# TestBoardExport.net
KiCad netlist of a schematic drawn in EAGLE
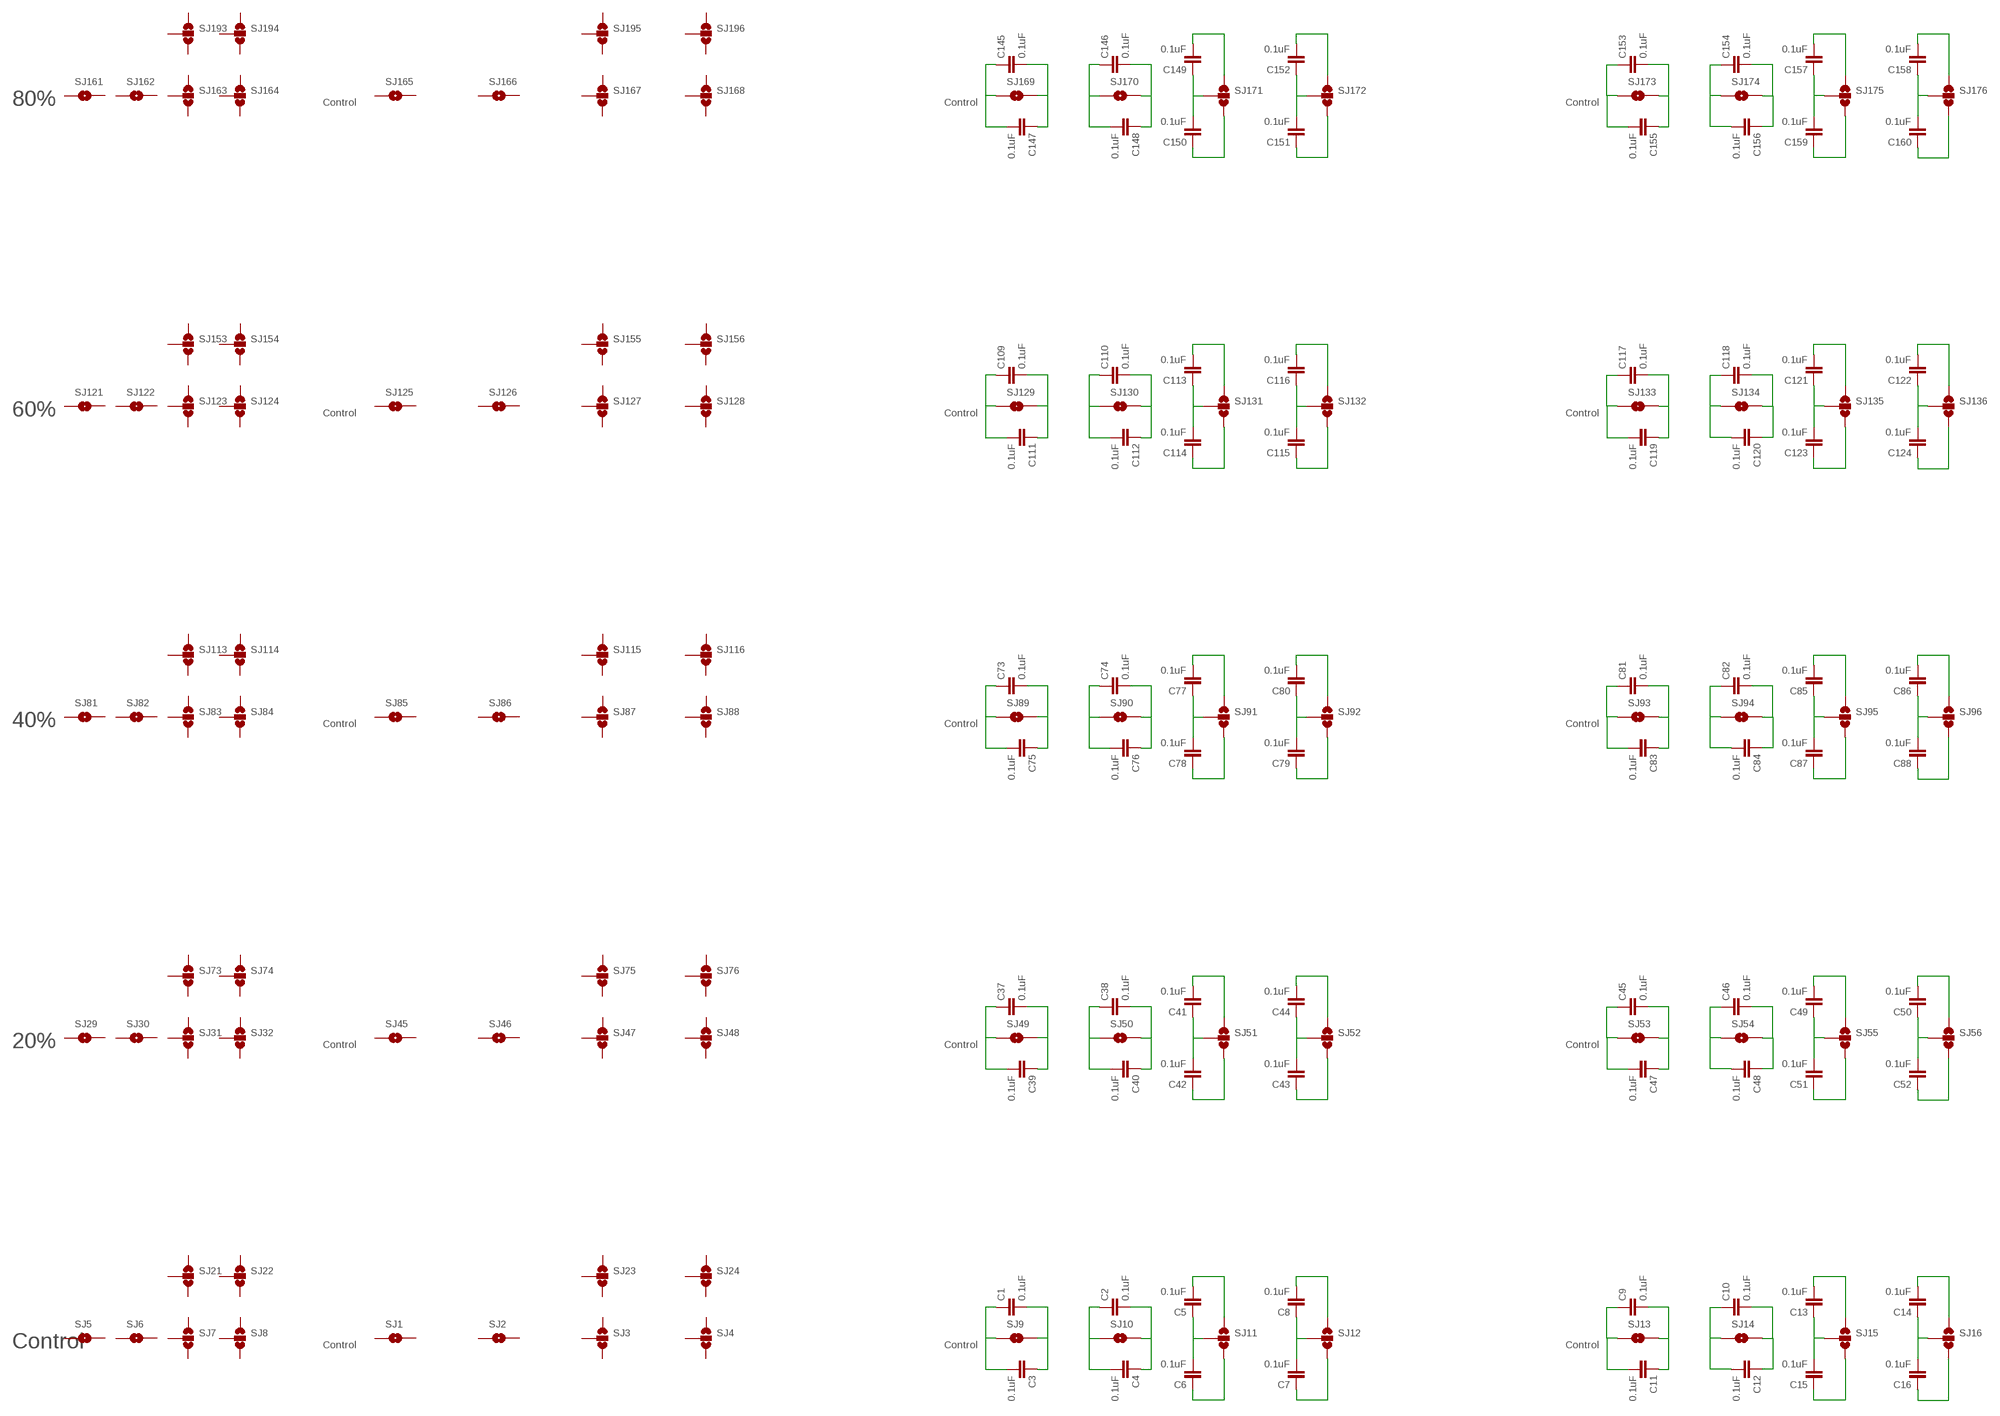
[diagram p0: schematic, sheet 1, part 1 of 3]
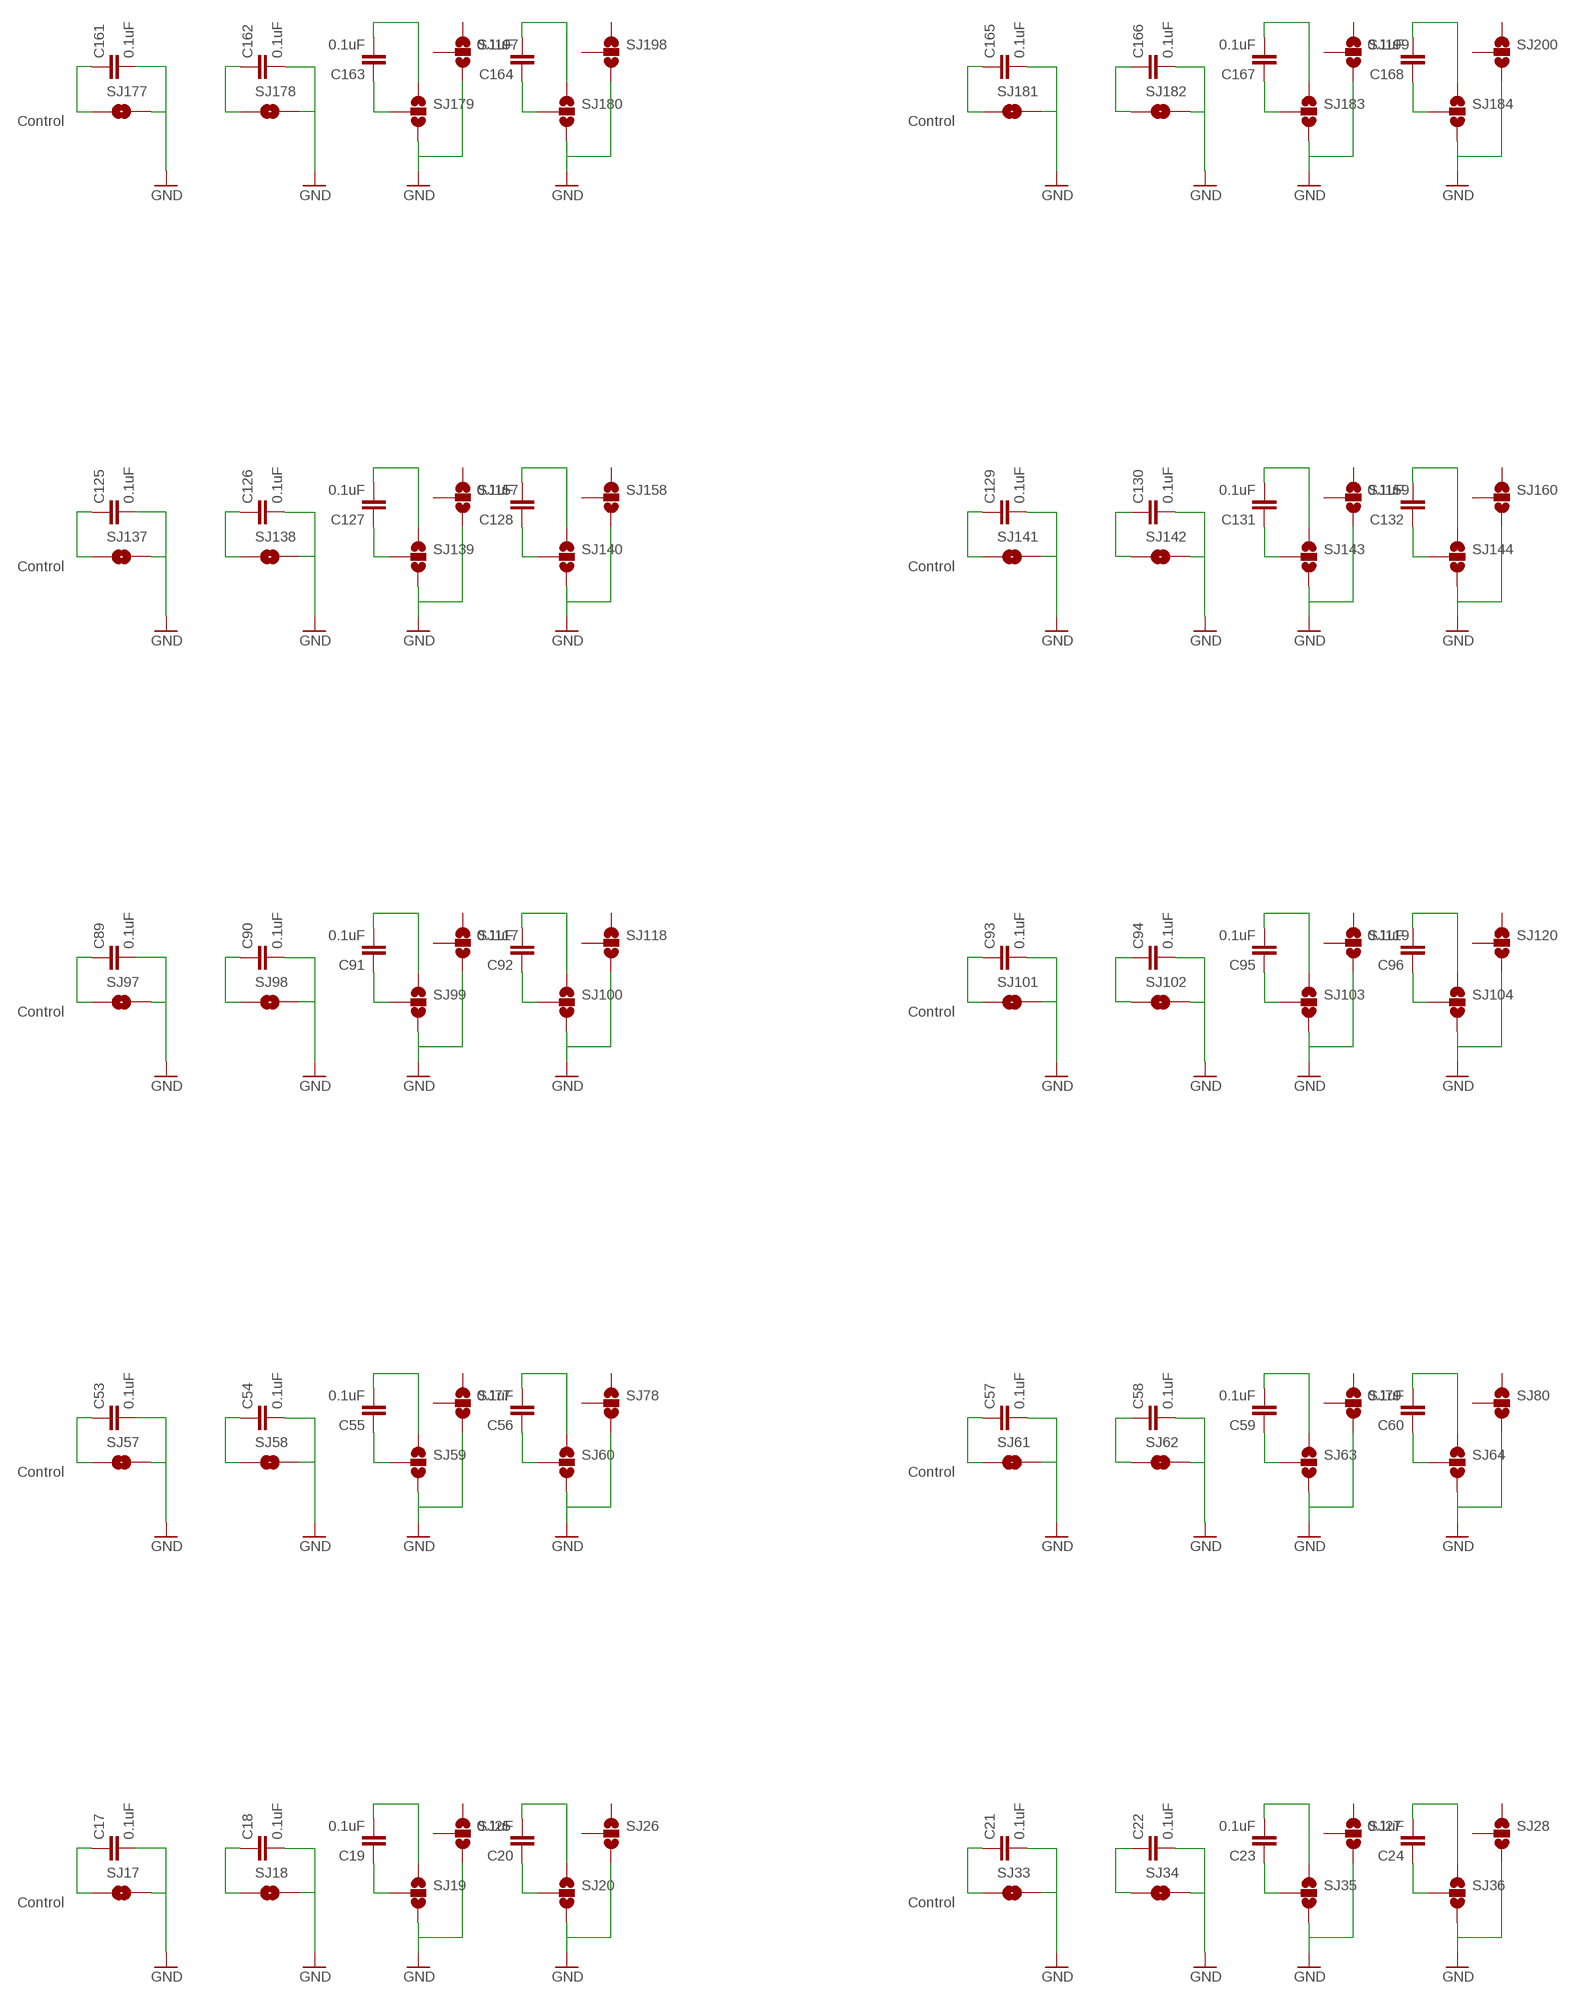
[diagram p1: schematic, sheet 1, part 2 of 3]
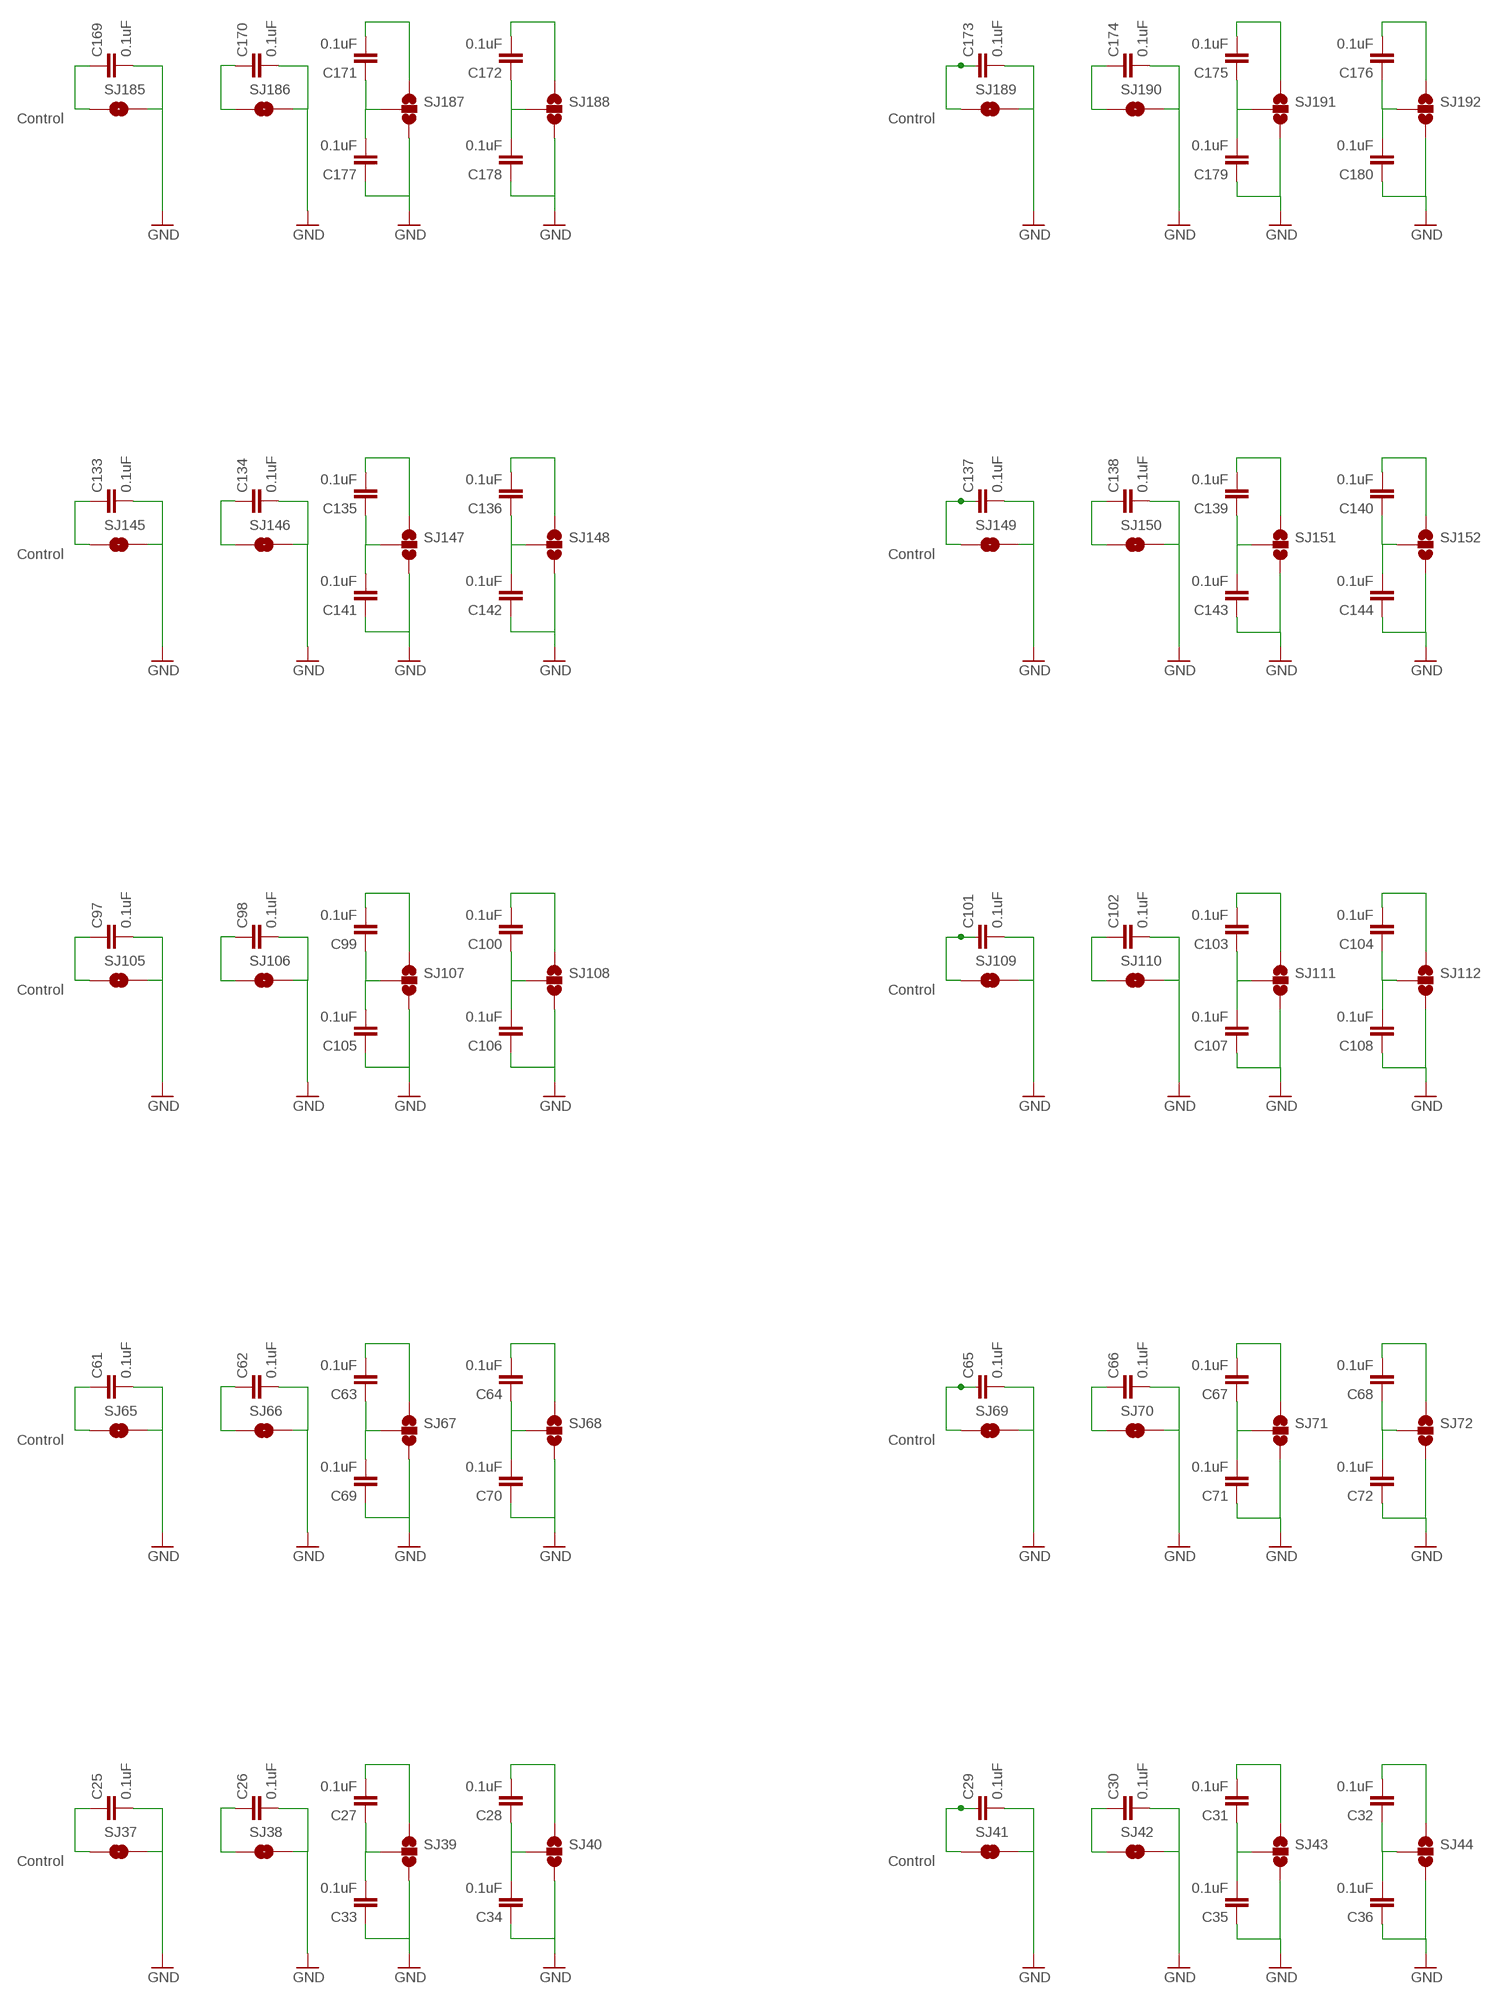
[diagram p2: schematic, sheet 1, part 3 of 3]

(export (version "E")
  (design (tool "Eeschema 10.0.6"))
  (components
    (comp (ref "C1")
      (value "0.1uF")
      (footprint "eagle-import:0603-CAP")
      (libsource (lib "eagle-import") (part "0.1UF-25V-5%(0603)"))
    )
    (comp (ref "C2")
      (value "0.1uF")
      (footprint "eagle-import:0603-CAP")
      (libsource (lib "eagle-import") (part "0.1UF-25V-5%(0603)"))
    )
    (comp (ref "C3")
      (value "0.1uF")
      (footprint "eagle-import:0603-CAP")
      (libsource (lib "eagle-import") (part "0.1UF-25V-5%(0603)"))
    )
    (comp (ref "C4")
      (value "0.1uF")
      (footprint "eagle-import:0603-CAP")
      (libsource (lib "eagle-import") (part "0.1UF-25V-5%(0603)"))
    )
    (comp (ref "C5")
      (value "0.1uF")
      (footprint "eagle-import:0603-CAP")
      (libsource (lib "eagle-import") (part "0.1UF-25V-5%(0603)"))
    )
    (comp (ref "C6")
      (value "0.1uF")
      (footprint "eagle-import:0603-CAP")
      (libsource (lib "eagle-import") (part "0.1UF-25V-5%(0603)"))
    )
    (comp (ref "C7")
      (value "0.1uF")
      (footprint "eagle-import:0603-CAP")
      (libsource (lib "eagle-import") (part "0.1UF-25V-5%(0603)"))
    )
    (comp (ref "C8")
      (value "0.1uF")
      (footprint "eagle-import:0603-CAP")
      (libsource (lib "eagle-import") (part "0.1UF-25V-5%(0603)"))
    )
    (comp (ref "C9")
      (value "0.1uF")
      (footprint "eagle-import:0603-CAP")
      (libsource (lib "eagle-import") (part "0.1UF-25V-5%(0603)"))
    )
    (comp (ref "C10")
      (value "0.1uF")
      (footprint "eagle-import:0603-CAP")
      (libsource (lib "eagle-import") (part "0.1UF-25V-5%(0603)"))
    )
    (comp (ref "C11")
      (value "0.1uF")
      (footprint "eagle-import:0603-CAP")
      (libsource (lib "eagle-import") (part "0.1UF-25V-5%(0603)"))
    )
    (comp (ref "C12")
      (value "0.1uF")
      (footprint "eagle-import:0603-CAP")
      (libsource (lib "eagle-import") (part "0.1UF-25V-5%(0603)"))
    )
    (comp (ref "C13")
      (value "0.1uF")
      (footprint "eagle-import:0603-CAP")
      (libsource (lib "eagle-import") (part "0.1UF-25V-5%(0603)"))
    )
    (comp (ref "C14")
      (value "0.1uF")
      (footprint "eagle-import:0603-CAP")
      (libsource (lib "eagle-import") (part "0.1UF-25V-5%(0603)"))
    )
    (comp (ref "C15")
      (value "0.1uF")
      (footprint "eagle-import:0603-CAP")
      (libsource (lib "eagle-import") (part "0.1UF-25V-5%(0603)"))
    )
    (comp (ref "C16")
      (value "0.1uF")
      (footprint "eagle-import:0603-CAP")
      (libsource (lib "eagle-import") (part "0.1UF-25V-5%(0603)"))
    )
    (comp (ref "C17")
      (value "0.1uF")
      (footprint "eagle-import:0603-CAP")
      (libsource (lib "eagle-import") (part "0.1UF-25V-5%(0603)"))
    )
    (comp (ref "C18")
      (value "0.1uF")
      (footprint "eagle-import:0603-CAP")
      (libsource (lib "eagle-import") (part "0.1UF-25V-5%(0603)"))
    )
    (comp (ref "C19")
      (value "0.1uF")
      (footprint "eagle-import:0603-CAP")
      (libsource (lib "eagle-import") (part "0.1UF-25V-5%(0603)"))
    )
    (comp (ref "C20")
      (value "0.1uF")
      (footprint "eagle-import:0603-CAP")
      (libsource (lib "eagle-import") (part "0.1UF-25V-5%(0603)"))
    )
    (comp (ref "C21")
      (value "0.1uF")
      (footprint "eagle-import:0603-CAP")
      (libsource (lib "eagle-import") (part "0.1UF-25V-5%(0603)"))
    )
    (comp (ref "C22")
      (value "0.1uF")
      (footprint "eagle-import:0603-CAP")
      (libsource (lib "eagle-import") (part "0.1UF-25V-5%(0603)"))
    )
    (comp (ref "C23")
      (value "0.1uF")
      (footprint "eagle-import:0603-CAP")
      (libsource (lib "eagle-import") (part "0.1UF-25V-5%(0603)"))
    )
    (comp (ref "C24")
      (value "0.1uF")
      (footprint "eagle-import:0603-CAP")
      (libsource (lib "eagle-import") (part "0.1UF-25V-5%(0603)"))
    )
    (comp (ref "C25")
      (value "0.1uF")
      (footprint "eagle-import:0603-CAP")
      (libsource (lib "eagle-import") (part "0.1UF-25V-5%(0603)"))
    )
    (comp (ref "C26")
      (value "0.1uF")
      (footprint "eagle-import:0603-CAP")
      (libsource (lib "eagle-import") (part "0.1UF-25V-5%(0603)"))
    )
    (comp (ref "C27")
      (value "0.1uF")
      (footprint "eagle-import:0603-CAP")
      (libsource (lib "eagle-import") (part "0.1UF-25V-5%(0603)"))
    )
    (comp (ref "C28")
      (value "0.1uF")
      (footprint "eagle-import:0603-CAP")
      (libsource (lib "eagle-import") (part "0.1UF-25V-5%(0603)"))
    )
    (comp (ref "C29")
      (value "0.1uF")
      (footprint "eagle-import:0603-CAP")
      (libsource (lib "eagle-import") (part "0.1UF-25V-5%(0603)"))
    )
    (comp (ref "C30")
      (value "0.1uF")
      (footprint "eagle-import:0603-CAP")
      (libsource (lib "eagle-import") (part "0.1UF-25V-5%(0603)"))
    )
    (comp (ref "C31")
      (value "0.1uF")
      (footprint "eagle-import:0603-CAP")
      (libsource (lib "eagle-import") (part "0.1UF-25V-5%(0603)"))
    )
    (comp (ref "C32")
      (value "0.1uF")
      (footprint "eagle-import:0603-CAP")
      (libsource (lib "eagle-import") (part "0.1UF-25V-5%(0603)"))
    )
    (comp (ref "C33")
      (value "0.1uF")
      (footprint "eagle-import:0603-CAP")
      (libsource (lib "eagle-import") (part "0.1UF-25V-5%(0603)"))
    )
    (comp (ref "C34")
      (value "0.1uF")
      (footprint "eagle-import:0603-CAP")
      (libsource (lib "eagle-import") (part "0.1UF-25V-5%(0603)"))
    )
    (comp (ref "C35")
      (value "0.1uF")
      (footprint "eagle-import:0603-CAP")
      (libsource (lib "eagle-import") (part "0.1UF-25V-5%(0603)"))
    )
    (comp (ref "C36")
      (value "0.1uF")
      (footprint "eagle-import:0603-CAP")
      (libsource (lib "eagle-import") (part "0.1UF-25V-5%(0603)"))
    )
    (comp (ref "C37")
      (value "0.1uF")
      (footprint "eagle-import:0603-CAP")
      (libsource (lib "eagle-import") (part "0.1UF-25V-5%(0603)"))
    )
    (comp (ref "C38")
      (value "0.1uF")
      (footprint "eagle-import:0603-CAP")
      (libsource (lib "eagle-import") (part "0.1UF-25V-5%(0603)"))
    )
    (comp (ref "C39")
      (value "0.1uF")
      (footprint "eagle-import:0603-CAP")
      (libsource (lib "eagle-import") (part "0.1UF-25V-5%(0603)"))
    )
    (comp (ref "C40")
      (value "0.1uF")
      (footprint "eagle-import:0603-CAP")
      (libsource (lib "eagle-import") (part "0.1UF-25V-5%(0603)"))
    )
    (comp (ref "C41")
      (value "0.1uF")
      (footprint "eagle-import:0603-CAP")
      (libsource (lib "eagle-import") (part "0.1UF-25V-5%(0603)"))
    )
    (comp (ref "C42")
      (value "0.1uF")
      (footprint "eagle-import:0603-CAP")
      (libsource (lib "eagle-import") (part "0.1UF-25V-5%(0603)"))
    )
    (comp (ref "C43")
      (value "0.1uF")
      (footprint "eagle-import:0603-CAP")
      (libsource (lib "eagle-import") (part "0.1UF-25V-5%(0603)"))
    )
    (comp (ref "C44")
      (value "0.1uF")
      (footprint "eagle-import:0603-CAP")
      (libsource (lib "eagle-import") (part "0.1UF-25V-5%(0603)"))
    )
    (comp (ref "C45")
      (value "0.1uF")
      (footprint "eagle-import:0603-CAP")
      (libsource (lib "eagle-import") (part "0.1UF-25V-5%(0603)"))
    )
    (comp (ref "C46")
      (value "0.1uF")
      (footprint "eagle-import:0603-CAP")
      (libsource (lib "eagle-import") (part "0.1UF-25V-5%(0603)"))
    )
    (comp (ref "C47")
      (value "0.1uF")
      (footprint "eagle-import:0603-CAP")
      (libsource (lib "eagle-import") (part "0.1UF-25V-5%(0603)"))
    )
    (comp (ref "C48")
      (value "0.1uF")
      (footprint "eagle-import:0603-CAP")
      (libsource (lib "eagle-import") (part "0.1UF-25V-5%(0603)"))
    )
    (comp (ref "C49")
      (value "0.1uF")
      (footprint "eagle-import:0603-CAP")
      (libsource (lib "eagle-import") (part "0.1UF-25V-5%(0603)"))
    )
    (comp (ref "C50")
      (value "0.1uF")
      (footprint "eagle-import:0603-CAP")
      (libsource (lib "eagle-import") (part "0.1UF-25V-5%(0603)"))
    )
    (comp (ref "C51")
      (value "0.1uF")
      (footprint "eagle-import:0603-CAP")
      (libsource (lib "eagle-import") (part "0.1UF-25V-5%(0603)"))
    )
    (comp (ref "C52")
      (value "0.1uF")
      (footprint "eagle-import:0603-CAP")
      (libsource (lib "eagle-import") (part "0.1UF-25V-5%(0603)"))
    )
    (comp (ref "C53")
      (value "0.1uF")
      (footprint "eagle-import:0603-CAP")
      (libsource (lib "eagle-import") (part "0.1UF-25V-5%(0603)"))
    )
    (comp (ref "C54")
      (value "0.1uF")
      (footprint "eagle-import:0603-CAP")
      (libsource (lib "eagle-import") (part "0.1UF-25V-5%(0603)"))
    )
    (comp (ref "C55")
      (value "0.1uF")
      (footprint "eagle-import:0603-CAP")
      (libsource (lib "eagle-import") (part "0.1UF-25V-5%(0603)"))
    )
    (comp (ref "C56")
      (value "0.1uF")
      (footprint "eagle-import:0603-CAP")
      (libsource (lib "eagle-import") (part "0.1UF-25V-5%(0603)"))
    )
    (comp (ref "C57")
      (value "0.1uF")
      (footprint "eagle-import:0603-CAP")
      (libsource (lib "eagle-import") (part "0.1UF-25V-5%(0603)"))
    )
    (comp (ref "C58")
      (value "0.1uF")
      (footprint "eagle-import:0603-CAP")
      (libsource (lib "eagle-import") (part "0.1UF-25V-5%(0603)"))
    )
    (comp (ref "C59")
      (value "0.1uF")
      (footprint "eagle-import:0603-CAP")
      (libsource (lib "eagle-import") (part "0.1UF-25V-5%(0603)"))
    )
    (comp (ref "C60")
      (value "0.1uF")
      (footprint "eagle-import:0603-CAP")
      (libsource (lib "eagle-import") (part "0.1UF-25V-5%(0603)"))
    )
    (comp (ref "C61")
      (value "0.1uF")
      (footprint "eagle-import:0603-CAP")
      (libsource (lib "eagle-import") (part "0.1UF-25V-5%(0603)"))
    )
    (comp (ref "C62")
      (value "0.1uF")
      (footprint "eagle-import:0603-CAP")
      (libsource (lib "eagle-import") (part "0.1UF-25V-5%(0603)"))
    )
    (comp (ref "C63")
      (value "0.1uF")
      (footprint "eagle-import:0603-CAP")
      (libsource (lib "eagle-import") (part "0.1UF-25V-5%(0603)"))
    )
    (comp (ref "C64")
      (value "0.1uF")
      (footprint "eagle-import:0603-CAP")
      (libsource (lib "eagle-import") (part "0.1UF-25V-5%(0603)"))
    )
    (comp (ref "C65")
      (value "0.1uF")
      (footprint "eagle-import:0603-CAP")
      (libsource (lib "eagle-import") (part "0.1UF-25V-5%(0603)"))
    )
    (comp (ref "C66")
      (value "0.1uF")
      (footprint "eagle-import:0603-CAP")
      (libsource (lib "eagle-import") (part "0.1UF-25V-5%(0603)"))
    )
    (comp (ref "C67")
      (value "0.1uF")
      (footprint "eagle-import:0603-CAP")
      (libsource (lib "eagle-import") (part "0.1UF-25V-5%(0603)"))
    )
    (comp (ref "C68")
      (value "0.1uF")
      (footprint "eagle-import:0603-CAP")
      (libsource (lib "eagle-import") (part "0.1UF-25V-5%(0603)"))
    )
    (comp (ref "C69")
      (value "0.1uF")
      (footprint "eagle-import:0603-CAP")
      (libsource (lib "eagle-import") (part "0.1UF-25V-5%(0603)"))
    )
    (comp (ref "C70")
      (value "0.1uF")
      (footprint "eagle-import:0603-CAP")
      (libsource (lib "eagle-import") (part "0.1UF-25V-5%(0603)"))
    )
    (comp (ref "C71")
      (value "0.1uF")
      (footprint "eagle-import:0603-CAP")
      (libsource (lib "eagle-import") (part "0.1UF-25V-5%(0603)"))
    )
    (comp (ref "C72")
      (value "0.1uF")
      (footprint "eagle-import:0603-CAP")
      (libsource (lib "eagle-import") (part "0.1UF-25V-5%(0603)"))
    )
    (comp (ref "C73")
      (value "0.1uF")
      (footprint "eagle-import:0603-CAP")
      (libsource (lib "eagle-import") (part "0.1UF-25V-5%(0603)"))
    )
    (comp (ref "C74")
      (value "0.1uF")
      (footprint "eagle-import:0603-CAP")
      (libsource (lib "eagle-import") (part "0.1UF-25V-5%(0603)"))
    )
    (comp (ref "C75")
      (value "0.1uF")
      (footprint "eagle-import:0603-CAP")
      (libsource (lib "eagle-import") (part "0.1UF-25V-5%(0603)"))
    )
    (comp (ref "C76")
      (value "0.1uF")
      (footprint "eagle-import:0603-CAP")
      (libsource (lib "eagle-import") (part "0.1UF-25V-5%(0603)"))
    )
    (comp (ref "C77")
      (value "0.1uF")
      (footprint "eagle-import:0603-CAP")
      (libsource (lib "eagle-import") (part "0.1UF-25V-5%(0603)"))
    )
    (comp (ref "C78")
      (value "0.1uF")
      (footprint "eagle-import:0603-CAP")
      (libsource (lib "eagle-import") (part "0.1UF-25V-5%(0603)"))
    )
    (comp (ref "C79")
      (value "0.1uF")
      (footprint "eagle-import:0603-CAP")
      (libsource (lib "eagle-import") (part "0.1UF-25V-5%(0603)"))
    )
    (comp (ref "C80")
      (value "0.1uF")
      (footprint "eagle-import:0603-CAP")
      (libsource (lib "eagle-import") (part "0.1UF-25V-5%(0603)"))
    )
    (comp (ref "C81")
      (value "0.1uF")
      (footprint "eagle-import:0603-CAP")
      (libsource (lib "eagle-import") (part "0.1UF-25V-5%(0603)"))
    )
    (comp (ref "C82")
      (value "0.1uF")
      (footprint "eagle-import:0603-CAP")
      (libsource (lib "eagle-import") (part "0.1UF-25V-5%(0603)"))
    )
    (comp (ref "C83")
      (value "0.1uF")
      (footprint "eagle-import:0603-CAP")
      (libsource (lib "eagle-import") (part "0.1UF-25V-5%(0603)"))
    )
    (comp (ref "C84")
      (value "0.1uF")
      (footprint "eagle-import:0603-CAP")
      (libsource (lib "eagle-import") (part "0.1UF-25V-5%(0603)"))
    )
    (comp (ref "C85")
      (value "0.1uF")
      (footprint "eagle-import:0603-CAP")
      (libsource (lib "eagle-import") (part "0.1UF-25V-5%(0603)"))
    )
    (comp (ref "C86")
      (value "0.1uF")
      (footprint "eagle-import:0603-CAP")
      (libsource (lib "eagle-import") (part "0.1UF-25V-5%(0603)"))
    )
    (comp (ref "C87")
      (value "0.1uF")
      (footprint "eagle-import:0603-CAP")
      (libsource (lib "eagle-import") (part "0.1UF-25V-5%(0603)"))
    )
    (comp (ref "C88")
      (value "0.1uF")
      (footprint "eagle-import:0603-CAP")
      (libsource (lib "eagle-import") (part "0.1UF-25V-5%(0603)"))
    )
    (comp (ref "C89")
      (value "0.1uF")
      (footprint "eagle-import:0603-CAP")
      (libsource (lib "eagle-import") (part "0.1UF-25V-5%(0603)"))
    )
    (comp (ref "C90")
      (value "0.1uF")
      (footprint "eagle-import:0603-CAP")
      (libsource (lib "eagle-import") (part "0.1UF-25V-5%(0603)"))
    )
    (comp (ref "C91")
      (value "0.1uF")
      (footprint "eagle-import:0603-CAP")
      (libsource (lib "eagle-import") (part "0.1UF-25V-5%(0603)"))
    )
    (comp (ref "C92")
      (value "0.1uF")
      (footprint "eagle-import:0603-CAP")
      (libsource (lib "eagle-import") (part "0.1UF-25V-5%(0603)"))
    )
    (comp (ref "C93")
      (value "0.1uF")
      (footprint "eagle-import:0603-CAP")
      (libsource (lib "eagle-import") (part "0.1UF-25V-5%(0603)"))
    )
    (comp (ref "C94")
      (value "0.1uF")
      (footprint "eagle-import:0603-CAP")
      (libsource (lib "eagle-import") (part "0.1UF-25V-5%(0603)"))
    )
    (comp (ref "C95")
      (value "0.1uF")
      (footprint "eagle-import:0603-CAP")
      (libsource (lib "eagle-import") (part "0.1UF-25V-5%(0603)"))
    )
    (comp (ref "C96")
      (value "0.1uF")
      (footprint "eagle-import:0603-CAP")
      (libsource (lib "eagle-import") (part "0.1UF-25V-5%(0603)"))
    )
    (comp (ref "C97")
      (value "0.1uF")
      (footprint "eagle-import:0603-CAP")
      (libsource (lib "eagle-import") (part "0.1UF-25V-5%(0603)"))
    )
    (comp (ref "C98")
      (value "0.1uF")
      (footprint "eagle-import:0603-CAP")
      (libsource (lib "eagle-import") (part "0.1UF-25V-5%(0603)"))
    )
    (comp (ref "C99")
      (value "0.1uF")
      (footprint "eagle-import:0603-CAP")
      (libsource (lib "eagle-import") (part "0.1UF-25V-5%(0603)"))
    )
    (comp (ref "C100")
      (value "0.1uF")
      (footprint "eagle-import:0603-CAP")
      (libsource (lib "eagle-import") (part "0.1UF-25V-5%(0603)"))
    )
    (comp (ref "C101")
      (value "0.1uF")
      (footprint "eagle-import:0603-CAP")
      (libsource (lib "eagle-import") (part "0.1UF-25V-5%(0603)"))
    )
    (comp (ref "C102")
      (value "0.1uF")
      (footprint "eagle-import:0603-CAP")
      (libsource (lib "eagle-import") (part "0.1UF-25V-5%(0603)"))
    )
    (comp (ref "C103")
      (value "0.1uF")
      (footprint "eagle-import:0603-CAP")
      (libsource (lib "eagle-import") (part "0.1UF-25V-5%(0603)"))
    )
    (comp (ref "C104")
      (value "0.1uF")
      (footprint "eagle-import:0603-CAP")
      (libsource (lib "eagle-import") (part "0.1UF-25V-5%(0603)"))
    )
    (comp (ref "C105")
      (value "0.1uF")
      (footprint "eagle-import:0603-CAP")
      (libsource (lib "eagle-import") (part "0.1UF-25V-5%(0603)"))
    )
    (comp (ref "C106")
      (value "0.1uF")
      (footprint "eagle-import:0603-CAP")
      (libsource (lib "eagle-import") (part "0.1UF-25V-5%(0603)"))
    )
    (comp (ref "C107")
      (value "0.1uF")
      (footprint "eagle-import:0603-CAP")
      (libsource (lib "eagle-import") (part "0.1UF-25V-5%(0603)"))
    )
    (comp (ref "C108")
      (value "0.1uF")
      (footprint "eagle-import:0603-CAP")
      (libsource (lib "eagle-import") (part "0.1UF-25V-5%(0603)"))
    )
    (comp (ref "C109")
      (value "0.1uF")
      (footprint "eagle-import:0603-CAP")
      (libsource (lib "eagle-import") (part "0.1UF-25V-5%(0603)"))
    )
    (comp (ref "C110")
      (value "0.1uF")
      (footprint "eagle-import:0603-CAP")
      (libsource (lib "eagle-import") (part "0.1UF-25V-5%(0603)"))
    )
    (comp (ref "C111")
      (value "0.1uF")
      (footprint "eagle-import:0603-CAP")
      (libsource (lib "eagle-import") (part "0.1UF-25V-5%(0603)"))
    )
    (comp (ref "C112")
      (value "0.1uF")
      (footprint "eagle-import:0603-CAP")
      (libsource (lib "eagle-import") (part "0.1UF-25V-5%(0603)"))
    )
    (comp (ref "C113")
      (value "0.1uF")
      (footprint "eagle-import:0603-CAP")
      (libsource (lib "eagle-import") (part "0.1UF-25V-5%(0603)"))
    )
    (comp (ref "C114")
      (value "0.1uF")
      (footprint "eagle-import:0603-CAP")
      (libsource (lib "eagle-import") (part "0.1UF-25V-5%(0603)"))
    )
    (comp (ref "C115")
      (value "0.1uF")
      (footprint "eagle-import:0603-CAP")
      (libsource (lib "eagle-import") (part "0.1UF-25V-5%(0603)"))
    )
    (comp (ref "C116")
      (value "0.1uF")
      (footprint "eagle-import:0603-CAP")
      (libsource (lib "eagle-import") (part "0.1UF-25V-5%(0603)"))
    )
    (comp (ref "C117")
      (value "0.1uF")
      (footprint "eagle-import:0603-CAP")
      (libsource (lib "eagle-import") (part "0.1UF-25V-5%(0603)"))
    )
    (comp (ref "C118")
      (value "0.1uF")
      (footprint "eagle-import:0603-CAP")
      (libsource (lib "eagle-import") (part "0.1UF-25V-5%(0603)"))
    )
    (comp (ref "C119")
      (value "0.1uF")
      (footprint "eagle-import:0603-CAP")
      (libsource (lib "eagle-import") (part "0.1UF-25V-5%(0603)"))
    )
    (comp (ref "C120")
      (value "0.1uF")
      (footprint "eagle-import:0603-CAP")
      (libsource (lib "eagle-import") (part "0.1UF-25V-5%(0603)"))
    )
    (comp (ref "C121")
      (value "0.1uF")
      (footprint "eagle-import:0603-CAP")
      (libsource (lib "eagle-import") (part "0.1UF-25V-5%(0603)"))
    )
    (comp (ref "C122")
      (value "0.1uF")
      (footprint "eagle-import:0603-CAP")
      (libsource (lib "eagle-import") (part "0.1UF-25V-5%(0603)"))
    )
    (comp (ref "C123")
      (value "0.1uF")
      (footprint "eagle-import:0603-CAP")
      (libsource (lib "eagle-import") (part "0.1UF-25V-5%(0603)"))
    )
    (comp (ref "C124")
      (value "0.1uF")
      (footprint "eagle-import:0603-CAP")
      (libsource (lib "eagle-import") (part "0.1UF-25V-5%(0603)"))
    )
    (comp (ref "C125")
      (value "0.1uF")
      (footprint "eagle-import:0603-CAP")
      (libsource (lib "eagle-import") (part "0.1UF-25V-5%(0603)"))
    )
    (comp (ref "C126")
      (value "0.1uF")
      (footprint "eagle-import:0603-CAP")
      (libsource (lib "eagle-import") (part "0.1UF-25V-5%(0603)"))
    )
    (comp (ref "C127")
      (value "0.1uF")
      (footprint "eagle-import:0603-CAP")
      (libsource (lib "eagle-import") (part "0.1UF-25V-5%(0603)"))
    )
    (comp (ref "C128")
      (value "0.1uF")
      (footprint "eagle-import:0603-CAP")
      (libsource (lib "eagle-import") (part "0.1UF-25V-5%(0603)"))
    )
    (comp (ref "C129")
      (value "0.1uF")
      (footprint "eagle-import:0603-CAP")
      (libsource (lib "eagle-import") (part "0.1UF-25V-5%(0603)"))
    )
    (comp (ref "C130")
      (value "0.1uF")
      (footprint "eagle-import:0603-CAP")
      (libsource (lib "eagle-import") (part "0.1UF-25V-5%(0603)"))
    )
    (comp (ref "C131")
      (value "0.1uF")
      (footprint "eagle-import:0603-CAP")
      (libsource (lib "eagle-import") (part "0.1UF-25V-5%(0603)"))
    )
    (comp (ref "C132")
      (value "0.1uF")
      (footprint "eagle-import:0603-CAP")
      (libsource (lib "eagle-import") (part "0.1UF-25V-5%(0603)"))
    )
    (comp (ref "C133")
      (value "0.1uF")
      (footprint "eagle-import:0603-CAP")
      (libsource (lib "eagle-import") (part "0.1UF-25V-5%(0603)"))
    )
    (comp (ref "C134")
      (value "0.1uF")
      (footprint "eagle-import:0603-CAP")
      (libsource (lib "eagle-import") (part "0.1UF-25V-5%(0603)"))
    )
    (comp (ref "C135")
      (value "0.1uF")
      (footprint "eagle-import:0603-CAP")
      (libsource (lib "eagle-import") (part "0.1UF-25V-5%(0603)"))
    )
    (comp (ref "C136")
      (value "0.1uF")
      (footprint "eagle-import:0603-CAP")
      (libsource (lib "eagle-import") (part "0.1UF-25V-5%(0603)"))
    )
    (comp (ref "C137")
      (value "0.1uF")
      (footprint "eagle-import:0603-CAP")
      (libsource (lib "eagle-import") (part "0.1UF-25V-5%(0603)"))
    )
    (comp (ref "C138")
      (value "0.1uF")
      (footprint "eagle-import:0603-CAP")
      (libsource (lib "eagle-import") (part "0.1UF-25V-5%(0603)"))
    )
    (comp (ref "C139")
      (value "0.1uF")
      (footprint "eagle-import:0603-CAP")
      (libsource (lib "eagle-import") (part "0.1UF-25V-5%(0603)"))
    )
    (comp (ref "C140")
      (value "0.1uF")
      (footprint "eagle-import:0603-CAP")
      (libsource (lib "eagle-import") (part "0.1UF-25V-5%(0603)"))
    )
    (comp (ref "C141")
      (value "0.1uF")
      (footprint "eagle-import:0603-CAP")
      (libsource (lib "eagle-import") (part "0.1UF-25V-5%(0603)"))
    )
    (comp (ref "C142")
      (value "0.1uF")
      (footprint "eagle-import:0603-CAP")
      (libsource (lib "eagle-import") (part "0.1UF-25V-5%(0603)"))
    )
    (comp (ref "C143")
      (value "0.1uF")
      (footprint "eagle-import:0603-CAP")
      (libsource (lib "eagle-import") (part "0.1UF-25V-5%(0603)"))
    )
    (comp (ref "C144")
      (value "0.1uF")
      (footprint "eagle-import:0603-CAP")
      (libsource (lib "eagle-import") (part "0.1UF-25V-5%(0603)"))
    )
    (comp (ref "C145")
      (value "0.1uF")
      (footprint "eagle-import:0603-CAP")
      (libsource (lib "eagle-import") (part "0.1UF-25V-5%(0603)"))
    )
    (comp (ref "C146")
      (value "0.1uF")
      (footprint "eagle-import:0603-CAP")
      (libsource (lib "eagle-import") (part "0.1UF-25V-5%(0603)"))
    )
    (comp (ref "C147")
      (value "0.1uF")
      (footprint "eagle-import:0603-CAP")
      (libsource (lib "eagle-import") (part "0.1UF-25V-5%(0603)"))
    )
    (comp (ref "C148")
      (value "0.1uF")
      (footprint "eagle-import:0603-CAP")
      (libsource (lib "eagle-import") (part "0.1UF-25V-5%(0603)"))
    )
    (comp (ref "C149")
      (value "0.1uF")
      (footprint "eagle-import:0603-CAP")
      (libsource (lib "eagle-import") (part "0.1UF-25V-5%(0603)"))
    )
    (comp (ref "C150")
      (value "0.1uF")
      (footprint "eagle-import:0603-CAP")
      (libsource (lib "eagle-import") (part "0.1UF-25V-5%(0603)"))
    )
    (comp (ref "C151")
      (value "0.1uF")
      (footprint "eagle-import:0603-CAP")
      (libsource (lib "eagle-import") (part "0.1UF-25V-5%(0603)"))
    )
    (comp (ref "C152")
      (value "0.1uF")
      (footprint "eagle-import:0603-CAP")
      (libsource (lib "eagle-import") (part "0.1UF-25V-5%(0603)"))
    )
    (comp (ref "C153")
      (value "0.1uF")
      (footprint "eagle-import:0603-CAP")
      (libsource (lib "eagle-import") (part "0.1UF-25V-5%(0603)"))
    )
    (comp (ref "C154")
      (value "0.1uF")
      (footprint "eagle-import:0603-CAP")
      (libsource (lib "eagle-import") (part "0.1UF-25V-5%(0603)"))
    )
    (comp (ref "C155")
      (value "0.1uF")
      (footprint "eagle-import:0603-CAP")
      (libsource (lib "eagle-import") (part "0.1UF-25V-5%(0603)"))
    )
    (comp (ref "C156")
      (value "0.1uF")
      (footprint "eagle-import:0603-CAP")
      (libsource (lib "eagle-import") (part "0.1UF-25V-5%(0603)"))
    )
    (comp (ref "C157")
      (value "0.1uF")
      (footprint "eagle-import:0603-CAP")
      (libsource (lib "eagle-import") (part "0.1UF-25V-5%(0603)"))
    )
    (comp (ref "C158")
      (value "0.1uF")
      (footprint "eagle-import:0603-CAP")
      (libsource (lib "eagle-import") (part "0.1UF-25V-5%(0603)"))
    )
    (comp (ref "C159")
      (value "0.1uF")
      (footprint "eagle-import:0603-CAP")
      (libsource (lib "eagle-import") (part "0.1UF-25V-5%(0603)"))
    )
    (comp (ref "C160")
      (value "0.1uF")
      (footprint "eagle-import:0603-CAP")
      (libsource (lib "eagle-import") (part "0.1UF-25V-5%(0603)"))
    )
    (comp (ref "C161")
      (value "0.1uF")
      (footprint "eagle-import:0603-CAP")
      (libsource (lib "eagle-import") (part "0.1UF-25V-5%(0603)"))
    )
    (comp (ref "C162")
      (value "0.1uF")
      (footprint "eagle-import:0603-CAP")
      (libsource (lib "eagle-import") (part "0.1UF-25V-5%(0603)"))
    )
    (comp (ref "C163")
      (value "0.1uF")
      (footprint "eagle-import:0603-CAP")
      (libsource (lib "eagle-import") (part "0.1UF-25V-5%(0603)"))
    )
    (comp (ref "C164")
      (value "0.1uF")
      (footprint "eagle-import:0603-CAP")
      (libsource (lib "eagle-import") (part "0.1UF-25V-5%(0603)"))
    )
    (comp (ref "C165")
      (value "0.1uF")
      (footprint "eagle-import:0603-CAP")
      (libsource (lib "eagle-import") (part "0.1UF-25V-5%(0603)"))
    )
    (comp (ref "C166")
      (value "0.1uF")
      (footprint "eagle-import:0603-CAP")
      (libsource (lib "eagle-import") (part "0.1UF-25V-5%(0603)"))
    )
    (comp (ref "C167")
      (value "0.1uF")
      (footprint "eagle-import:0603-CAP")
      (libsource (lib "eagle-import") (part "0.1UF-25V-5%(0603)"))
    )
    (comp (ref "C168")
      (value "0.1uF")
      (footprint "eagle-import:0603-CAP")
      (libsource (lib "eagle-import") (part "0.1UF-25V-5%(0603)"))
    )
    (comp (ref "C169")
      (value "0.1uF")
      (footprint "eagle-import:0603-CAP")
      (libsource (lib "eagle-import") (part "0.1UF-25V-5%(0603)"))
    )
    (comp (ref "C170")
      (value "0.1uF")
      (footprint "eagle-import:0603-CAP")
      (libsource (lib "eagle-import") (part "0.1UF-25V-5%(0603)"))
    )
    (comp (ref "C171")
      (value "0.1uF")
      (footprint "eagle-import:0603-CAP")
      (libsource (lib "eagle-import") (part "0.1UF-25V-5%(0603)"))
    )
    (comp (ref "C172")
      (value "0.1uF")
      (footprint "eagle-import:0603-CAP")
      (libsource (lib "eagle-import") (part "0.1UF-25V-5%(0603)"))
    )
    (comp (ref "C173")
      (value "0.1uF")
      (footprint "eagle-import:0603-CAP")
      (libsource (lib "eagle-import") (part "0.1UF-25V-5%(0603)"))
    )
    (comp (ref "C174")
      (value "0.1uF")
      (footprint "eagle-import:0603-CAP")
      (libsource (lib "eagle-import") (part "0.1UF-25V-5%(0603)"))
    )
    (comp (ref "C175")
      (value "0.1uF")
      (footprint "eagle-import:0603-CAP")
      (libsource (lib "eagle-import") (part "0.1UF-25V-5%(0603)"))
    )
    (comp (ref "C176")
      (value "0.1uF")
      (footprint "eagle-import:0603-CAP")
      (libsource (lib "eagle-import") (part "0.1UF-25V-5%(0603)"))
    )
    (comp (ref "C177")
      (value "0.1uF")
      (footprint "eagle-import:0603-CAP")
      (libsource (lib "eagle-import") (part "0.1UF-25V-5%(0603)"))
    )
    (comp (ref "C178")
      (value "0.1uF")
      (footprint "eagle-import:0603-CAP")
      (libsource (lib "eagle-import") (part "0.1UF-25V-5%(0603)"))
    )
    (comp (ref "C179")
      (value "0.1uF")
      (footprint "eagle-import:0603-CAP")
      (libsource (lib "eagle-import") (part "0.1UF-25V-5%(0603)"))
    )
    (comp (ref "C180")
      (value "0.1uF")
      (footprint "eagle-import:0603-CAP")
      (libsource (lib "eagle-import") (part "0.1UF-25V-5%(0603)"))
    )
    (comp (ref "SJ1")
      (value "JUMPER-PAD-2-NO")
      (footprint "eagle-import:PAD-JUMPER-2-NO_NO_SILK")
      (libsource (lib "eagle-import") (part "JUMPER-PAD-2-NO"))
    )
    (comp (ref "SJ2")
      (value "JUMPER-PAD-2-NO")
      (footprint "eagle-import:PAD-JUMPER-2-NO_NO_SILK")
      (libsource (lib "eagle-import") (part "JUMPER-PAD-2-NO"))
    )
    (comp (ref "SJ3")
      (value "JUMPER-PAD-3-NOYES_SILK")
      (footprint "eagle-import:PAD-JUMPER-3-NO_YES_SILK")
      (libsource (lib "eagle-import") (part "JUMPER-PAD-3-NOYES_SILK"))
    )
    (comp (ref "SJ4")
      (value "JUMPER-PAD-3-NOYES_SILK")
      (footprint "eagle-import:PAD-JUMPER-3-NO_YES_SILK")
      (libsource (lib "eagle-import") (part "JUMPER-PAD-3-NOYES_SILK"))
    )
    (comp (ref "SJ5")
      (value "JUMPER-PAD-2-NO")
      (footprint "eagle-import:PAD-JUMPER-2-NO_NO_SILK")
      (libsource (lib "eagle-import") (part "JUMPER-PAD-2-NO"))
    )
    (comp (ref "SJ6")
      (value "JUMPER-PAD-2-NO")
      (footprint "eagle-import:PAD-JUMPER-2-NO_NO_SILK")
      (libsource (lib "eagle-import") (part "JUMPER-PAD-2-NO"))
    )
    (comp (ref "SJ7")
      (value "JUMPER-PAD-3-NOYES_SILK")
      (footprint "eagle-import:PAD-JUMPER-3-NO_YES_SILK")
      (libsource (lib "eagle-import") (part "JUMPER-PAD-3-NOYES_SILK"))
    )
    (comp (ref "SJ8")
      (value "JUMPER-PAD-3-NOYES_SILK")
      (footprint "eagle-import:PAD-JUMPER-3-NO_YES_SILK")
      (libsource (lib "eagle-import") (part "JUMPER-PAD-3-NOYES_SILK"))
    )
    (comp (ref "SJ9")
      (value "JUMPER-PAD-2-NO")
      (footprint "eagle-import:PAD-JUMPER-2-NO_NO_SILK")
      (libsource (lib "eagle-import") (part "JUMPER-PAD-2-NO"))
    )
    (comp (ref "SJ10")
      (value "JUMPER-PAD-2-NO")
      (footprint "eagle-import:PAD-JUMPER-2-NO_NO_SILK")
      (libsource (lib "eagle-import") (part "JUMPER-PAD-2-NO"))
    )
    (comp (ref "SJ11")
      (value "JUMPER-PAD-3-NOYES_SILK")
      (footprint "eagle-import:PAD-JUMPER-3-NO_YES_SILK")
      (libsource (lib "eagle-import") (part "JUMPER-PAD-3-NOYES_SILK"))
    )
    (comp (ref "SJ12")
      (value "JUMPER-PAD-3-NOYES_SILK")
      (footprint "eagle-import:PAD-JUMPER-3-NO_YES_SILK")
      (libsource (lib "eagle-import") (part "JUMPER-PAD-3-NOYES_SILK"))
    )
    (comp (ref "SJ13")
      (value "JUMPER-PAD-2-NO")
      (footprint "eagle-import:PAD-JUMPER-2-NO_NO_SILK")
      (libsource (lib "eagle-import") (part "JUMPER-PAD-2-NO"))
    )
    (comp (ref "SJ14")
      (value "JUMPER-PAD-2-NO")
      (footprint "eagle-import:PAD-JUMPER-2-NO_NO_SILK")
      (libsource (lib "eagle-import") (part "JUMPER-PAD-2-NO"))
    )
    (comp (ref "SJ15")
      (value "JUMPER-PAD-3-NOYES_SILK")
      (footprint "eagle-import:PAD-JUMPER-3-NO_YES_SILK")
      (libsource (lib "eagle-import") (part "JUMPER-PAD-3-NOYES_SILK"))
    )
    (comp (ref "SJ16")
      (value "JUMPER-PAD-3-NOYES_SILK")
      (footprint "eagle-import:PAD-JUMPER-3-NO_YES_SILK")
      (libsource (lib "eagle-import") (part "JUMPER-PAD-3-NOYES_SILK"))
    )
    (comp (ref "SJ17")
      (value "JUMPER-PAD-2-NO")
      (footprint "eagle-import:PAD-JUMPER-2-NO_NO_SILK")
      (libsource (lib "eagle-import") (part "JUMPER-PAD-2-NO"))
    )
    (comp (ref "SJ18")
      (value "JUMPER-PAD-2-NO")
      (footprint "eagle-import:PAD-JUMPER-2-NO_NO_SILK")
      (libsource (lib "eagle-import") (part "JUMPER-PAD-2-NO"))
    )
    (comp (ref "SJ19")
      (value "JUMPER-PAD-3-NOYES_SILK")
      (footprint "eagle-import:PAD-JUMPER-3-NO_YES_SILK")
      (libsource (lib "eagle-import") (part "JUMPER-PAD-3-NOYES_SILK"))
    )
    (comp (ref "SJ20")
      (value "JUMPER-PAD-3-NOYES_SILK")
      (footprint "eagle-import:PAD-JUMPER-3-NO_YES_SILK")
      (libsource (lib "eagle-import") (part "JUMPER-PAD-3-NOYES_SILK"))
    )
    (comp (ref "SJ21")
      (value "JUMPER-PAD-3-NO3_0")
      (footprint "eagle-import:PAD-JUMPER-3-NO_YES_SILK_ALL")
      (libsource (lib "eagle-import") (part "JUMPER-PAD-3-NO3_0"))
    )
    (comp (ref "SJ22")
      (value "JUMPER-PAD-3-NO3_0")
      (footprint "eagle-import:PAD-JUMPER-3-NO_YES_SILK_ALL")
      (libsource (lib "eagle-import") (part "JUMPER-PAD-3-NO3_0"))
    )
    (comp (ref "SJ23")
      (value "JUMPER-PAD-3-NO3_0")
      (footprint "eagle-import:PAD-JUMPER-3-NO_YES_SILK_ALL")
      (libsource (lib "eagle-import") (part "JUMPER-PAD-3-NO3_0"))
    )
    (comp (ref "SJ24")
      (value "JUMPER-PAD-3-NO3_0")
      (footprint "eagle-import:PAD-JUMPER-3-NO_YES_SILK_ALL")
      (libsource (lib "eagle-import") (part "JUMPER-PAD-3-NO3_0"))
    )
    (comp (ref "SJ25")
      (value "JUMPER-PAD-3-NO3_0")
      (footprint "eagle-import:PAD-JUMPER-3-NO_YES_SILK_ALL")
      (libsource (lib "eagle-import") (part "JUMPER-PAD-3-NO3_0"))
    )
    (comp (ref "SJ26")
      (value "JUMPER-PAD-3-NO3_0")
      (footprint "eagle-import:PAD-JUMPER-3-NO_YES_SILK_ALL")
      (libsource (lib "eagle-import") (part "JUMPER-PAD-3-NO3_0"))
    )
    (comp (ref "SJ27")
      (value "JUMPER-PAD-3-NO3_0")
      (footprint "eagle-import:PAD-JUMPER-3-NO_YES_SILK_ALL")
      (libsource (lib "eagle-import") (part "JUMPER-PAD-3-NO3_0"))
    )
    (comp (ref "SJ28")
      (value "JUMPER-PAD-3-NO3_0")
      (footprint "eagle-import:PAD-JUMPER-3-NO_YES_SILK_ALL")
      (libsource (lib "eagle-import") (part "JUMPER-PAD-3-NO3_0"))
    )
    (comp (ref "SJ29")
      (value "JUMPER-PAD-2-NO20")
      (footprint "eagle-import:PAD-JUMPER-2-NO_NO_SILK_20")
      (libsource (lib "eagle-import") (part "JUMPER-PAD-2-NO20"))
    )
    (comp (ref "SJ30")
      (value "JUMPER-PAD-2-NO20")
      (footprint "eagle-import:PAD-JUMPER-2-NO_NO_SILK_20")
      (libsource (lib "eagle-import") (part "JUMPER-PAD-2-NO20"))
    )
    (comp (ref "SJ31")
      (value "JUMPER-PAD-3-NO2_20")
      (footprint "eagle-import:PAD-JUMPER-3-NO_YES_SILK_20")
      (libsource (lib "eagle-import") (part "JUMPER-PAD-3-NO2_20"))
    )
    (comp (ref "SJ32")
      (value "JUMPER-PAD-3-NO2_20")
      (footprint "eagle-import:PAD-JUMPER-3-NO_YES_SILK_20")
      (libsource (lib "eagle-import") (part "JUMPER-PAD-3-NO2_20"))
    )
    (comp (ref "SJ33")
      (value "JUMPER-PAD-2-NO")
      (footprint "eagle-import:PAD-JUMPER-2-NO_NO_SILK")
      (libsource (lib "eagle-import") (part "JUMPER-PAD-2-NO"))
    )
    (comp (ref "SJ34")
      (value "JUMPER-PAD-2-NO")
      (footprint "eagle-import:PAD-JUMPER-2-NO_NO_SILK")
      (libsource (lib "eagle-import") (part "JUMPER-PAD-2-NO"))
    )
    (comp (ref "SJ35")
      (value "JUMPER-PAD-3-NOYES_SILK")
      (footprint "eagle-import:PAD-JUMPER-3-NO_YES_SILK")
      (libsource (lib "eagle-import") (part "JUMPER-PAD-3-NOYES_SILK"))
    )
    (comp (ref "SJ36")
      (value "JUMPER-PAD-3-NOYES_SILK")
      (footprint "eagle-import:PAD-JUMPER-3-NO_YES_SILK")
      (libsource (lib "eagle-import") (part "JUMPER-PAD-3-NOYES_SILK"))
    )
    (comp (ref "SJ37")
      (value "JUMPER-PAD-2-NO")
      (footprint "eagle-import:PAD-JUMPER-2-NO_NO_SILK")
      (libsource (lib "eagle-import") (part "JUMPER-PAD-2-NO"))
    )
    (comp (ref "SJ38")
      (value "JUMPER-PAD-2-NO")
      (footprint "eagle-import:PAD-JUMPER-2-NO_NO_SILK")
      (libsource (lib "eagle-import") (part "JUMPER-PAD-2-NO"))
    )
    (comp (ref "SJ39")
      (value "JUMPER-PAD-3-NOYES_SILK")
      (footprint "eagle-import:PAD-JUMPER-3-NO_YES_SILK")
      (libsource (lib "eagle-import") (part "JUMPER-PAD-3-NOYES_SILK"))
    )
    (comp (ref "SJ40")
      (value "JUMPER-PAD-3-NOYES_SILK")
      (footprint "eagle-import:PAD-JUMPER-3-NO_YES_SILK")
      (libsource (lib "eagle-import") (part "JUMPER-PAD-3-NOYES_SILK"))
    )
    (comp (ref "SJ41")
      (value "JUMPER-PAD-2-NO")
      (footprint "eagle-import:PAD-JUMPER-2-NO_NO_SILK")
      (libsource (lib "eagle-import") (part "JUMPER-PAD-2-NO"))
    )
    (comp (ref "SJ42")
      (value "JUMPER-PAD-2-NO")
      (footprint "eagle-import:PAD-JUMPER-2-NO_NO_SILK")
      (libsource (lib "eagle-import") (part "JUMPER-PAD-2-NO"))
    )
    (comp (ref "SJ43")
      (value "JUMPER-PAD-3-NOYES_SILK")
      (footprint "eagle-import:PAD-JUMPER-3-NO_YES_SILK")
      (libsource (lib "eagle-import") (part "JUMPER-PAD-3-NOYES_SILK"))
    )
    (comp (ref "SJ44")
      (value "JUMPER-PAD-3-NOYES_SILK")
      (footprint "eagle-import:PAD-JUMPER-3-NO_YES_SILK")
      (libsource (lib "eagle-import") (part "JUMPER-PAD-3-NOYES_SILK"))
    )
    (comp (ref "SJ45")
      (value "JUMPER-PAD-2-NO20")
      (footprint "eagle-import:PAD-JUMPER-2-NO_NO_SILK_20")
      (libsource (lib "eagle-import") (part "JUMPER-PAD-2-NO20"))
    )
    (comp (ref "SJ46")
      (value "JUMPER-PAD-2-NO20")
      (footprint "eagle-import:PAD-JUMPER-2-NO_NO_SILK_20")
      (libsource (lib "eagle-import") (part "JUMPER-PAD-2-NO20"))
    )
    (comp (ref "SJ47")
      (value "JUMPER-PAD-3-NO2_20")
      (footprint "eagle-import:PAD-JUMPER-3-NO_YES_SILK_20")
      (libsource (lib "eagle-import") (part "JUMPER-PAD-3-NO2_20"))
    )
    (comp (ref "SJ48")
      (value "JUMPER-PAD-3-NO2_20")
      (footprint "eagle-import:PAD-JUMPER-3-NO_YES_SILK_20")
      (libsource (lib "eagle-import") (part "JUMPER-PAD-3-NO2_20"))
    )
    (comp (ref "SJ49")
      (value "JUMPER-PAD-2-NO20")
      (footprint "eagle-import:PAD-JUMPER-2-NO_NO_SILK_20")
      (libsource (lib "eagle-import") (part "JUMPER-PAD-2-NO20"))
    )
    (comp (ref "SJ50")
      (value "JUMPER-PAD-2-NO20")
      (footprint "eagle-import:PAD-JUMPER-2-NO_NO_SILK_20")
      (libsource (lib "eagle-import") (part "JUMPER-PAD-2-NO20"))
    )
    (comp (ref "SJ51")
      (value "JUMPER-PAD-3-NO2_20")
      (footprint "eagle-import:PAD-JUMPER-3-NO_YES_SILK_20")
      (libsource (lib "eagle-import") (part "JUMPER-PAD-3-NO2_20"))
    )
    (comp (ref "SJ52")
      (value "JUMPER-PAD-3-NO2_20")
      (footprint "eagle-import:PAD-JUMPER-3-NO_YES_SILK_20")
      (libsource (lib "eagle-import") (part "JUMPER-PAD-3-NO2_20"))
    )
    (comp (ref "SJ53")
      (value "JUMPER-PAD-2-NO20")
      (footprint "eagle-import:PAD-JUMPER-2-NO_NO_SILK_20")
      (libsource (lib "eagle-import") (part "JUMPER-PAD-2-NO20"))
    )
    (comp (ref "SJ54")
      (value "JUMPER-PAD-2-NO20")
      (footprint "eagle-import:PAD-JUMPER-2-NO_NO_SILK_20")
      (libsource (lib "eagle-import") (part "JUMPER-PAD-2-NO20"))
    )
    (comp (ref "SJ55")
      (value "JUMPER-PAD-3-NO2_20")
      (footprint "eagle-import:PAD-JUMPER-3-NO_YES_SILK_20")
      (libsource (lib "eagle-import") (part "JUMPER-PAD-3-NO2_20"))
    )
    (comp (ref "SJ56")
      (value "JUMPER-PAD-3-NO2_20")
      (footprint "eagle-import:PAD-JUMPER-3-NO_YES_SILK_20")
      (libsource (lib "eagle-import") (part "JUMPER-PAD-3-NO2_20"))
    )
    (comp (ref "SJ57")
      (value "JUMPER-PAD-2-NO20")
      (footprint "eagle-import:PAD-JUMPER-2-NO_NO_SILK_20")
      (libsource (lib "eagle-import") (part "JUMPER-PAD-2-NO20"))
    )
    (comp (ref "SJ58")
      (value "JUMPER-PAD-2-NO20")
      (footprint "eagle-import:PAD-JUMPER-2-NO_NO_SILK_20")
      (libsource (lib "eagle-import") (part "JUMPER-PAD-2-NO20"))
    )
    (comp (ref "SJ59")
      (value "JUMPER-PAD-3-NO2_20")
      (footprint "eagle-import:PAD-JUMPER-3-NO_YES_SILK_20")
      (libsource (lib "eagle-import") (part "JUMPER-PAD-3-NO2_20"))
    )
    (comp (ref "SJ60")
      (value "JUMPER-PAD-3-NO2_20")
      (footprint "eagle-import:PAD-JUMPER-3-NO_YES_SILK_20")
      (libsource (lib "eagle-import") (part "JUMPER-PAD-3-NO2_20"))
    )
    (comp (ref "SJ61")
      (value "JUMPER-PAD-2-NO20")
      (footprint "eagle-import:PAD-JUMPER-2-NO_NO_SILK_20")
      (libsource (lib "eagle-import") (part "JUMPER-PAD-2-NO20"))
    )
    (comp (ref "SJ62")
      (value "JUMPER-PAD-2-NO20")
      (footprint "eagle-import:PAD-JUMPER-2-NO_NO_SILK_20")
      (libsource (lib "eagle-import") (part "JUMPER-PAD-2-NO20"))
    )
    (comp (ref "SJ63")
      (value "JUMPER-PAD-3-NO2_20")
      (footprint "eagle-import:PAD-JUMPER-3-NO_YES_SILK_20")
      (libsource (lib "eagle-import") (part "JUMPER-PAD-3-NO2_20"))
    )
    (comp (ref "SJ64")
      (value "JUMPER-PAD-3-NO2_20")
      (footprint "eagle-import:PAD-JUMPER-3-NO_YES_SILK_20")
      (libsource (lib "eagle-import") (part "JUMPER-PAD-3-NO2_20"))
    )
    (comp (ref "SJ65")
      (value "JUMPER-PAD-2-NO20")
      (footprint "eagle-import:PAD-JUMPER-2-NO_NO_SILK_20")
      (libsource (lib "eagle-import") (part "JUMPER-PAD-2-NO20"))
    )
    (comp (ref "SJ66")
      (value "JUMPER-PAD-2-NO20")
      (footprint "eagle-import:PAD-JUMPER-2-NO_NO_SILK_20")
      (libsource (lib "eagle-import") (part "JUMPER-PAD-2-NO20"))
    )
    (comp (ref "SJ67")
      (value "JUMPER-PAD-3-NO2_20")
      (footprint "eagle-import:PAD-JUMPER-3-NO_YES_SILK_20")
      (libsource (lib "eagle-import") (part "JUMPER-PAD-3-NO2_20"))
    )
    (comp (ref "SJ68")
      (value "JUMPER-PAD-3-NO2_20")
      (footprint "eagle-import:PAD-JUMPER-3-NO_YES_SILK_20")
      (libsource (lib "eagle-import") (part "JUMPER-PAD-3-NO2_20"))
    )
    (comp (ref "SJ69")
      (value "JUMPER-PAD-2-NO")
      (footprint "eagle-import:PAD-JUMPER-2-NO_NO_SILK")
      (libsource (lib "eagle-import") (part "JUMPER-PAD-2-NO"))
    )
    (comp (ref "SJ70")
      (value "JUMPER-PAD-2-NO")
      (footprint "eagle-import:PAD-JUMPER-2-NO_NO_SILK")
      (libsource (lib "eagle-import") (part "JUMPER-PAD-2-NO"))
    )
    (comp (ref "SJ71")
      (value "JUMPER-PAD-3-NO2_20")
      (footprint "eagle-import:PAD-JUMPER-3-NO_YES_SILK_20")
      (libsource (lib "eagle-import") (part "JUMPER-PAD-3-NO2_20"))
    )
    (comp (ref "SJ72")
      (value "JUMPER-PAD-3-NO2_20")
      (footprint "eagle-import:PAD-JUMPER-3-NO_YES_SILK_20")
      (libsource (lib "eagle-import") (part "JUMPER-PAD-3-NO2_20"))
    )
    (comp (ref "SJ73")
      (value "JUMPER-PAD-3-NO3_20")
      (footprint "eagle-import:PAD-JUMPER-3-NO_YES_SILK_ALL_20")
      (libsource (lib "eagle-import") (part "JUMPER-PAD-3-NO3_20"))
    )
    (comp (ref "SJ74")
      (value "JUMPER-PAD-3-NO3_20")
      (footprint "eagle-import:PAD-JUMPER-3-NO_YES_SILK_ALL_20")
      (libsource (lib "eagle-import") (part "JUMPER-PAD-3-NO3_20"))
    )
    (comp (ref "SJ75")
      (value "JUMPER-PAD-3-NO3_20")
      (footprint "eagle-import:PAD-JUMPER-3-NO_YES_SILK_ALL_20")
      (libsource (lib "eagle-import") (part "JUMPER-PAD-3-NO3_20"))
    )
    (comp (ref "SJ76")
      (value "JUMPER-PAD-3-NO3_20")
      (footprint "eagle-import:PAD-JUMPER-3-NO_YES_SILK_ALL_20")
      (libsource (lib "eagle-import") (part "JUMPER-PAD-3-NO3_20"))
    )
    (comp (ref "SJ77")
      (value "JUMPER-PAD-3-NO3_20")
      (footprint "eagle-import:PAD-JUMPER-3-NO_YES_SILK_ALL_20")
      (libsource (lib "eagle-import") (part "JUMPER-PAD-3-NO3_20"))
    )
    (comp (ref "SJ78")
      (value "JUMPER-PAD-3-NO3_20")
      (footprint "eagle-import:PAD-JUMPER-3-NO_YES_SILK_ALL_20")
      (libsource (lib "eagle-import") (part "JUMPER-PAD-3-NO3_20"))
    )
    (comp (ref "SJ79")
      (value "JUMPER-PAD-3-NO3_20")
      (footprint "eagle-import:PAD-JUMPER-3-NO_YES_SILK_ALL_20")
      (libsource (lib "eagle-import") (part "JUMPER-PAD-3-NO3_20"))
    )
    (comp (ref "SJ80")
      (value "JUMPER-PAD-3-NO3_20")
      (footprint "eagle-import:PAD-JUMPER-3-NO_YES_SILK_ALL_20")
      (libsource (lib "eagle-import") (part "JUMPER-PAD-3-NO3_20"))
    )
    (comp (ref "SJ81")
      (value "JUMPER-PAD-2-NO40")
      (footprint "eagle-import:PAD-JUMPER-2-NO_NO_SILK_40")
      (libsource (lib "eagle-import") (part "JUMPER-PAD-2-NO40"))
    )
    (comp (ref "SJ82")
      (value "JUMPER-PAD-2-NO40")
      (footprint "eagle-import:PAD-JUMPER-2-NO_NO_SILK_40")
      (libsource (lib "eagle-import") (part "JUMPER-PAD-2-NO40"))
    )
    (comp (ref "SJ83")
      (value "JUMPER-PAD-3-NO2_40")
      (footprint "eagle-import:PAD-JUMPER-3-NO_YES_SILK_40")
      (libsource (lib "eagle-import") (part "JUMPER-PAD-3-NO2_40"))
    )
    (comp (ref "SJ84")
      (value "JUMPER-PAD-3-NO2_40")
      (footprint "eagle-import:PAD-JUMPER-3-NO_YES_SILK_40")
      (libsource (lib "eagle-import") (part "JUMPER-PAD-3-NO2_40"))
    )
    (comp (ref "SJ85")
      (value "JUMPER-PAD-2-NO40")
      (footprint "eagle-import:PAD-JUMPER-2-NO_NO_SILK_40")
      (libsource (lib "eagle-import") (part "JUMPER-PAD-2-NO40"))
    )
    (comp (ref "SJ86")
      (value "JUMPER-PAD-2-NO40")
      (footprint "eagle-import:PAD-JUMPER-2-NO_NO_SILK_40")
      (libsource (lib "eagle-import") (part "JUMPER-PAD-2-NO40"))
    )
    (comp (ref "SJ87")
      (value "JUMPER-PAD-3-NO2_40")
      (footprint "eagle-import:PAD-JUMPER-3-NO_YES_SILK_40")
      (libsource (lib "eagle-import") (part "JUMPER-PAD-3-NO2_40"))
    )
    (comp (ref "SJ88")
      (value "JUMPER-PAD-3-NO2_40")
      (footprint "eagle-import:PAD-JUMPER-3-NO_YES_SILK_40")
      (libsource (lib "eagle-import") (part "JUMPER-PAD-3-NO2_40"))
    )
    (comp (ref "SJ89")
      (value "JUMPER-PAD-2-NO40")
      (footprint "eagle-import:PAD-JUMPER-2-NO_NO_SILK_40")
      (libsource (lib "eagle-import") (part "JUMPER-PAD-2-NO40"))
    )
    (comp (ref "SJ90")
      (value "JUMPER-PAD-2-NO40")
      (footprint "eagle-import:PAD-JUMPER-2-NO_NO_SILK_40")
      (libsource (lib "eagle-import") (part "JUMPER-PAD-2-NO40"))
    )
    (comp (ref "SJ91")
      (value "JUMPER-PAD-3-NO2_40")
      (footprint "eagle-import:PAD-JUMPER-3-NO_YES_SILK_40")
      (libsource (lib "eagle-import") (part "JUMPER-PAD-3-NO2_40"))
    )
    (comp (ref "SJ92")
      (value "JUMPER-PAD-3-NO2_40")
      (footprint "eagle-import:PAD-JUMPER-3-NO_YES_SILK_40")
      (libsource (lib "eagle-import") (part "JUMPER-PAD-3-NO2_40"))
    )
    (comp (ref "SJ93")
      (value "JUMPER-PAD-2-NO40")
      (footprint "eagle-import:PAD-JUMPER-2-NO_NO_SILK_40")
      (libsource (lib "eagle-import") (part "JUMPER-PAD-2-NO40"))
    )
    (comp (ref "SJ94")
      (value "JUMPER-PAD-2-NO40")
      (footprint "eagle-import:PAD-JUMPER-2-NO_NO_SILK_40")
      (libsource (lib "eagle-import") (part "JUMPER-PAD-2-NO40"))
    )
    (comp (ref "SJ95")
      (value "JUMPER-PAD-3-NO2_40")
      (footprint "eagle-import:PAD-JUMPER-3-NO_YES_SILK_40")
      (libsource (lib "eagle-import") (part "JUMPER-PAD-3-NO2_40"))
    )
    (comp (ref "SJ96")
      (value "JUMPER-PAD-3-NO2_40")
      (footprint "eagle-import:PAD-JUMPER-3-NO_YES_SILK_40")
      (libsource (lib "eagle-import") (part "JUMPER-PAD-3-NO2_40"))
    )
    (comp (ref "SJ97")
      (value "JUMPER-PAD-2-NO40")
      (footprint "eagle-import:PAD-JUMPER-2-NO_NO_SILK_40")
      (libsource (lib "eagle-import") (part "JUMPER-PAD-2-NO40"))
    )
    (comp (ref "SJ98")
      (value "JUMPER-PAD-2-NO40")
      (footprint "eagle-import:PAD-JUMPER-2-NO_NO_SILK_40")
      (libsource (lib "eagle-import") (part "JUMPER-PAD-2-NO40"))
    )
    (comp (ref "SJ99")
      (value "JUMPER-PAD-3-NO2_40")
      (footprint "eagle-import:PAD-JUMPER-3-NO_YES_SILK_40")
      (libsource (lib "eagle-import") (part "JUMPER-PAD-3-NO2_40"))
    )
    (comp (ref "SJ100")
      (value "JUMPER-PAD-3-NO2_40")
      (footprint "eagle-import:PAD-JUMPER-3-NO_YES_SILK_40")
      (libsource (lib "eagle-import") (part "JUMPER-PAD-3-NO2_40"))
    )
    (comp (ref "SJ101")
      (value "JUMPER-PAD-2-NO40")
      (footprint "eagle-import:PAD-JUMPER-2-NO_NO_SILK_40")
      (libsource (lib "eagle-import") (part "JUMPER-PAD-2-NO40"))
    )
    (comp (ref "SJ102")
      (value "JUMPER-PAD-2-NO40")
      (footprint "eagle-import:PAD-JUMPER-2-NO_NO_SILK_40")
      (libsource (lib "eagle-import") (part "JUMPER-PAD-2-NO40"))
    )
    (comp (ref "SJ103")
      (value "JUMPER-PAD-3-NO2_40")
      (footprint "eagle-import:PAD-JUMPER-3-NO_YES_SILK_40")
      (libsource (lib "eagle-import") (part "JUMPER-PAD-3-NO2_40"))
    )
    (comp (ref "SJ104")
      (value "JUMPER-PAD-3-NO2_40")
      (footprint "eagle-import:PAD-JUMPER-3-NO_YES_SILK_40")
      (libsource (lib "eagle-import") (part "JUMPER-PAD-3-NO2_40"))
    )
    (comp (ref "SJ105")
      (value "JUMPER-PAD-2-NO40")
      (footprint "eagle-import:PAD-JUMPER-2-NO_NO_SILK_40")
      (libsource (lib "eagle-import") (part "JUMPER-PAD-2-NO40"))
    )
    (comp (ref "SJ106")
      (value "JUMPER-PAD-2-NO40")
      (footprint "eagle-import:PAD-JUMPER-2-NO_NO_SILK_40")
      (libsource (lib "eagle-import") (part "JUMPER-PAD-2-NO40"))
    )
    (comp (ref "SJ107")
      (value "JUMPER-PAD-3-NO2_40")
      (footprint "eagle-import:PAD-JUMPER-3-NO_YES_SILK_40")
      (libsource (lib "eagle-import") (part "JUMPER-PAD-3-NO2_40"))
    )
    (comp (ref "SJ108")
      (value "JUMPER-PAD-3-NO2_40")
      (footprint "eagle-import:PAD-JUMPER-3-NO_YES_SILK_40")
      (libsource (lib "eagle-import") (part "JUMPER-PAD-3-NO2_40"))
    )
    (comp (ref "SJ109")
      (value "JUMPER-PAD-2-NO40")
      (footprint "eagle-import:PAD-JUMPER-2-NO_NO_SILK_40")
      (libsource (lib "eagle-import") (part "JUMPER-PAD-2-NO40"))
    )
    (comp (ref "SJ110")
      (value "JUMPER-PAD-2-NO40")
      (footprint "eagle-import:PAD-JUMPER-2-NO_NO_SILK_40")
      (libsource (lib "eagle-import") (part "JUMPER-PAD-2-NO40"))
    )
    (comp (ref "SJ111")
      (value "JUMPER-PAD-3-NO2_40")
      (footprint "eagle-import:PAD-JUMPER-3-NO_YES_SILK_40")
      (libsource (lib "eagle-import") (part "JUMPER-PAD-3-NO2_40"))
    )
    (comp (ref "SJ112")
      (value "JUMPER-PAD-3-NO2_40")
      (footprint "eagle-import:PAD-JUMPER-3-NO_YES_SILK_40")
      (libsource (lib "eagle-import") (part "JUMPER-PAD-3-NO2_40"))
    )
    (comp (ref "SJ113")
      (value "JUMPER-PAD-3-NO3_40")
      (footprint "eagle-import:PAD-JUMPER-3-NO_YES_SILK_ALL_40")
      (libsource (lib "eagle-import") (part "JUMPER-PAD-3-NO3_40"))
    )
    (comp (ref "SJ114")
      (value "JUMPER-PAD-3-NO3_40")
      (footprint "eagle-import:PAD-JUMPER-3-NO_YES_SILK_ALL_40")
      (libsource (lib "eagle-import") (part "JUMPER-PAD-3-NO3_40"))
    )
    (comp (ref "SJ115")
      (value "JUMPER-PAD-3-NO3_40")
      (footprint "eagle-import:PAD-JUMPER-3-NO_YES_SILK_ALL_40")
      (libsource (lib "eagle-import") (part "JUMPER-PAD-3-NO3_40"))
    )
    (comp (ref "SJ116")
      (value "JUMPER-PAD-3-NO3_40")
      (footprint "eagle-import:PAD-JUMPER-3-NO_YES_SILK_ALL_40")
      (libsource (lib "eagle-import") (part "JUMPER-PAD-3-NO3_40"))
    )
    (comp (ref "SJ117")
      (value "JUMPER-PAD-3-NO3_40")
      (footprint "eagle-import:PAD-JUMPER-3-NO_YES_SILK_ALL_40")
      (libsource (lib "eagle-import") (part "JUMPER-PAD-3-NO3_40"))
    )
    (comp (ref "SJ118")
      (value "JUMPER-PAD-3-NO3_40")
      (footprint "eagle-import:PAD-JUMPER-3-NO_YES_SILK_ALL_40")
      (libsource (lib "eagle-import") (part "JUMPER-PAD-3-NO3_40"))
    )
    (comp (ref "SJ119")
      (value "JUMPER-PAD-3-NO3_40")
      (footprint "eagle-import:PAD-JUMPER-3-NO_YES_SILK_ALL_40")
      (libsource (lib "eagle-import") (part "JUMPER-PAD-3-NO3_40"))
    )
    (comp (ref "SJ120")
      (value "JUMPER-PAD-3-NO3_40")
      (footprint "eagle-import:PAD-JUMPER-3-NO_YES_SILK_ALL_40")
      (libsource (lib "eagle-import") (part "JUMPER-PAD-3-NO3_40"))
    )
    (comp (ref "SJ121")
      (value "JUMPER-PAD-2-NO60")
      (footprint "eagle-import:PAD-JUMPER-2-NO_NO_SILK_60")
      (libsource (lib "eagle-import") (part "JUMPER-PAD-2-NO60"))
    )
    (comp (ref "SJ122")
      (value "JUMPER-PAD-2-NO60")
      (footprint "eagle-import:PAD-JUMPER-2-NO_NO_SILK_60")
      (libsource (lib "eagle-import") (part "JUMPER-PAD-2-NO60"))
    )
    (comp (ref "SJ123")
      (value "JUMPER-PAD-3-NO2_60")
      (footprint "eagle-import:PAD-JUMPER-3-NO_YES_SILK_60")
      (libsource (lib "eagle-import") (part "JUMPER-PAD-3-NO2_60"))
    )
    (comp (ref "SJ124")
      (value "JUMPER-PAD-3-NO2_60")
      (footprint "eagle-import:PAD-JUMPER-3-NO_YES_SILK_60")
      (libsource (lib "eagle-import") (part "JUMPER-PAD-3-NO2_60"))
    )
    (comp (ref "SJ125")
      (value "JUMPER-PAD-2-NO60")
      (footprint "eagle-import:PAD-JUMPER-2-NO_NO_SILK_60")
      (libsource (lib "eagle-import") (part "JUMPER-PAD-2-NO60"))
    )
    (comp (ref "SJ126")
      (value "JUMPER-PAD-2-NO60")
      (footprint "eagle-import:PAD-JUMPER-2-NO_NO_SILK_60")
      (libsource (lib "eagle-import") (part "JUMPER-PAD-2-NO60"))
    )
    (comp (ref "SJ127")
      (value "JUMPER-PAD-3-NO2_60")
      (footprint "eagle-import:PAD-JUMPER-3-NO_YES_SILK_60")
      (libsource (lib "eagle-import") (part "JUMPER-PAD-3-NO2_60"))
    )
    (comp (ref "SJ128")
      (value "JUMPER-PAD-3-NO2_60")
      (footprint "eagle-import:PAD-JUMPER-3-NO_YES_SILK_60")
      (libsource (lib "eagle-import") (part "JUMPER-PAD-3-NO2_60"))
    )
    (comp (ref "SJ129")
      (value "JUMPER-PAD-2-NO60")
      (footprint "eagle-import:PAD-JUMPER-2-NO_NO_SILK_60")
      (libsource (lib "eagle-import") (part "JUMPER-PAD-2-NO60"))
    )
    (comp (ref "SJ130")
      (value "JUMPER-PAD-2-NO60")
      (footprint "eagle-import:PAD-JUMPER-2-NO_NO_SILK_60")
      (libsource (lib "eagle-import") (part "JUMPER-PAD-2-NO60"))
    )
    (comp (ref "SJ131")
      (value "JUMPER-PAD-3-NO2_60")
      (footprint "eagle-import:PAD-JUMPER-3-NO_YES_SILK_60")
      (libsource (lib "eagle-import") (part "JUMPER-PAD-3-NO2_60"))
    )
    (comp (ref "SJ132")
      (value "JUMPER-PAD-3-NO2_60")
      (footprint "eagle-import:PAD-JUMPER-3-NO_YES_SILK_60")
      (libsource (lib "eagle-import") (part "JUMPER-PAD-3-NO2_60"))
    )
    (comp (ref "SJ133")
      (value "JUMPER-PAD-2-NO60")
      (footprint "eagle-import:PAD-JUMPER-2-NO_NO_SILK_60")
      (libsource (lib "eagle-import") (part "JUMPER-PAD-2-NO60"))
    )
    (comp (ref "SJ134")
      (value "JUMPER-PAD-2-NO60")
      (footprint "eagle-import:PAD-JUMPER-2-NO_NO_SILK_60")
      (libsource (lib "eagle-import") (part "JUMPER-PAD-2-NO60"))
    )
    (comp (ref "SJ135")
      (value "JUMPER-PAD-3-NO2_60")
      (footprint "eagle-import:PAD-JUMPER-3-NO_YES_SILK_60")
      (libsource (lib "eagle-import") (part "JUMPER-PAD-3-NO2_60"))
    )
    (comp (ref "SJ136")
      (value "JUMPER-PAD-3-NO2_60")
      (footprint "eagle-import:PAD-JUMPER-3-NO_YES_SILK_60")
      (libsource (lib "eagle-import") (part "JUMPER-PAD-3-NO2_60"))
    )
    (comp (ref "SJ137")
      (value "JUMPER-PAD-2-NO60")
      (footprint "eagle-import:PAD-JUMPER-2-NO_NO_SILK_60")
      (libsource (lib "eagle-import") (part "JUMPER-PAD-2-NO60"))
    )
    (comp (ref "SJ138")
      (value "JUMPER-PAD-2-NO60")
      (footprint "eagle-import:PAD-JUMPER-2-NO_NO_SILK_60")
      (libsource (lib "eagle-import") (part "JUMPER-PAD-2-NO60"))
    )
    (comp (ref "SJ139")
      (value "JUMPER-PAD-3-NO2_60")
      (footprint "eagle-import:PAD-JUMPER-3-NO_YES_SILK_60")
      (libsource (lib "eagle-import") (part "JUMPER-PAD-3-NO2_60"))
    )
    (comp (ref "SJ140")
      (value "JUMPER-PAD-3-NO2_60")
      (footprint "eagle-import:PAD-JUMPER-3-NO_YES_SILK_60")
      (libsource (lib "eagle-import") (part "JUMPER-PAD-3-NO2_60"))
    )
    (comp (ref "SJ141")
      (value "JUMPER-PAD-2-NO60")
      (footprint "eagle-import:PAD-JUMPER-2-NO_NO_SILK_60")
      (libsource (lib "eagle-import") (part "JUMPER-PAD-2-NO60"))
    )
    (comp (ref "SJ142")
      (value "JUMPER-PAD-2-NO60")
      (footprint "eagle-import:PAD-JUMPER-2-NO_NO_SILK_60")
      (libsource (lib "eagle-import") (part "JUMPER-PAD-2-NO60"))
    )
    (comp (ref "SJ143")
      (value "JUMPER-PAD-3-NO2_60")
      (footprint "eagle-import:PAD-JUMPER-3-NO_YES_SILK_60")
      (libsource (lib "eagle-import") (part "JUMPER-PAD-3-NO2_60"))
    )
    (comp (ref "SJ144")
      (value "JUMPER-PAD-3-NO2_60")
      (footprint "eagle-import:PAD-JUMPER-3-NO_YES_SILK_60")
      (libsource (lib "eagle-import") (part "JUMPER-PAD-3-NO2_60"))
    )
    (comp (ref "SJ145")
      (value "JUMPER-PAD-2-NO60")
      (footprint "eagle-import:PAD-JUMPER-2-NO_NO_SILK_60")
      (libsource (lib "eagle-import") (part "JUMPER-PAD-2-NO60"))
    )
    (comp (ref "SJ146")
      (value "JUMPER-PAD-2-NO60")
      (footprint "eagle-import:PAD-JUMPER-2-NO_NO_SILK_60")
      (libsource (lib "eagle-import") (part "JUMPER-PAD-2-NO60"))
    )
    (comp (ref "SJ147")
      (value "JUMPER-PAD-3-NO2_60")
      (footprint "eagle-import:PAD-JUMPER-3-NO_YES_SILK_60")
      (libsource (lib "eagle-import") (part "JUMPER-PAD-3-NO2_60"))
    )
    (comp (ref "SJ148")
      (value "JUMPER-PAD-3-NO2_60")
      (footprint "eagle-import:PAD-JUMPER-3-NO_YES_SILK_60")
      (libsource (lib "eagle-import") (part "JUMPER-PAD-3-NO2_60"))
    )
    (comp (ref "SJ149")
      (value "JUMPER-PAD-2-NO60")
      (footprint "eagle-import:PAD-JUMPER-2-NO_NO_SILK_60")
      (libsource (lib "eagle-import") (part "JUMPER-PAD-2-NO60"))
    )
    (comp (ref "SJ150")
      (value "JUMPER-PAD-2-NO60")
      (footprint "eagle-import:PAD-JUMPER-2-NO_NO_SILK_60")
      (libsource (lib "eagle-import") (part "JUMPER-PAD-2-NO60"))
    )
    (comp (ref "SJ151")
      (value "JUMPER-PAD-3-NO2_60")
      (footprint "eagle-import:PAD-JUMPER-3-NO_YES_SILK_60")
      (libsource (lib "eagle-import") (part "JUMPER-PAD-3-NO2_60"))
    )
    (comp (ref "SJ152")
      (value "JUMPER-PAD-3-NO2_60")
      (footprint "eagle-import:PAD-JUMPER-3-NO_YES_SILK_60")
      (libsource (lib "eagle-import") (part "JUMPER-PAD-3-NO2_60"))
    )
    (comp (ref "SJ153")
      (value "JUMPER-PAD-3-NO3_60")
      (footprint "eagle-import:PAD-JUMPER-3-NO_YES_SILK_ALL_60")
      (libsource (lib "eagle-import") (part "JUMPER-PAD-3-NO3_60"))
    )
    (comp (ref "SJ154")
      (value "JUMPER-PAD-3-NO3_60")
      (footprint "eagle-import:PAD-JUMPER-3-NO_YES_SILK_ALL_60")
      (libsource (lib "eagle-import") (part "JUMPER-PAD-3-NO3_60"))
    )
    (comp (ref "SJ155")
      (value "JUMPER-PAD-3-NO3_60")
      (footprint "eagle-import:PAD-JUMPER-3-NO_YES_SILK_ALL_60")
      (libsource (lib "eagle-import") (part "JUMPER-PAD-3-NO3_60"))
    )
    (comp (ref "SJ156")
      (value "JUMPER-PAD-3-NO3_60")
      (footprint "eagle-import:PAD-JUMPER-3-NO_YES_SILK_ALL_60")
      (libsource (lib "eagle-import") (part "JUMPER-PAD-3-NO3_60"))
    )
    (comp (ref "SJ157")
      (value "JUMPER-PAD-3-NO3_60")
      (footprint "eagle-import:PAD-JUMPER-3-NO_YES_SILK_ALL_60")
      (libsource (lib "eagle-import") (part "JUMPER-PAD-3-NO3_60"))
    )
    (comp (ref "SJ158")
      (value "JUMPER-PAD-3-NO3_60")
      (footprint "eagle-import:PAD-JUMPER-3-NO_YES_SILK_ALL_60")
      (libsource (lib "eagle-import") (part "JUMPER-PAD-3-NO3_60"))
    )
    (comp (ref "SJ159")
      (value "JUMPER-PAD-3-NO3_60")
      (footprint "eagle-import:PAD-JUMPER-3-NO_YES_SILK_ALL_60")
      (libsource (lib "eagle-import") (part "JUMPER-PAD-3-NO3_60"))
    )
    (comp (ref "SJ160")
      (value "JUMPER-PAD-3-NO3_60")
      (footprint "eagle-import:PAD-JUMPER-3-NO_YES_SILK_ALL_60")
      (libsource (lib "eagle-import") (part "JUMPER-PAD-3-NO3_60"))
    )
    (comp (ref "SJ161")
      (value "JUMPER-PAD-2-NO80")
      (footprint "eagle-import:PAD-JUMPER-2-NO_NO_SILK_80")
      (libsource (lib "eagle-import") (part "JUMPER-PAD-2-NO80"))
    )
    (comp (ref "SJ162")
      (value "JUMPER-PAD-2-NO80")
      (footprint "eagle-import:PAD-JUMPER-2-NO_NO_SILK_80")
      (libsource (lib "eagle-import") (part "JUMPER-PAD-2-NO80"))
    )
    (comp (ref "SJ163")
      (value "JUMPER-PAD-3-NO2_80")
      (footprint "eagle-import:PAD-JUMPER-3-NO_YES_SILK_80")
      (libsource (lib "eagle-import") (part "JUMPER-PAD-3-NO2_80"))
    )
    (comp (ref "SJ164")
      (value "JUMPER-PAD-3-NO2_80")
      (footprint "eagle-import:PAD-JUMPER-3-NO_YES_SILK_80")
      (libsource (lib "eagle-import") (part "JUMPER-PAD-3-NO2_80"))
    )
    (comp (ref "SJ165")
      (value "JUMPER-PAD-2-NO80")
      (footprint "eagle-import:PAD-JUMPER-2-NO_NO_SILK_80")
      (libsource (lib "eagle-import") (part "JUMPER-PAD-2-NO80"))
    )
    (comp (ref "SJ166")
      (value "JUMPER-PAD-2-NO80")
      (footprint "eagle-import:PAD-JUMPER-2-NO_NO_SILK_80")
      (libsource (lib "eagle-import") (part "JUMPER-PAD-2-NO80"))
    )
    (comp (ref "SJ167")
      (value "JUMPER-PAD-3-NO2_80")
      (footprint "eagle-import:PAD-JUMPER-3-NO_YES_SILK_80")
      (libsource (lib "eagle-import") (part "JUMPER-PAD-3-NO2_80"))
    )
    (comp (ref "SJ168")
      (value "JUMPER-PAD-3-NO2_80")
      (footprint "eagle-import:PAD-JUMPER-3-NO_YES_SILK_80")
      (libsource (lib "eagle-import") (part "JUMPER-PAD-3-NO2_80"))
    )
    (comp (ref "SJ169")
      (value "JUMPER-PAD-2-NO80")
      (footprint "eagle-import:PAD-JUMPER-2-NO_NO_SILK_80")
      (libsource (lib "eagle-import") (part "JUMPER-PAD-2-NO80"))
    )
    (comp (ref "SJ170")
      (value "JUMPER-PAD-2-NO80")
      (footprint "eagle-import:PAD-JUMPER-2-NO_NO_SILK_80")
      (libsource (lib "eagle-import") (part "JUMPER-PAD-2-NO80"))
    )
    (comp (ref "SJ171")
      (value "JUMPER-PAD-3-NO2_80")
      (footprint "eagle-import:PAD-JUMPER-3-NO_YES_SILK_80")
      (libsource (lib "eagle-import") (part "JUMPER-PAD-3-NO2_80"))
    )
    (comp (ref "SJ172")
      (value "JUMPER-PAD-3-NO2_80")
      (footprint "eagle-import:PAD-JUMPER-3-NO_YES_SILK_80")
      (libsource (lib "eagle-import") (part "JUMPER-PAD-3-NO2_80"))
    )
    (comp (ref "SJ173")
      (value "JUMPER-PAD-2-NO80")
      (footprint "eagle-import:PAD-JUMPER-2-NO_NO_SILK_80")
      (libsource (lib "eagle-import") (part "JUMPER-PAD-2-NO80"))
    )
    (comp (ref "SJ174")
      (value "JUMPER-PAD-2-NO80")
      (footprint "eagle-import:PAD-JUMPER-2-NO_NO_SILK_80")
      (libsource (lib "eagle-import") (part "JUMPER-PAD-2-NO80"))
    )
    (comp (ref "SJ175")
      (value "JUMPER-PAD-3-NO2_80")
      (footprint "eagle-import:PAD-JUMPER-3-NO_YES_SILK_80")
      (libsource (lib "eagle-import") (part "JUMPER-PAD-3-NO2_80"))
    )
    (comp (ref "SJ176")
      (value "JUMPER-PAD-3-NO2_80")
      (footprint "eagle-import:PAD-JUMPER-3-NO_YES_SILK_80")
      (libsource (lib "eagle-import") (part "JUMPER-PAD-3-NO2_80"))
    )
    (comp (ref "SJ177")
      (value "JUMPER-PAD-2-NO80")
      (footprint "eagle-import:PAD-JUMPER-2-NO_NO_SILK_80")
      (libsource (lib "eagle-import") (part "JUMPER-PAD-2-NO80"))
    )
    (comp (ref "SJ178")
      (value "JUMPER-PAD-2-NO80")
      (footprint "eagle-import:PAD-JUMPER-2-NO_NO_SILK_80")
      (libsource (lib "eagle-import") (part "JUMPER-PAD-2-NO80"))
    )
    (comp (ref "SJ179")
      (value "JUMPER-PAD-3-NO2_80")
      (footprint "eagle-import:PAD-JUMPER-3-NO_YES_SILK_80")
      (libsource (lib "eagle-import") (part "JUMPER-PAD-3-NO2_80"))
    )
    (comp (ref "SJ180")
      (value "JUMPER-PAD-3-NO2_80")
      (footprint "eagle-import:PAD-JUMPER-3-NO_YES_SILK_80")
      (libsource (lib "eagle-import") (part "JUMPER-PAD-3-NO2_80"))
    )
    (comp (ref "SJ181")
      (value "JUMPER-PAD-2-NO80")
      (footprint "eagle-import:PAD-JUMPER-2-NO_NO_SILK_80")
      (libsource (lib "eagle-import") (part "JUMPER-PAD-2-NO80"))
    )
    (comp (ref "SJ182")
      (value "JUMPER-PAD-2-NO80")
      (footprint "eagle-import:PAD-JUMPER-2-NO_NO_SILK_80")
      (libsource (lib "eagle-import") (part "JUMPER-PAD-2-NO80"))
    )
    (comp (ref "SJ183")
      (value "JUMPER-PAD-3-NO2_80")
      (footprint "eagle-import:PAD-JUMPER-3-NO_YES_SILK_80")
      (libsource (lib "eagle-import") (part "JUMPER-PAD-3-NO2_80"))
    )
    (comp (ref "SJ184")
      (value "JUMPER-PAD-3-NO2_80")
      (footprint "eagle-import:PAD-JUMPER-3-NO_YES_SILK_80")
      (libsource (lib "eagle-import") (part "JUMPER-PAD-3-NO2_80"))
    )
    (comp (ref "SJ185")
      (value "JUMPER-PAD-2-NO80")
      (footprint "eagle-import:PAD-JUMPER-2-NO_NO_SILK_80")
      (libsource (lib "eagle-import") (part "JUMPER-PAD-2-NO80"))
    )
    (comp (ref "SJ186")
      (value "JUMPER-PAD-2-NO80")
      (footprint "eagle-import:PAD-JUMPER-2-NO_NO_SILK_80")
      (libsource (lib "eagle-import") (part "JUMPER-PAD-2-NO80"))
    )
    (comp (ref "SJ187")
      (value "JUMPER-PAD-3-NO2_80")
      (footprint "eagle-import:PAD-JUMPER-3-NO_YES_SILK_80")
      (libsource (lib "eagle-import") (part "JUMPER-PAD-3-NO2_80"))
    )
    (comp (ref "SJ188")
      (value "JUMPER-PAD-3-NO2_80")
      (footprint "eagle-import:PAD-JUMPER-3-NO_YES_SILK_80")
      (libsource (lib "eagle-import") (part "JUMPER-PAD-3-NO2_80"))
    )
    (comp (ref "SJ189")
      (value "JUMPER-PAD-2-NO80")
      (footprint "eagle-import:PAD-JUMPER-2-NO_NO_SILK_80")
      (libsource (lib "eagle-import") (part "JUMPER-PAD-2-NO80"))
    )
    (comp (ref "SJ190")
      (value "JUMPER-PAD-2-NO80")
      (footprint "eagle-import:PAD-JUMPER-2-NO_NO_SILK_80")
      (libsource (lib "eagle-import") (part "JUMPER-PAD-2-NO80"))
    )
    (comp (ref "SJ191")
      (value "JUMPER-PAD-3-NO2_80")
      (footprint "eagle-import:PAD-JUMPER-3-NO_YES_SILK_80")
      (libsource (lib "eagle-import") (part "JUMPER-PAD-3-NO2_80"))
    )
    (comp (ref "SJ192")
      (value "JUMPER-PAD-3-NO2_80")
      (footprint "eagle-import:PAD-JUMPER-3-NO_YES_SILK_80")
      (libsource (lib "eagle-import") (part "JUMPER-PAD-3-NO2_80"))
    )
    (comp (ref "SJ193")
      (value "JUMPER-PAD-3-NO3_80")
      (footprint "eagle-import:PAD-JUMPER-3-NO_YES_SILK_ALL_80")
      (libsource (lib "eagle-import") (part "JUMPER-PAD-3-NO3_80"))
    )
    (comp (ref "SJ194")
      (value "JUMPER-PAD-3-NO3_80")
      (footprint "eagle-import:PAD-JUMPER-3-NO_YES_SILK_ALL_80")
      (libsource (lib "eagle-import") (part "JUMPER-PAD-3-NO3_80"))
    )
    (comp (ref "SJ195")
      (value "JUMPER-PAD-3-NO3_80")
      (footprint "eagle-import:PAD-JUMPER-3-NO_YES_SILK_ALL_80")
      (libsource (lib "eagle-import") (part "JUMPER-PAD-3-NO3_80"))
    )
    (comp (ref "SJ196")
      (value "JUMPER-PAD-3-NO3_80")
      (footprint "eagle-import:PAD-JUMPER-3-NO_YES_SILK_ALL_80")
      (libsource (lib "eagle-import") (part "JUMPER-PAD-3-NO3_80"))
    )
    (comp (ref "SJ197")
      (value "JUMPER-PAD-3-NO3_80")
      (footprint "eagle-import:PAD-JUMPER-3-NO_YES_SILK_ALL_80")
      (libsource (lib "eagle-import") (part "JUMPER-PAD-3-NO3_80"))
    )
    (comp (ref "SJ198")
      (value "JUMPER-PAD-3-NO3_80")
      (footprint "eagle-import:PAD-JUMPER-3-NO_YES_SILK_ALL_80")
      (libsource (lib "eagle-import") (part "JUMPER-PAD-3-NO3_80"))
    )
    (comp (ref "SJ199")
      (value "JUMPER-PAD-3-NO3_80")
      (footprint "eagle-import:PAD-JUMPER-3-NO_YES_SILK_ALL_80")
      (libsource (lib "eagle-import") (part "JUMPER-PAD-3-NO3_80"))
    )
    (comp (ref "SJ200")
      (value "JUMPER-PAD-3-NO3_80")
      (footprint "eagle-import:PAD-JUMPER-3-NO_YES_SILK_ALL_80")
      (libsource (lib "eagle-import") (part "JUMPER-PAD-3-NO3_80"))
    )
  )
  (nets
    (net (code "1") (name "GND") (class "Default")
      (node (ref "C101") (pin "2") (pinfunction "2_2") (pintype "passive"))
      (node (ref "C102") (pin "2") (pinfunction "2_2") (pintype "passive"))
      (node (ref "C105") (pin "1") (pinfunction "1_1") (pintype "passive"))
      (node (ref "C106") (pin "1") (pinfunction "1_1") (pintype "passive"))
      (node (ref "C107") (pin "1") (pinfunction "1_1") (pintype "passive"))
      (node (ref "C108") (pin "1") (pinfunction "1_1") (pintype "passive"))
      (node (ref "C125") (pin "2") (pinfunction "2_2") (pintype "passive"))
      (node (ref "C126") (pin "2") (pinfunction "2_2") (pintype "passive"))
      (node (ref "C129") (pin "2") (pinfunction "2_2") (pintype "passive"))
      (node (ref "C130") (pin "2") (pinfunction "2_2") (pintype "passive"))
      (node (ref "C133") (pin "2") (pinfunction "2_2") (pintype "passive"))
      (node (ref "C134") (pin "2") (pinfunction "2_2") (pintype "passive"))
      (node (ref "C137") (pin "2") (pinfunction "2_2") (pintype "passive"))
      (node (ref "C138") (pin "2") (pinfunction "2_2") (pintype "passive"))
      (node (ref "C141") (pin "1") (pinfunction "1_1") (pintype "passive"))
      (node (ref "C142") (pin "1") (pinfunction "1_1") (pintype "passive"))
      (node (ref "C143") (pin "1") (pinfunction "1_1") (pintype "passive"))
      (node (ref "C144") (pin "1") (pinfunction "1_1") (pintype "passive"))
      (node (ref "C161") (pin "2") (pinfunction "2_2") (pintype "passive"))
      (node (ref "C162") (pin "2") (pinfunction "2_2") (pintype "passive"))
      (node (ref "C165") (pin "2") (pinfunction "2_2") (pintype "passive"))
      (node (ref "C166") (pin "2") (pinfunction "2_2") (pintype "passive"))
      (node (ref "C169") (pin "2") (pinfunction "2_2") (pintype "passive"))
      (node (ref "C17") (pin "2") (pinfunction "2_2") (pintype "passive"))
      (node (ref "C170") (pin "2") (pinfunction "2_2") (pintype "passive"))
      (node (ref "C173") (pin "2") (pinfunction "2_2") (pintype "passive"))
      (node (ref "C174") (pin "2") (pinfunction "2_2") (pintype "passive"))
      (node (ref "C177") (pin "1") (pinfunction "1_1") (pintype "passive"))
      (node (ref "C178") (pin "1") (pinfunction "1_1") (pintype "passive"))
      (node (ref "C179") (pin "1") (pinfunction "1_1") (pintype "passive"))
      (node (ref "C18") (pin "2") (pinfunction "2_2") (pintype "passive"))
      (node (ref "C180") (pin "1") (pinfunction "1_1") (pintype "passive"))
      (node (ref "C21") (pin "2") (pinfunction "2_2") (pintype "passive"))
      (node (ref "C22") (pin "2") (pinfunction "2_2") (pintype "passive"))
      (node (ref "C25") (pin "2") (pinfunction "2_2") (pintype "passive"))
      (node (ref "C26") (pin "2") (pinfunction "2_2") (pintype "passive"))
      (node (ref "C29") (pin "2") (pinfunction "2_2") (pintype "passive"))
      (node (ref "C30") (pin "2") (pinfunction "2_2") (pintype "passive"))
      (node (ref "C33") (pin "1") (pinfunction "1_1") (pintype "passive"))
      (node (ref "C34") (pin "1") (pinfunction "1_1") (pintype "passive"))
      (node (ref "C35") (pin "1") (pinfunction "1_1") (pintype "passive"))
      (node (ref "C36") (pin "1") (pinfunction "1_1") (pintype "passive"))
      (node (ref "C53") (pin "2") (pinfunction "2_2") (pintype "passive"))
      (node (ref "C54") (pin "2") (pinfunction "2_2") (pintype "passive"))
      (node (ref "C57") (pin "2") (pinfunction "2_2") (pintype "passive"))
      (node (ref "C58") (pin "2") (pinfunction "2_2") (pintype "passive"))
      (node (ref "C61") (pin "2") (pinfunction "2_2") (pintype "passive"))
      (node (ref "C62") (pin "2") (pinfunction "2_2") (pintype "passive"))
      (node (ref "C65") (pin "2") (pinfunction "2_2") (pintype "passive"))
      (node (ref "C66") (pin "2") (pinfunction "2_2") (pintype "passive"))
      (node (ref "C69") (pin "1") (pinfunction "1_1") (pintype "passive"))
      (node (ref "C70") (pin "1") (pinfunction "1_1") (pintype "passive"))
      (node (ref "C71") (pin "1") (pinfunction "1_1") (pintype "passive"))
      (node (ref "C72") (pin "1") (pinfunction "1_1") (pintype "passive"))
      (node (ref "C89") (pin "2") (pinfunction "2_2") (pintype "passive"))
      (node (ref "C90") (pin "2") (pinfunction "2_2") (pintype "passive"))
      (node (ref "C93") (pin "2") (pinfunction "2_2") (pintype "passive"))
      (node (ref "C94") (pin "2") (pinfunction "2_2") (pintype "passive"))
      (node (ref "C97") (pin "2") (pinfunction "2_2") (pintype "passive"))
      (node (ref "C98") (pin "2") (pinfunction "2_2") (pintype "passive"))
      (node (ref "SJ100") (pin "3") (pinfunction "3_3") (pintype "passive"))
      (node (ref "SJ101") (pin "2") (pinfunction "2_2") (pintype "passive"))
      (node (ref "SJ102") (pin "2") (pinfunction "2_2") (pintype "passive"))
      (node (ref "SJ103") (pin "3") (pinfunction "3_3") (pintype "passive"))
      (node (ref "SJ104") (pin "3") (pinfunction "3_3") (pintype "passive"))
      (node (ref "SJ105") (pin "2") (pinfunction "2_2") (pintype "passive"))
      (node (ref "SJ106") (pin "2") (pinfunction "2_2") (pintype "passive"))
      (node (ref "SJ107") (pin "3") (pinfunction "3_3") (pintype "passive"))
      (node (ref "SJ108") (pin "3") (pinfunction "3_3") (pintype "passive"))
      (node (ref "SJ109") (pin "2") (pinfunction "2_2") (pintype "passive"))
      (node (ref "SJ110") (pin "2") (pinfunction "2_2") (pintype "passive"))
      (node (ref "SJ111") (pin "3") (pinfunction "3_3") (pintype "passive"))
      (node (ref "SJ112") (pin "3") (pinfunction "3_3") (pintype "passive"))
      (node (ref "SJ117") (pin "3") (pinfunction "3_3") (pintype "passive"))
      (node (ref "SJ118") (pin "3") (pinfunction "3_3") (pintype "passive"))
      (node (ref "SJ119") (pin "3") (pinfunction "3_3") (pintype "passive"))
      (node (ref "SJ120") (pin "3") (pinfunction "3_3") (pintype "passive"))
      (node (ref "SJ137") (pin "2") (pinfunction "2_2") (pintype "passive"))
      (node (ref "SJ138") (pin "2") (pinfunction "2_2") (pintype "passive"))
      (node (ref "SJ139") (pin "3") (pinfunction "3_3") (pintype "passive"))
      (node (ref "SJ140") (pin "3") (pinfunction "3_3") (pintype "passive"))
      (node (ref "SJ141") (pin "2") (pinfunction "2_2") (pintype "passive"))
      (node (ref "SJ142") (pin "2") (pinfunction "2_2") (pintype "passive"))
      (node (ref "SJ143") (pin "3") (pinfunction "3_3") (pintype "passive"))
      (node (ref "SJ144") (pin "3") (pinfunction "3_3") (pintype "passive"))
      (node (ref "SJ145") (pin "2") (pinfunction "2_2") (pintype "passive"))
      (node (ref "SJ146") (pin "2") (pinfunction "2_2") (pintype "passive"))
      (node (ref "SJ147") (pin "3") (pinfunction "3_3") (pintype "passive"))
      (node (ref "SJ148") (pin "3") (pinfunction "3_3") (pintype "passive"))
      (node (ref "SJ149") (pin "2") (pinfunction "2_2") (pintype "passive"))
      (node (ref "SJ150") (pin "2") (pinfunction "2_2") (pintype "passive"))
      (node (ref "SJ151") (pin "3") (pinfunction "3_3") (pintype "passive"))
      (node (ref "SJ152") (pin "3") (pinfunction "3_3") (pintype "passive"))
      (node (ref "SJ157") (pin "3") (pinfunction "3_3") (pintype "passive"))
      (node (ref "SJ158") (pin "3") (pinfunction "3_3") (pintype "passive"))
      (node (ref "SJ159") (pin "3") (pinfunction "3_3") (pintype "passive"))
      (node (ref "SJ160") (pin "3") (pinfunction "3_3") (pintype "passive"))
      (node (ref "SJ17") (pin "2") (pinfunction "2_2") (pintype "passive"))
      (node (ref "SJ177") (pin "2") (pinfunction "2_2") (pintype "passive"))
      (node (ref "SJ178") (pin "2") (pinfunction "2_2") (pintype "passive"))
      (node (ref "SJ179") (pin "3") (pinfunction "3_3") (pintype "passive"))
      (node (ref "SJ18") (pin "2") (pinfunction "2_2") (pintype "passive"))
      (node (ref "SJ180") (pin "3") (pinfunction "3_3") (pintype "passive"))
      (node (ref "SJ181") (pin "2") (pinfunction "2_2") (pintype "passive"))
      (node (ref "SJ182") (pin "2") (pinfunction "2_2") (pintype "passive"))
      (node (ref "SJ183") (pin "3") (pinfunction "3_3") (pintype "passive"))
      (node (ref "SJ184") (pin "3") (pinfunction "3_3") (pintype "passive"))
      (node (ref "SJ185") (pin "2") (pinfunction "2_2") (pintype "passive"))
      (node (ref "SJ186") (pin "2") (pinfunction "2_2") (pintype "passive"))
      (node (ref "SJ187") (pin "3") (pinfunction "3_3") (pintype "passive"))
      (node (ref "SJ188") (pin "3") (pinfunction "3_3") (pintype "passive"))
      (node (ref "SJ189") (pin "2") (pinfunction "2_2") (pintype "passive"))
      (node (ref "SJ19") (pin "3") (pinfunction "3_3") (pintype "passive"))
      (node (ref "SJ190") (pin "2") (pinfunction "2_2") (pintype "passive"))
      (node (ref "SJ191") (pin "3") (pinfunction "3_3") (pintype "passive"))
      (node (ref "SJ192") (pin "3") (pinfunction "3_3") (pintype "passive"))
      (node (ref "SJ197") (pin "3") (pinfunction "3_3") (pintype "passive"))
      (node (ref "SJ198") (pin "3") (pinfunction "3_3") (pintype "passive"))
      (node (ref "SJ199") (pin "3") (pinfunction "3_3") (pintype "passive"))
      (node (ref "SJ20") (pin "3") (pinfunction "3_3") (pintype "passive"))
      (node (ref "SJ200") (pin "3") (pinfunction "3_3") (pintype "passive"))
      (node (ref "SJ25") (pin "3") (pinfunction "3_3") (pintype "passive"))
      (node (ref "SJ26") (pin "3") (pinfunction "3_3") (pintype "passive"))
      (node (ref "SJ27") (pin "3") (pinfunction "3_3") (pintype "passive"))
      (node (ref "SJ28") (pin "3") (pinfunction "3_3") (pintype "passive"))
      (node (ref "SJ33") (pin "2") (pinfunction "2_2") (pintype "passive"))
      (node (ref "SJ34") (pin "2") (pinfunction "2_2") (pintype "passive"))
      (node (ref "SJ35") (pin "3") (pinfunction "3_3") (pintype "passive"))
      (node (ref "SJ36") (pin "3") (pinfunction "3_3") (pintype "passive"))
      (node (ref "SJ37") (pin "2") (pinfunction "2_2") (pintype "passive"))
      (node (ref "SJ38") (pin "2") (pinfunction "2_2") (pintype "passive"))
      (node (ref "SJ39") (pin "3") (pinfunction "3_3") (pintype "passive"))
      (node (ref "SJ40") (pin "3") (pinfunction "3_3") (pintype "passive"))
      (node (ref "SJ41") (pin "2") (pinfunction "2_2") (pintype "passive"))
      (node (ref "SJ42") (pin "2") (pinfunction "2_2") (pintype "passive"))
      (node (ref "SJ43") (pin "3") (pinfunction "3_3") (pintype "passive"))
      (node (ref "SJ44") (pin "3") (pinfunction "3_3") (pintype "passive"))
      (node (ref "SJ57") (pin "2") (pinfunction "2_2") (pintype "passive"))
      (node (ref "SJ58") (pin "2") (pinfunction "2_2") (pintype "passive"))
      (node (ref "SJ59") (pin "3") (pinfunction "3_3") (pintype "passive"))
      (node (ref "SJ60") (pin "3") (pinfunction "3_3") (pintype "passive"))
      (node (ref "SJ61") (pin "2") (pinfunction "2_2") (pintype "passive"))
      (node (ref "SJ62") (pin "2") (pinfunction "2_2") (pintype "passive"))
      (node (ref "SJ63") (pin "3") (pinfunction "3_3") (pintype "passive"))
      (node (ref "SJ64") (pin "3") (pinfunction "3_3") (pintype "passive"))
      (node (ref "SJ65") (pin "2") (pinfunction "2_2") (pintype "passive"))
      (node (ref "SJ66") (pin "2") (pinfunction "2_2") (pintype "passive"))
      (node (ref "SJ67") (pin "3") (pinfunction "3_3") (pintype "passive"))
      (node (ref "SJ68") (pin "3") (pinfunction "3_3") (pintype "passive"))
      (node (ref "SJ69") (pin "2") (pinfunction "2_2") (pintype "passive"))
      (node (ref "SJ70") (pin "2") (pinfunction "2_2") (pintype "passive"))
      (node (ref "SJ71") (pin "3") (pinfunction "3_3") (pintype "passive"))
      (node (ref "SJ72") (pin "3") (pinfunction "3_3") (pintype "passive"))
      (node (ref "SJ77") (pin "3") (pinfunction "3_3") (pintype "passive"))
      (node (ref "SJ78") (pin "3") (pinfunction "3_3") (pintype "passive"))
      (node (ref "SJ79") (pin "3") (pinfunction "3_3") (pintype "passive"))
      (node (ref "SJ80") (pin "3") (pinfunction "3_3") (pintype "passive"))
      (node (ref "SJ97") (pin "2") (pinfunction "2_2") (pintype "passive"))
      (node (ref "SJ98") (pin "2") (pinfunction "2_2") (pintype "passive"))
      (node (ref "SJ99") (pin "3") (pinfunction "3_3") (pintype "passive"))
    )
    (net (code "2") (name "Net-(C1-Pad1)") (class "Default")
      (node (ref "C1") (pin "1") (pinfunction "1_1") (pintype "passive"))
      (node (ref "C3") (pin "2") (pinfunction "2_2") (pintype "passive"))
      (node (ref "SJ9") (pin "1") (pinfunction "1_1") (pintype "passive"))
    )
    (net (code "3") (name "Net-(C1-Pad2)") (class "Default")
      (node (ref "C1") (pin "2") (pinfunction "2_2") (pintype "passive"))
      (node (ref "C3") (pin "1") (pinfunction "1_1") (pintype "passive"))
      (node (ref "SJ9") (pin "2") (pinfunction "2_2") (pintype "passive"))
    )
    (net (code "4") (name "Net-(C2-Pad1)") (class "Default")
      (node (ref "C2") (pin "1") (pinfunction "1_1") (pintype "passive"))
      (node (ref "C4") (pin "2") (pinfunction "2_2") (pintype "passive"))
      (node (ref "SJ10") (pin "1") (pinfunction "1_1") (pintype "passive"))
    )
    (net (code "5") (name "Net-(C2-Pad2)") (class "Default")
      (node (ref "C2") (pin "2") (pinfunction "2_2") (pintype "passive"))
      (node (ref "C4") (pin "1") (pinfunction "1_1") (pintype "passive"))
      (node (ref "SJ10") (pin "2") (pinfunction "2_2") (pintype "passive"))
    )
    (net (code "6") (name "Net-(C5-Pad1)") (class "Default")
      (node (ref "C5") (pin "1") (pinfunction "1_1") (pintype "passive"))
      (node (ref "C6") (pin "2") (pinfunction "2_2") (pintype "passive"))
      (node (ref "SJ11") (pin "2") (pinfunction "2_2") (pintype "passive"))
    )
    (net (code "7") (name "Net-(C5-Pad2)") (class "Default")
      (node (ref "C5") (pin "2") (pinfunction "2_2") (pintype "passive"))
      (node (ref "SJ11") (pin "1") (pinfunction "1_1") (pintype "passive"))
    )
    (net (code "8") (name "Net-(C6-Pad1)") (class "Default")
      (node (ref "C6") (pin "1") (pinfunction "1_1") (pintype "passive"))
      (node (ref "SJ11") (pin "3") (pinfunction "3_3") (pintype "passive"))
    )
    (net (code "9") (name "Net-(C7-Pad1)") (class "Default")
      (node (ref "C7") (pin "1") (pinfunction "1_1") (pintype "passive"))
      (node (ref "SJ12") (pin "3") (pinfunction "3_3") (pintype "passive"))
    )
    (net (code "10") (name "Net-(C7-Pad2)") (class "Default")
      (node (ref "C7") (pin "2") (pinfunction "2_2") (pintype "passive"))
      (node (ref "C8") (pin "1") (pinfunction "1_1") (pintype "passive"))
      (node (ref "SJ12") (pin "2") (pinfunction "2_2") (pintype "passive"))
    )
    (net (code "11") (name "Net-(C8-Pad2)") (class "Default")
      (node (ref "C8") (pin "2") (pinfunction "2_2") (pintype "passive"))
      (node (ref "SJ12") (pin "1") (pinfunction "1_1") (pintype "passive"))
    )
    (net (code "12") (name "Net-(C10-Pad1)") (class "Default")
      (node (ref "C10") (pin "1") (pinfunction "1_1") (pintype "passive"))
      (node (ref "C12") (pin "2") (pinfunction "2_2") (pintype "passive"))
      (node (ref "SJ14") (pin "1") (pinfunction "1_1") (pintype "passive"))
    )
    (net (code "13") (name "Net-(C10-Pad2)") (class "Default")
      (node (ref "C10") (pin "2") (pinfunction "2_2") (pintype "passive"))
      (node (ref "C12") (pin "1") (pinfunction "1_1") (pintype "passive"))
      (node (ref "SJ14") (pin "2") (pinfunction "2_2") (pintype "passive"))
    )
    (net (code "14") (name "Net-(C11-Pad1)") (class "Default")
      (node (ref "C11") (pin "1") (pinfunction "1_1") (pintype "passive"))
      (node (ref "C9") (pin "2") (pinfunction "2_2") (pintype "passive"))
      (node (ref "SJ13") (pin "2") (pinfunction "2_2") (pintype "passive"))
    )
    (net (code "15") (name "Net-(C11-Pad2)") (class "Default")
      (node (ref "C11") (pin "2") (pinfunction "2_2") (pintype "passive"))
      (node (ref "C9") (pin "1") (pinfunction "1_1") (pintype "passive"))
      (node (ref "SJ13") (pin "1") (pinfunction "1_1") (pintype "passive"))
    )
    (net (code "16") (name "Net-(C13-Pad1)") (class "Default")
      (node (ref "C13") (pin "1") (pinfunction "1_1") (pintype "passive"))
      (node (ref "C15") (pin "2") (pinfunction "2_2") (pintype "passive"))
      (node (ref "SJ15") (pin "2") (pinfunction "2_2") (pintype "passive"))
    )
    (net (code "17") (name "Net-(C13-Pad2)") (class "Default")
      (node (ref "C13") (pin "2") (pinfunction "2_2") (pintype "passive"))
      (node (ref "SJ15") (pin "1") (pinfunction "1_1") (pintype "passive"))
    )
    (net (code "18") (name "Net-(C14-Pad1)") (class "Default")
      (node (ref "C14") (pin "1") (pinfunction "1_1") (pintype "passive"))
      (node (ref "C16") (pin "2") (pinfunction "2_2") (pintype "passive"))
      (node (ref "SJ16") (pin "2") (pinfunction "2_2") (pintype "passive"))
    )
    (net (code "19") (name "Net-(C14-Pad2)") (class "Default")
      (node (ref "C14") (pin "2") (pinfunction "2_2") (pintype "passive"))
      (node (ref "SJ16") (pin "1") (pinfunction "1_1") (pintype "passive"))
    )
    (net (code "20") (name "Net-(C15-Pad1)") (class "Default")
      (node (ref "C15") (pin "1") (pinfunction "1_1") (pintype "passive"))
      (node (ref "SJ15") (pin "3") (pinfunction "3_3") (pintype "passive"))
    )
    (net (code "21") (name "Net-(C16-Pad1)") (class "Default")
      (node (ref "C16") (pin "1") (pinfunction "1_1") (pintype "passive"))
      (node (ref "SJ16") (pin "3") (pinfunction "3_3") (pintype "passive"))
    )
    (net (code "22") (name "Net-(C17-Pad1)") (class "Default")
      (node (ref "C17") (pin "1") (pinfunction "1_1") (pintype "passive"))
      (node (ref "SJ17") (pin "1") (pinfunction "1_1") (pintype "passive"))
    )
    (net (code "23") (name "Net-(C18-Pad1)") (class "Default")
      (node (ref "C18") (pin "1") (pinfunction "1_1") (pintype "passive"))
      (node (ref "SJ18") (pin "1") (pinfunction "1_1") (pintype "passive"))
    )
    (net (code "24") (name "Net-(C19-Pad1)") (class "Default")
      (node (ref "C19") (pin "1") (pinfunction "1_1") (pintype "passive"))
      (node (ref "SJ19") (pin "2") (pinfunction "2_2") (pintype "passive"))
    )
    (net (code "25") (name "Net-(C19-Pad2)") (class "Default")
      (node (ref "C19") (pin "2") (pinfunction "2_2") (pintype "passive"))
      (node (ref "SJ19") (pin "1") (pinfunction "1_1") (pintype "passive"))
    )
    (net (code "26") (name "Net-(C20-Pad1)") (class "Default")
      (node (ref "C20") (pin "1") (pinfunction "1_1") (pintype "passive"))
      (node (ref "SJ20") (pin "2") (pinfunction "2_2") (pintype "passive"))
    )
    (net (code "27") (name "Net-(C20-Pad2)") (class "Default")
      (node (ref "C20") (pin "2") (pinfunction "2_2") (pintype "passive"))
      (node (ref "SJ20") (pin "1") (pinfunction "1_1") (pintype "passive"))
    )
    (net (code "28") (name "Net-(C21-Pad1)") (class "Default")
      (node (ref "C21") (pin "1") (pinfunction "1_1") (pintype "passive"))
      (node (ref "SJ33") (pin "1") (pinfunction "1_1") (pintype "passive"))
    )
    (net (code "29") (name "Net-(C22-Pad1)") (class "Default")
      (node (ref "C22") (pin "1") (pinfunction "1_1") (pintype "passive"))
      (node (ref "SJ34") (pin "1") (pinfunction "1_1") (pintype "passive"))
    )
    (net (code "30") (name "Net-(C23-Pad1)") (class "Default")
      (node (ref "C23") (pin "1") (pinfunction "1_1") (pintype "passive"))
      (node (ref "SJ35") (pin "2") (pinfunction "2_2") (pintype "passive"))
    )
    (net (code "31") (name "Net-(C23-Pad2)") (class "Default")
      (node (ref "C23") (pin "2") (pinfunction "2_2") (pintype "passive"))
      (node (ref "SJ35") (pin "1") (pinfunction "1_1") (pintype "passive"))
    )
    (net (code "32") (name "Net-(C24-Pad1)") (class "Default")
      (node (ref "C24") (pin "1") (pinfunction "1_1") (pintype "passive"))
      (node (ref "SJ36") (pin "2") (pinfunction "2_2") (pintype "passive"))
    )
    (net (code "33") (name "Net-(C24-Pad2)") (class "Default")
      (node (ref "C24") (pin "2") (pinfunction "2_2") (pintype "passive"))
      (node (ref "SJ36") (pin "1") (pinfunction "1_1") (pintype "passive"))
    )
    (net (code "34") (name "Net-(C25-Pad1)") (class "Default")
      (node (ref "C25") (pin "1") (pinfunction "1_1") (pintype "passive"))
      (node (ref "SJ37") (pin "1") (pinfunction "1_1") (pintype "passive"))
    )
    (net (code "35") (name "Net-(C26-Pad1)") (class "Default")
      (node (ref "C26") (pin "1") (pinfunction "1_1") (pintype "passive"))
      (node (ref "SJ38") (pin "1") (pinfunction "1_1") (pintype "passive"))
    )
    (net (code "36") (name "Net-(C27-Pad1)") (class "Default")
      (node (ref "C27") (pin "1") (pinfunction "1_1") (pintype "passive"))
      (node (ref "C33") (pin "2") (pinfunction "2_2") (pintype "passive"))
      (node (ref "SJ39") (pin "2") (pinfunction "2_2") (pintype "passive"))
    )
    (net (code "37") (name "Net-(C27-Pad2)") (class "Default")
      (node (ref "C27") (pin "2") (pinfunction "2_2") (pintype "passive"))
      (node (ref "SJ39") (pin "1") (pinfunction "1_1") (pintype "passive"))
    )
    (net (code "38") (name "Net-(C28-Pad1)") (class "Default")
      (node (ref "C28") (pin "1") (pinfunction "1_1") (pintype "passive"))
      (node (ref "C34") (pin "2") (pinfunction "2_2") (pintype "passive"))
      (node (ref "SJ40") (pin "2") (pinfunction "2_2") (pintype "passive"))
    )
    (net (code "39") (name "Net-(C28-Pad2)") (class "Default")
      (node (ref "C28") (pin "2") (pinfunction "2_2") (pintype "passive"))
      (node (ref "SJ40") (pin "1") (pinfunction "1_1") (pintype "passive"))
    )
    (net (code "40") (name "Net-(C29-Pad1)") (class "Default")
      (node (ref "C29") (pin "1") (pinfunction "1_1") (pintype "passive"))
      (node (ref "SJ41") (pin "1") (pinfunction "1_1") (pintype "passive"))
    )
    (net (code "41") (name "Net-(C30-Pad1)") (class "Default")
      (node (ref "C30") (pin "1") (pinfunction "1_1") (pintype "passive"))
      (node (ref "SJ42") (pin "1") (pinfunction "1_1") (pintype "passive"))
    )
    (net (code "42") (name "Net-(C31-Pad1)") (class "Default")
      (node (ref "C31") (pin "1") (pinfunction "1_1") (pintype "passive"))
      (node (ref "C35") (pin "2") (pinfunction "2_2") (pintype "passive"))
      (node (ref "SJ43") (pin "2") (pinfunction "2_2") (pintype "passive"))
    )
    (net (code "43") (name "Net-(C31-Pad2)") (class "Default")
      (node (ref "C31") (pin "2") (pinfunction "2_2") (pintype "passive"))
      (node (ref "SJ43") (pin "1") (pinfunction "1_1") (pintype "passive"))
    )
    (net (code "44") (name "Net-(C32-Pad1)") (class "Default")
      (node (ref "C32") (pin "1") (pinfunction "1_1") (pintype "passive"))
      (node (ref "C36") (pin "2") (pinfunction "2_2") (pintype "passive"))
      (node (ref "SJ44") (pin "2") (pinfunction "2_2") (pintype "passive"))
    )
    (net (code "45") (name "Net-(C32-Pad2)") (class "Default")
      (node (ref "C32") (pin "2") (pinfunction "2_2") (pintype "passive"))
      (node (ref "SJ44") (pin "1") (pinfunction "1_1") (pintype "passive"))
    )
    (net (code "46") (name "Net-(C37-Pad1)") (class "Default")
      (node (ref "C37") (pin "1") (pinfunction "1_1") (pintype "passive"))
      (node (ref "C39") (pin "2") (pinfunction "2_2") (pintype "passive"))
      (node (ref "SJ49") (pin "1") (pinfunction "1_1") (pintype "passive"))
    )
    (net (code "47") (name "Net-(C37-Pad2)") (class "Default")
      (node (ref "C37") (pin "2") (pinfunction "2_2") (pintype "passive"))
      (node (ref "C39") (pin "1") (pinfunction "1_1") (pintype "passive"))
      (node (ref "SJ49") (pin "2") (pinfunction "2_2") (pintype "passive"))
    )
    (net (code "48") (name "Net-(C38-Pad1)") (class "Default")
      (node (ref "C38") (pin "1") (pinfunction "1_1") (pintype "passive"))
      (node (ref "C40") (pin "2") (pinfunction "2_2") (pintype "passive"))
      (node (ref "SJ50") (pin "1") (pinfunction "1_1") (pintype "passive"))
    )
    (net (code "49") (name "Net-(C38-Pad2)") (class "Default")
      (node (ref "C38") (pin "2") (pinfunction "2_2") (pintype "passive"))
      (node (ref "C40") (pin "1") (pinfunction "1_1") (pintype "passive"))
      (node (ref "SJ50") (pin "2") (pinfunction "2_2") (pintype "passive"))
    )
    (net (code "50") (name "Net-(C41-Pad1)") (class "Default")
      (node (ref "C41") (pin "1") (pinfunction "1_1") (pintype "passive"))
      (node (ref "C42") (pin "2") (pinfunction "2_2") (pintype "passive"))
      (node (ref "SJ51") (pin "2") (pinfunction "2_2") (pintype "passive"))
    )
    (net (code "51") (name "Net-(C41-Pad2)") (class "Default")
      (node (ref "C41") (pin "2") (pinfunction "2_2") (pintype "passive"))
      (node (ref "SJ51") (pin "1") (pinfunction "1_1") (pintype "passive"))
    )
    (net (code "52") (name "Net-(C42-Pad1)") (class "Default")
      (node (ref "C42") (pin "1") (pinfunction "1_1") (pintype "passive"))
      (node (ref "SJ51") (pin "3") (pinfunction "3_3") (pintype "passive"))
    )
    (net (code "53") (name "Net-(C43-Pad1)") (class "Default")
      (node (ref "C43") (pin "1") (pinfunction "1_1") (pintype "passive"))
      (node (ref "SJ52") (pin "3") (pinfunction "3_3") (pintype "passive"))
    )
    (net (code "54") (name "Net-(C43-Pad2)") (class "Default")
      (node (ref "C43") (pin "2") (pinfunction "2_2") (pintype "passive"))
      (node (ref "C44") (pin "1") (pinfunction "1_1") (pintype "passive"))
      (node (ref "SJ52") (pin "2") (pinfunction "2_2") (pintype "passive"))
    )
    (net (code "55") (name "Net-(C44-Pad2)") (class "Default")
      (node (ref "C44") (pin "2") (pinfunction "2_2") (pintype "passive"))
      (node (ref "SJ52") (pin "1") (pinfunction "1_1") (pintype "passive"))
    )
    (net (code "56") (name "Net-(C45-Pad1)") (class "Default")
      (node (ref "C45") (pin "1") (pinfunction "1_1") (pintype "passive"))
      (node (ref "C47") (pin "2") (pinfunction "2_2") (pintype "passive"))
      (node (ref "SJ53") (pin "1") (pinfunction "1_1") (pintype "passive"))
    )
    (net (code "57") (name "Net-(C45-Pad2)") (class "Default")
      (node (ref "C45") (pin "2") (pinfunction "2_2") (pintype "passive"))
      (node (ref "C47") (pin "1") (pinfunction "1_1") (pintype "passive"))
      (node (ref "SJ53") (pin "2") (pinfunction "2_2") (pintype "passive"))
    )
    (net (code "58") (name "Net-(C46-Pad1)") (class "Default")
      (node (ref "C46") (pin "1") (pinfunction "1_1") (pintype "passive"))
      (node (ref "C48") (pin "2") (pinfunction "2_2") (pintype "passive"))
      (node (ref "SJ54") (pin "1") (pinfunction "1_1") (pintype "passive"))
    )
    (net (code "59") (name "Net-(C46-Pad2)") (class "Default")
      (node (ref "C46") (pin "2") (pinfunction "2_2") (pintype "passive"))
      (node (ref "C48") (pin "1") (pinfunction "1_1") (pintype "passive"))
      (node (ref "SJ54") (pin "2") (pinfunction "2_2") (pintype "passive"))
    )
    (net (code "60") (name "Net-(C49-Pad1)") (class "Default")
      (node (ref "C49") (pin "1") (pinfunction "1_1") (pintype "passive"))
      (node (ref "C51") (pin "2") (pinfunction "2_2") (pintype "passive"))
      (node (ref "SJ55") (pin "2") (pinfunction "2_2") (pintype "passive"))
    )
    (net (code "61") (name "Net-(C49-Pad2)") (class "Default")
      (node (ref "C49") (pin "2") (pinfunction "2_2") (pintype "passive"))
      (node (ref "SJ55") (pin "1") (pinfunction "1_1") (pintype "passive"))
    )
    (net (code "62") (name "Net-(C50-Pad1)") (class "Default")
      (node (ref "C50") (pin "1") (pinfunction "1_1") (pintype "passive"))
      (node (ref "C52") (pin "2") (pinfunction "2_2") (pintype "passive"))
      (node (ref "SJ56") (pin "2") (pinfunction "2_2") (pintype "passive"))
    )
    (net (code "63") (name "Net-(C50-Pad2)") (class "Default")
      (node (ref "C50") (pin "2") (pinfunction "2_2") (pintype "passive"))
      (node (ref "SJ56") (pin "1") (pinfunction "1_1") (pintype "passive"))
    )
    (net (code "64") (name "Net-(C51-Pad1)") (class "Default")
      (node (ref "C51") (pin "1") (pinfunction "1_1") (pintype "passive"))
      (node (ref "SJ55") (pin "3") (pinfunction "3_3") (pintype "passive"))
    )
    (net (code "65") (name "Net-(C52-Pad1)") (class "Default")
      (node (ref "C52") (pin "1") (pinfunction "1_1") (pintype "passive"))
      (node (ref "SJ56") (pin "3") (pinfunction "3_3") (pintype "passive"))
    )
    (net (code "66") (name "Net-(C53-Pad1)") (class "Default")
      (node (ref "C53") (pin "1") (pinfunction "1_1") (pintype "passive"))
      (node (ref "SJ57") (pin "1") (pinfunction "1_1") (pintype "passive"))
    )
    (net (code "67") (name "Net-(C54-Pad1)") (class "Default")
      (node (ref "C54") (pin "1") (pinfunction "1_1") (pintype "passive"))
      (node (ref "SJ58") (pin "1") (pinfunction "1_1") (pintype "passive"))
    )
    (net (code "68") (name "Net-(C55-Pad1)") (class "Default")
      (node (ref "C55") (pin "1") (pinfunction "1_1") (pintype "passive"))
      (node (ref "SJ59") (pin "2") (pinfunction "2_2") (pintype "passive"))
    )
    (net (code "69") (name "Net-(C55-Pad2)") (class "Default")
      (node (ref "C55") (pin "2") (pinfunction "2_2") (pintype "passive"))
      (node (ref "SJ59") (pin "1") (pinfunction "1_1") (pintype "passive"))
    )
    (net (code "70") (name "Net-(C56-Pad1)") (class "Default")
      (node (ref "C56") (pin "1") (pinfunction "1_1") (pintype "passive"))
      (node (ref "SJ60") (pin "2") (pinfunction "2_2") (pintype "passive"))
    )
    (net (code "71") (name "Net-(C56-Pad2)") (class "Default")
      (node (ref "C56") (pin "2") (pinfunction "2_2") (pintype "passive"))
      (node (ref "SJ60") (pin "1") (pinfunction "1_1") (pintype "passive"))
    )
    (net (code "72") (name "Net-(C57-Pad1)") (class "Default")
      (node (ref "C57") (pin "1") (pinfunction "1_1") (pintype "passive"))
      (node (ref "SJ61") (pin "1") (pinfunction "1_1") (pintype "passive"))
    )
    (net (code "73") (name "Net-(C58-Pad1)") (class "Default")
      (node (ref "C58") (pin "1") (pinfunction "1_1") (pintype "passive"))
      (node (ref "SJ62") (pin "1") (pinfunction "1_1") (pintype "passive"))
    )
    (net (code "74") (name "Net-(C59-Pad1)") (class "Default")
      (node (ref "C59") (pin "1") (pinfunction "1_1") (pintype "passive"))
      (node (ref "SJ63") (pin "2") (pinfunction "2_2") (pintype "passive"))
    )
    (net (code "75") (name "Net-(C59-Pad2)") (class "Default")
      (node (ref "C59") (pin "2") (pinfunction "2_2") (pintype "passive"))
      (node (ref "SJ63") (pin "1") (pinfunction "1_1") (pintype "passive"))
    )
    (net (code "76") (name "Net-(C60-Pad1)") (class "Default")
      (node (ref "C60") (pin "1") (pinfunction "1_1") (pintype "passive"))
      (node (ref "SJ64") (pin "2") (pinfunction "2_2") (pintype "passive"))
    )
    (net (code "77") (name "Net-(C60-Pad2)") (class "Default")
      (node (ref "C60") (pin "2") (pinfunction "2_2") (pintype "passive"))
      (node (ref "SJ64") (pin "1") (pinfunction "1_1") (pintype "passive"))
    )
    (net (code "78") (name "Net-(C61-Pad1)") (class "Default")
      (node (ref "C61") (pin "1") (pinfunction "1_1") (pintype "passive"))
      (node (ref "SJ65") (pin "1") (pinfunction "1_1") (pintype "passive"))
    )
    (net (code "79") (name "Net-(C62-Pad1)") (class "Default")
      (node (ref "C62") (pin "1") (pinfunction "1_1") (pintype "passive"))
      (node (ref "SJ66") (pin "1") (pinfunction "1_1") (pintype "passive"))
    )
    (net (code "80") (name "Net-(C63-Pad1)") (class "Default")
      (node (ref "C63") (pin "1") (pinfunction "1_1") (pintype "passive"))
      (node (ref "C69") (pin "2") (pinfunction "2_2") (pintype "passive"))
      (node (ref "SJ67") (pin "2") (pinfunction "2_2") (pintype "passive"))
    )
    (net (code "81") (name "Net-(C63-Pad2)") (class "Default")
      (node (ref "C63") (pin "2") (pinfunction "2_2") (pintype "passive"))
      (node (ref "SJ67") (pin "1") (pinfunction "1_1") (pintype "passive"))
    )
    (net (code "82") (name "Net-(C64-Pad1)") (class "Default")
      (node (ref "C64") (pin "1") (pinfunction "1_1") (pintype "passive"))
      (node (ref "C70") (pin "2") (pinfunction "2_2") (pintype "passive"))
      (node (ref "SJ68") (pin "2") (pinfunction "2_2") (pintype "passive"))
    )
    (net (code "83") (name "Net-(C64-Pad2)") (class "Default")
      (node (ref "C64") (pin "2") (pinfunction "2_2") (pintype "passive"))
      (node (ref "SJ68") (pin "1") (pinfunction "1_1") (pintype "passive"))
    )
    (net (code "84") (name "Net-(C65-Pad1)") (class "Default")
      (node (ref "C65") (pin "1") (pinfunction "1_1") (pintype "passive"))
      (node (ref "SJ69") (pin "1") (pinfunction "1_1") (pintype "passive"))
    )
    (net (code "85") (name "Net-(C66-Pad1)") (class "Default")
      (node (ref "C66") (pin "1") (pinfunction "1_1") (pintype "passive"))
      (node (ref "SJ70") (pin "1") (pinfunction "1_1") (pintype "passive"))
    )
    (net (code "86") (name "Net-(C67-Pad1)") (class "Default")
      (node (ref "C67") (pin "1") (pinfunction "1_1") (pintype "passive"))
      (node (ref "C71") (pin "2") (pinfunction "2_2") (pintype "passive"))
      (node (ref "SJ71") (pin "2") (pinfunction "2_2") (pintype "passive"))
    )
    (net (code "87") (name "Net-(C67-Pad2)") (class "Default")
      (node (ref "C67") (pin "2") (pinfunction "2_2") (pintype "passive"))
      (node (ref "SJ71") (pin "1") (pinfunction "1_1") (pintype "passive"))
    )
    (net (code "88") (name "Net-(C68-Pad1)") (class "Default")
      (node (ref "C68") (pin "1") (pinfunction "1_1") (pintype "passive"))
      (node (ref "C72") (pin "2") (pinfunction "2_2") (pintype "passive"))
      (node (ref "SJ72") (pin "2") (pinfunction "2_2") (pintype "passive"))
    )
    (net (code "89") (name "Net-(C68-Pad2)") (class "Default")
      (node (ref "C68") (pin "2") (pinfunction "2_2") (pintype "passive"))
      (node (ref "SJ72") (pin "1") (pinfunction "1_1") (pintype "passive"))
    )
    (net (code "90") (name "Net-(C73-Pad1)") (class "Default")
      (node (ref "C73") (pin "1") (pinfunction "1_1") (pintype "passive"))
      (node (ref "C75") (pin "2") (pinfunction "2_2") (pintype "passive"))
      (node (ref "SJ89") (pin "1") (pinfunction "1_1") (pintype "passive"))
    )
    (net (code "91") (name "Net-(C73-Pad2)") (class "Default")
      (node (ref "C73") (pin "2") (pinfunction "2_2") (pintype "passive"))
      (node (ref "C75") (pin "1") (pinfunction "1_1") (pintype "passive"))
      (node (ref "SJ89") (pin "2") (pinfunction "2_2") (pintype "passive"))
    )
    (net (code "92") (name "Net-(C74-Pad1)") (class "Default")
      (node (ref "C74") (pin "1") (pinfunction "1_1") (pintype "passive"))
      (node (ref "C76") (pin "2") (pinfunction "2_2") (pintype "passive"))
      (node (ref "SJ90") (pin "1") (pinfunction "1_1") (pintype "passive"))
    )
    (net (code "93") (name "Net-(C74-Pad2)") (class "Default")
      (node (ref "C74") (pin "2") (pinfunction "2_2") (pintype "passive"))
      (node (ref "C76") (pin "1") (pinfunction "1_1") (pintype "passive"))
      (node (ref "SJ90") (pin "2") (pinfunction "2_2") (pintype "passive"))
    )
    (net (code "94") (name "Net-(C77-Pad1)") (class "Default")
      (node (ref "C77") (pin "1") (pinfunction "1_1") (pintype "passive"))
      (node (ref "C78") (pin "2") (pinfunction "2_2") (pintype "passive"))
      (node (ref "SJ91") (pin "2") (pinfunction "2_2") (pintype "passive"))
    )
    (net (code "95") (name "Net-(C77-Pad2)") (class "Default")
      (node (ref "C77") (pin "2") (pinfunction "2_2") (pintype "passive"))
      (node (ref "SJ91") (pin "1") (pinfunction "1_1") (pintype "passive"))
    )
    (net (code "96") (name "Net-(C78-Pad1)") (class "Default")
      (node (ref "C78") (pin "1") (pinfunction "1_1") (pintype "passive"))
      (node (ref "SJ91") (pin "3") (pinfunction "3_3") (pintype "passive"))
    )
    (net (code "97") (name "Net-(C79-Pad1)") (class "Default")
      (node (ref "C79") (pin "1") (pinfunction "1_1") (pintype "passive"))
      (node (ref "SJ92") (pin "3") (pinfunction "3_3") (pintype "passive"))
    )
    (net (code "98") (name "Net-(C79-Pad2)") (class "Default")
      (node (ref "C79") (pin "2") (pinfunction "2_2") (pintype "passive"))
      (node (ref "C80") (pin "1") (pinfunction "1_1") (pintype "passive"))
      (node (ref "SJ92") (pin "2") (pinfunction "2_2") (pintype "passive"))
    )
    (net (code "99") (name "Net-(C80-Pad2)") (class "Default")
      (node (ref "C80") (pin "2") (pinfunction "2_2") (pintype "passive"))
      (node (ref "SJ92") (pin "1") (pinfunction "1_1") (pintype "passive"))
    )
    (net (code "100") (name "Net-(C81-Pad1)") (class "Default")
      (node (ref "C81") (pin "1") (pinfunction "1_1") (pintype "passive"))
      (node (ref "C83") (pin "2") (pinfunction "2_2") (pintype "passive"))
      (node (ref "SJ93") (pin "1") (pinfunction "1_1") (pintype "passive"))
    )
    (net (code "101") (name "Net-(C81-Pad2)") (class "Default")
      (node (ref "C81") (pin "2") (pinfunction "2_2") (pintype "passive"))
      (node (ref "C83") (pin "1") (pinfunction "1_1") (pintype "passive"))
      (node (ref "SJ93") (pin "2") (pinfunction "2_2") (pintype "passive"))
    )
    (net (code "102") (name "Net-(C82-Pad1)") (class "Default")
      (node (ref "C82") (pin "1") (pinfunction "1_1") (pintype "passive"))
      (node (ref "C84") (pin "2") (pinfunction "2_2") (pintype "passive"))
      (node (ref "SJ94") (pin "1") (pinfunction "1_1") (pintype "passive"))
    )
    (net (code "103") (name "Net-(C82-Pad2)") (class "Default")
      (node (ref "C82") (pin "2") (pinfunction "2_2") (pintype "passive"))
      (node (ref "C84") (pin "1") (pinfunction "1_1") (pintype "passive"))
      (node (ref "SJ94") (pin "2") (pinfunction "2_2") (pintype "passive"))
    )
    (net (code "104") (name "Net-(C85-Pad1)") (class "Default")
      (node (ref "C85") (pin "1") (pinfunction "1_1") (pintype "passive"))
      (node (ref "C87") (pin "2") (pinfunction "2_2") (pintype "passive"))
      (node (ref "SJ95") (pin "2") (pinfunction "2_2") (pintype "passive"))
    )
    (net (code "105") (name "Net-(C85-Pad2)") (class "Default")
      (node (ref "C85") (pin "2") (pinfunction "2_2") (pintype "passive"))
      (node (ref "SJ95") (pin "1") (pinfunction "1_1") (pintype "passive"))
    )
    (net (code "106") (name "Net-(C86-Pad1)") (class "Default")
      (node (ref "C86") (pin "1") (pinfunction "1_1") (pintype "passive"))
      (node (ref "C88") (pin "2") (pinfunction "2_2") (pintype "passive"))
      (node (ref "SJ96") (pin "2") (pinfunction "2_2") (pintype "passive"))
    )
    (net (code "107") (name "Net-(C86-Pad2)") (class "Default")
      (node (ref "C86") (pin "2") (pinfunction "2_2") (pintype "passive"))
      (node (ref "SJ96") (pin "1") (pinfunction "1_1") (pintype "passive"))
    )
    (net (code "108") (name "Net-(C87-Pad1)") (class "Default")
      (node (ref "C87") (pin "1") (pinfunction "1_1") (pintype "passive"))
      (node (ref "SJ95") (pin "3") (pinfunction "3_3") (pintype "passive"))
    )
    (net (code "109") (name "Net-(C88-Pad1)") (class "Default")
      (node (ref "C88") (pin "1") (pinfunction "1_1") (pintype "passive"))
      (node (ref "SJ96") (pin "3") (pinfunction "3_3") (pintype "passive"))
    )
    (net (code "110") (name "Net-(C89-Pad1)") (class "Default")
      (node (ref "C89") (pin "1") (pinfunction "1_1") (pintype "passive"))
      (node (ref "SJ97") (pin "1") (pinfunction "1_1") (pintype "passive"))
    )
    (net (code "111") (name "Net-(C90-Pad1)") (class "Default")
      (node (ref "C90") (pin "1") (pinfunction "1_1") (pintype "passive"))
      (node (ref "SJ98") (pin "1") (pinfunction "1_1") (pintype "passive"))
    )
    (net (code "112") (name "Net-(C91-Pad1)") (class "Default")
      (node (ref "C91") (pin "1") (pinfunction "1_1") (pintype "passive"))
      (node (ref "SJ99") (pin "2") (pinfunction "2_2") (pintype "passive"))
    )
    (net (code "113") (name "Net-(C91-Pad2)") (class "Default")
      (node (ref "C91") (pin "2") (pinfunction "2_2") (pintype "passive"))
      (node (ref "SJ99") (pin "1") (pinfunction "1_1") (pintype "passive"))
    )
    (net (code "114") (name "Net-(C92-Pad1)") (class "Default")
      (node (ref "C92") (pin "1") (pinfunction "1_1") (pintype "passive"))
      (node (ref "SJ100") (pin "2") (pinfunction "2_2") (pintype "passive"))
    )
    (net (code "115") (name "Net-(C92-Pad2)") (class "Default")
      (node (ref "C92") (pin "2") (pinfunction "2_2") (pintype "passive"))
      (node (ref "SJ100") (pin "1") (pinfunction "1_1") (pintype "passive"))
    )
    (net (code "116") (name "Net-(C93-Pad1)") (class "Default")
      (node (ref "C93") (pin "1") (pinfunction "1_1") (pintype "passive"))
      (node (ref "SJ101") (pin "1") (pinfunction "1_1") (pintype "passive"))
    )
    (net (code "117") (name "Net-(C94-Pad1)") (class "Default")
      (node (ref "C94") (pin "1") (pinfunction "1_1") (pintype "passive"))
      (node (ref "SJ102") (pin "1") (pinfunction "1_1") (pintype "passive"))
    )
    (net (code "118") (name "Net-(C95-Pad1)") (class "Default")
      (node (ref "C95") (pin "1") (pinfunction "1_1") (pintype "passive"))
      (node (ref "SJ103") (pin "2") (pinfunction "2_2") (pintype "passive"))
    )
    (net (code "119") (name "Net-(C95-Pad2)") (class "Default")
      (node (ref "C95") (pin "2") (pinfunction "2_2") (pintype "passive"))
      (node (ref "SJ103") (pin "1") (pinfunction "1_1") (pintype "passive"))
    )
    (net (code "120") (name "Net-(C96-Pad1)") (class "Default")
      (node (ref "C96") (pin "1") (pinfunction "1_1") (pintype "passive"))
      (node (ref "SJ104") (pin "2") (pinfunction "2_2") (pintype "passive"))
    )
    (net (code "121") (name "Net-(C96-Pad2)") (class "Default")
      (node (ref "C96") (pin "2") (pinfunction "2_2") (pintype "passive"))
      (node (ref "SJ104") (pin "1") (pinfunction "1_1") (pintype "passive"))
    )
    (net (code "122") (name "Net-(C97-Pad1)") (class "Default")
      (node (ref "C97") (pin "1") (pinfunction "1_1") (pintype "passive"))
      (node (ref "SJ105") (pin "1") (pinfunction "1_1") (pintype "passive"))
    )
    (net (code "123") (name "Net-(C98-Pad1)") (class "Default")
      (node (ref "C98") (pin "1") (pinfunction "1_1") (pintype "passive"))
      (node (ref "SJ106") (pin "1") (pinfunction "1_1") (pintype "passive"))
    )
    (net (code "124") (name "Net-(C99-Pad2)") (class "Default")
      (node (ref "C99") (pin "2") (pinfunction "2_2") (pintype "passive"))
      (node (ref "SJ107") (pin "1") (pinfunction "1_1") (pintype "passive"))
    )
    (net (code "125") (name "Net-(C100-Pad1)") (class "Default")
      (node (ref "C100") (pin "1") (pinfunction "1_1") (pintype "passive"))
      (node (ref "C106") (pin "2") (pinfunction "2_2") (pintype "passive"))
      (node (ref "SJ108") (pin "2") (pinfunction "2_2") (pintype "passive"))
    )
    (net (code "126") (name "Net-(C100-Pad2)") (class "Default")
      (node (ref "C100") (pin "2") (pinfunction "2_2") (pintype "passive"))
      (node (ref "SJ108") (pin "1") (pinfunction "1_1") (pintype "passive"))
    )
    (net (code "127") (name "Net-(C101-Pad1)") (class "Default")
      (node (ref "C101") (pin "1") (pinfunction "1_1") (pintype "passive"))
      (node (ref "SJ109") (pin "1") (pinfunction "1_1") (pintype "passive"))
    )
    (net (code "128") (name "Net-(C102-Pad1)") (class "Default")
      (node (ref "C102") (pin "1") (pinfunction "1_1") (pintype "passive"))
      (node (ref "SJ110") (pin "1") (pinfunction "1_1") (pintype "passive"))
    )
    (net (code "129") (name "Net-(C103-Pad1)") (class "Default")
      (node (ref "C103") (pin "1") (pinfunction "1_1") (pintype "passive"))
      (node (ref "C107") (pin "2") (pinfunction "2_2") (pintype "passive"))
      (node (ref "SJ111") (pin "2") (pinfunction "2_2") (pintype "passive"))
    )
    (net (code "130") (name "Net-(C103-Pad2)") (class "Default")
      (node (ref "C103") (pin "2") (pinfunction "2_2") (pintype "passive"))
      (node (ref "SJ111") (pin "1") (pinfunction "1_1") (pintype "passive"))
    )
    (net (code "131") (name "Net-(C104-Pad1)") (class "Default")
      (node (ref "C104") (pin "1") (pinfunction "1_1") (pintype "passive"))
      (node (ref "C108") (pin "2") (pinfunction "2_2") (pintype "passive"))
      (node (ref "SJ112") (pin "2") (pinfunction "2_2") (pintype "passive"))
    )
    (net (code "132") (name "Net-(C104-Pad2)") (class "Default")
      (node (ref "C104") (pin "2") (pinfunction "2_2") (pintype "passive"))
      (node (ref "SJ112") (pin "1") (pinfunction "1_1") (pintype "passive"))
    )
    (net (code "133") (name "Net-(C105-Pad2)") (class "Default")
      (node (ref "C105") (pin "2") (pinfunction "2_2") (pintype "passive"))
      (node (ref "C99") (pin "1") (pinfunction "1_1") (pintype "passive"))
      (node (ref "SJ107") (pin "2") (pinfunction "2_2") (pintype "passive"))
    )
    (net (code "134") (name "Net-(C109-Pad1)") (class "Default")
      (node (ref "C109") (pin "1") (pinfunction "1_1") (pintype "passive"))
      (node (ref "C111") (pin "2") (pinfunction "2_2") (pintype "passive"))
      (node (ref "SJ129") (pin "1") (pinfunction "1_1") (pintype "passive"))
    )
    (net (code "135") (name "Net-(C109-Pad2)") (class "Default")
      (node (ref "C109") (pin "2") (pinfunction "2_2") (pintype "passive"))
      (node (ref "C111") (pin "1") (pinfunction "1_1") (pintype "passive"))
      (node (ref "SJ129") (pin "2") (pinfunction "2_2") (pintype "passive"))
    )
    (net (code "136") (name "Net-(C110-Pad1)") (class "Default")
      (node (ref "C110") (pin "1") (pinfunction "1_1") (pintype "passive"))
      (node (ref "C112") (pin "2") (pinfunction "2_2") (pintype "passive"))
      (node (ref "SJ130") (pin "1") (pinfunction "1_1") (pintype "passive"))
    )
    (net (code "137") (name "Net-(C110-Pad2)") (class "Default")
      (node (ref "C110") (pin "2") (pinfunction "2_2") (pintype "passive"))
      (node (ref "C112") (pin "1") (pinfunction "1_1") (pintype "passive"))
      (node (ref "SJ130") (pin "2") (pinfunction "2_2") (pintype "passive"))
    )
    (net (code "138") (name "Net-(C113-Pad1)") (class "Default")
      (node (ref "C113") (pin "1") (pinfunction "1_1") (pintype "passive"))
      (node (ref "C114") (pin "2") (pinfunction "2_2") (pintype "passive"))
      (node (ref "SJ131") (pin "2") (pinfunction "2_2") (pintype "passive"))
    )
    (net (code "139") (name "Net-(C113-Pad2)") (class "Default")
      (node (ref "C113") (pin "2") (pinfunction "2_2") (pintype "passive"))
      (node (ref "SJ131") (pin "1") (pinfunction "1_1") (pintype "passive"))
    )
    (net (code "140") (name "Net-(C114-Pad1)") (class "Default")
      (node (ref "C114") (pin "1") (pinfunction "1_1") (pintype "passive"))
      (node (ref "SJ131") (pin "3") (pinfunction "3_3") (pintype "passive"))
    )
    (net (code "141") (name "Net-(C115-Pad1)") (class "Default")
      (node (ref "C115") (pin "1") (pinfunction "1_1") (pintype "passive"))
      (node (ref "SJ132") (pin "3") (pinfunction "3_3") (pintype "passive"))
    )
    (net (code "142") (name "Net-(C115-Pad2)") (class "Default")
      (node (ref "C115") (pin "2") (pinfunction "2_2") (pintype "passive"))
      (node (ref "C116") (pin "1") (pinfunction "1_1") (pintype "passive"))
      (node (ref "SJ132") (pin "2") (pinfunction "2_2") (pintype "passive"))
    )
    (net (code "143") (name "Net-(C116-Pad2)") (class "Default")
      (node (ref "C116") (pin "2") (pinfunction "2_2") (pintype "passive"))
      (node (ref "SJ132") (pin "1") (pinfunction "1_1") (pintype "passive"))
    )
    (net (code "144") (name "Net-(C117-Pad1)") (class "Default")
      (node (ref "C117") (pin "1") (pinfunction "1_1") (pintype "passive"))
      (node (ref "C119") (pin "2") (pinfunction "2_2") (pintype "passive"))
      (node (ref "SJ133") (pin "1") (pinfunction "1_1") (pintype "passive"))
    )
    (net (code "145") (name "Net-(C117-Pad2)") (class "Default")
      (node (ref "C117") (pin "2") (pinfunction "2_2") (pintype "passive"))
      (node (ref "C119") (pin "1") (pinfunction "1_1") (pintype "passive"))
      (node (ref "SJ133") (pin "2") (pinfunction "2_2") (pintype "passive"))
    )
    (net (code "146") (name "Net-(C118-Pad1)") (class "Default")
      (node (ref "C118") (pin "1") (pinfunction "1_1") (pintype "passive"))
      (node (ref "C120") (pin "2") (pinfunction "2_2") (pintype "passive"))
      (node (ref "SJ134") (pin "1") (pinfunction "1_1") (pintype "passive"))
    )
    (net (code "147") (name "Net-(C118-Pad2)") (class "Default")
      (node (ref "C118") (pin "2") (pinfunction "2_2") (pintype "passive"))
      (node (ref "C120") (pin "1") (pinfunction "1_1") (pintype "passive"))
      (node (ref "SJ134") (pin "2") (pinfunction "2_2") (pintype "passive"))
    )
    (net (code "148") (name "Net-(C121-Pad1)") (class "Default")
      (node (ref "C121") (pin "1") (pinfunction "1_1") (pintype "passive"))
      (node (ref "C123") (pin "2") (pinfunction "2_2") (pintype "passive"))
      (node (ref "SJ135") (pin "2") (pinfunction "2_2") (pintype "passive"))
    )
    (net (code "149") (name "Net-(C121-Pad2)") (class "Default")
      (node (ref "C121") (pin "2") (pinfunction "2_2") (pintype "passive"))
      (node (ref "SJ135") (pin "1") (pinfunction "1_1") (pintype "passive"))
    )
    (net (code "150") (name "Net-(C122-Pad1)") (class "Default")
      (node (ref "C122") (pin "1") (pinfunction "1_1") (pintype "passive"))
      (node (ref "C124") (pin "2") (pinfunction "2_2") (pintype "passive"))
      (node (ref "SJ136") (pin "2") (pinfunction "2_2") (pintype "passive"))
    )
    (net (code "151") (name "Net-(C122-Pad2)") (class "Default")
      (node (ref "C122") (pin "2") (pinfunction "2_2") (pintype "passive"))
      (node (ref "SJ136") (pin "1") (pinfunction "1_1") (pintype "passive"))
    )
    (net (code "152") (name "Net-(C123-Pad1)") (class "Default")
      (node (ref "C123") (pin "1") (pinfunction "1_1") (pintype "passive"))
      (node (ref "SJ135") (pin "3") (pinfunction "3_3") (pintype "passive"))
    )
    (net (code "153") (name "Net-(C124-Pad1)") (class "Default")
      (node (ref "C124") (pin "1") (pinfunction "1_1") (pintype "passive"))
      (node (ref "SJ136") (pin "3") (pinfunction "3_3") (pintype "passive"))
    )
    (net (code "154") (name "Net-(C125-Pad1)") (class "Default")
      (node (ref "C125") (pin "1") (pinfunction "1_1") (pintype "passive"))
      (node (ref "SJ137") (pin "1") (pinfunction "1_1") (pintype "passive"))
    )
    (net (code "155") (name "Net-(C126-Pad1)") (class "Default")
      (node (ref "C126") (pin "1") (pinfunction "1_1") (pintype "passive"))
      (node (ref "SJ138") (pin "1") (pinfunction "1_1") (pintype "passive"))
    )
    (net (code "156") (name "Net-(C127-Pad1)") (class "Default")
      (node (ref "C127") (pin "1") (pinfunction "1_1") (pintype "passive"))
      (node (ref "SJ139") (pin "2") (pinfunction "2_2") (pintype "passive"))
    )
    (net (code "157") (name "Net-(C127-Pad2)") (class "Default")
      (node (ref "C127") (pin "2") (pinfunction "2_2") (pintype "passive"))
      (node (ref "SJ139") (pin "1") (pinfunction "1_1") (pintype "passive"))
    )
    (net (code "158") (name "Net-(C128-Pad1)") (class "Default")
      (node (ref "C128") (pin "1") (pinfunction "1_1") (pintype "passive"))
      (node (ref "SJ140") (pin "2") (pinfunction "2_2") (pintype "passive"))
    )
    (net (code "159") (name "Net-(C128-Pad2)") (class "Default")
      (node (ref "C128") (pin "2") (pinfunction "2_2") (pintype "passive"))
      (node (ref "SJ140") (pin "1") (pinfunction "1_1") (pintype "passive"))
    )
    (net (code "160") (name "Net-(C129-Pad1)") (class "Default")
      (node (ref "C129") (pin "1") (pinfunction "1_1") (pintype "passive"))
      (node (ref "SJ141") (pin "1") (pinfunction "1_1") (pintype "passive"))
    )
    (net (code "161") (name "Net-(C130-Pad1)") (class "Default")
      (node (ref "C130") (pin "1") (pinfunction "1_1") (pintype "passive"))
      (node (ref "SJ142") (pin "1") (pinfunction "1_1") (pintype "passive"))
    )
    (net (code "162") (name "Net-(C131-Pad1)") (class "Default")
      (node (ref "C131") (pin "1") (pinfunction "1_1") (pintype "passive"))
      (node (ref "SJ143") (pin "2") (pinfunction "2_2") (pintype "passive"))
    )
    (net (code "163") (name "Net-(C131-Pad2)") (class "Default")
      (node (ref "C131") (pin "2") (pinfunction "2_2") (pintype "passive"))
      (node (ref "SJ143") (pin "1") (pinfunction "1_1") (pintype "passive"))
    )
    (net (code "164") (name "Net-(C132-Pad1)") (class "Default")
      (node (ref "C132") (pin "1") (pinfunction "1_1") (pintype "passive"))
      (node (ref "SJ144") (pin "2") (pinfunction "2_2") (pintype "passive"))
    )
    (net (code "165") (name "Net-(C132-Pad2)") (class "Default")
      (node (ref "C132") (pin "2") (pinfunction "2_2") (pintype "passive"))
      (node (ref "SJ144") (pin "1") (pinfunction "1_1") (pintype "passive"))
    )
    (net (code "166") (name "Net-(C133-Pad1)") (class "Default")
      (node (ref "C133") (pin "1") (pinfunction "1_1") (pintype "passive"))
      (node (ref "SJ145") (pin "1") (pinfunction "1_1") (pintype "passive"))
    )
    (net (code "167") (name "Net-(C134-Pad1)") (class "Default")
      (node (ref "C134") (pin "1") (pinfunction "1_1") (pintype "passive"))
      (node (ref "SJ146") (pin "1") (pinfunction "1_1") (pintype "passive"))
    )
    (net (code "168") (name "Net-(C135-Pad1)") (class "Default")
      (node (ref "C135") (pin "1") (pinfunction "1_1") (pintype "passive"))
      (node (ref "C141") (pin "2") (pinfunction "2_2") (pintype "passive"))
      (node (ref "SJ147") (pin "2") (pinfunction "2_2") (pintype "passive"))
    )
    (net (code "169") (name "Net-(C135-Pad2)") (class "Default")
      (node (ref "C135") (pin "2") (pinfunction "2_2") (pintype "passive"))
      (node (ref "SJ147") (pin "1") (pinfunction "1_1") (pintype "passive"))
    )
    (net (code "170") (name "Net-(C136-Pad1)") (class "Default")
      (node (ref "C136") (pin "1") (pinfunction "1_1") (pintype "passive"))
      (node (ref "C142") (pin "2") (pinfunction "2_2") (pintype "passive"))
      (node (ref "SJ148") (pin "2") (pinfunction "2_2") (pintype "passive"))
    )
    (net (code "171") (name "Net-(C136-Pad2)") (class "Default")
      (node (ref "C136") (pin "2") (pinfunction "2_2") (pintype "passive"))
      (node (ref "SJ148") (pin "1") (pinfunction "1_1") (pintype "passive"))
    )
    (net (code "172") (name "Net-(C137-Pad1)") (class "Default")
      (node (ref "C137") (pin "1") (pinfunction "1_1") (pintype "passive"))
      (node (ref "SJ149") (pin "1") (pinfunction "1_1") (pintype "passive"))
    )
    (net (code "173") (name "Net-(C138-Pad1)") (class "Default")
      (node (ref "C138") (pin "1") (pinfunction "1_1") (pintype "passive"))
      (node (ref "SJ150") (pin "1") (pinfunction "1_1") (pintype "passive"))
    )
    (net (code "174") (name "Net-(C139-Pad1)") (class "Default")
      (node (ref "C139") (pin "1") (pinfunction "1_1") (pintype "passive"))
      (node (ref "C143") (pin "2") (pinfunction "2_2") (pintype "passive"))
      (node (ref "SJ151") (pin "2") (pinfunction "2_2") (pintype "passive"))
    )
    (net (code "175") (name "Net-(C139-Pad2)") (class "Default")
      (node (ref "C139") (pin "2") (pinfunction "2_2") (pintype "passive"))
      (node (ref "SJ151") (pin "1") (pinfunction "1_1") (pintype "passive"))
    )
    (net (code "176") (name "Net-(C140-Pad1)") (class "Default")
      (node (ref "C140") (pin "1") (pinfunction "1_1") (pintype "passive"))
      (node (ref "C144") (pin "2") (pinfunction "2_2") (pintype "passive"))
      (node (ref "SJ152") (pin "2") (pinfunction "2_2") (pintype "passive"))
    )
    (net (code "177") (name "Net-(C140-Pad2)") (class "Default")
      (node (ref "C140") (pin "2") (pinfunction "2_2") (pintype "passive"))
      (node (ref "SJ152") (pin "1") (pinfunction "1_1") (pintype "passive"))
    )
    (net (code "178") (name "Net-(C145-Pad1)") (class "Default")
      (node (ref "C145") (pin "1") (pinfunction "1_1") (pintype "passive"))
      (node (ref "C147") (pin "2") (pinfunction "2_2") (pintype "passive"))
      (node (ref "SJ169") (pin "1") (pinfunction "1_1") (pintype "passive"))
    )
    (net (code "179") (name "Net-(C145-Pad2)") (class "Default")
      (node (ref "C145") (pin "2") (pinfunction "2_2") (pintype "passive"))
      (node (ref "C147") (pin "1") (pinfunction "1_1") (pintype "passive"))
      (node (ref "SJ169") (pin "2") (pinfunction "2_2") (pintype "passive"))
    )
    (net (code "180") (name "Net-(C146-Pad1)") (class "Default")
      (node (ref "C146") (pin "1") (pinfunction "1_1") (pintype "passive"))
      (node (ref "C148") (pin "2") (pinfunction "2_2") (pintype "passive"))
      (node (ref "SJ170") (pin "1") (pinfunction "1_1") (pintype "passive"))
    )
    (net (code "181") (name "Net-(C146-Pad2)") (class "Default")
      (node (ref "C146") (pin "2") (pinfunction "2_2") (pintype "passive"))
      (node (ref "C148") (pin "1") (pinfunction "1_1") (pintype "passive"))
      (node (ref "SJ170") (pin "2") (pinfunction "2_2") (pintype "passive"))
    )
    (net (code "182") (name "Net-(C149-Pad1)") (class "Default")
      (node (ref "C149") (pin "1") (pinfunction "1_1") (pintype "passive"))
      (node (ref "C150") (pin "2") (pinfunction "2_2") (pintype "passive"))
      (node (ref "SJ171") (pin "2") (pinfunction "2_2") (pintype "passive"))
    )
    (net (code "183") (name "Net-(C149-Pad2)") (class "Default")
      (node (ref "C149") (pin "2") (pinfunction "2_2") (pintype "passive"))
      (node (ref "SJ171") (pin "1") (pinfunction "1_1") (pintype "passive"))
    )
    (net (code "184") (name "Net-(C150-Pad1)") (class "Default")
      (node (ref "C150") (pin "1") (pinfunction "1_1") (pintype "passive"))
      (node (ref "SJ171") (pin "3") (pinfunction "3_3") (pintype "passive"))
    )
    (net (code "185") (name "Net-(C151-Pad1)") (class "Default")
      (node (ref "C151") (pin "1") (pinfunction "1_1") (pintype "passive"))
      (node (ref "SJ172") (pin "3") (pinfunction "3_3") (pintype "passive"))
    )
    (net (code "186") (name "Net-(C151-Pad2)") (class "Default")
      (node (ref "C151") (pin "2") (pinfunction "2_2") (pintype "passive"))
      (node (ref "C152") (pin "1") (pinfunction "1_1") (pintype "passive"))
      (node (ref "SJ172") (pin "2") (pinfunction "2_2") (pintype "passive"))
    )
    (net (code "187") (name "Net-(C152-Pad2)") (class "Default")
      (node (ref "C152") (pin "2") (pinfunction "2_2") (pintype "passive"))
      (node (ref "SJ172") (pin "1") (pinfunction "1_1") (pintype "passive"))
    )
    (net (code "188") (name "Net-(C153-Pad1)") (class "Default")
      (node (ref "C153") (pin "1") (pinfunction "1_1") (pintype "passive"))
      (node (ref "C155") (pin "2") (pinfunction "2_2") (pintype "passive"))
      (node (ref "SJ173") (pin "1") (pinfunction "1_1") (pintype "passive"))
    )
    (net (code "189") (name "Net-(C153-Pad2)") (class "Default")
      (node (ref "C153") (pin "2") (pinfunction "2_2") (pintype "passive"))
      (node (ref "C155") (pin "1") (pinfunction "1_1") (pintype "passive"))
      (node (ref "SJ173") (pin "2") (pinfunction "2_2") (pintype "passive"))
    )
    (net (code "190") (name "Net-(C154-Pad1)") (class "Default")
      (node (ref "C154") (pin "1") (pinfunction "1_1") (pintype "passive"))
      (node (ref "C156") (pin "2") (pinfunction "2_2") (pintype "passive"))
      (node (ref "SJ174") (pin "1") (pinfunction "1_1") (pintype "passive"))
    )
    (net (code "191") (name "Net-(C154-Pad2)") (class "Default")
      (node (ref "C154") (pin "2") (pinfunction "2_2") (pintype "passive"))
      (node (ref "C156") (pin "1") (pinfunction "1_1") (pintype "passive"))
      (node (ref "SJ174") (pin "2") (pinfunction "2_2") (pintype "passive"))
    )
    (net (code "192") (name "Net-(C157-Pad1)") (class "Default")
      (node (ref "C157") (pin "1") (pinfunction "1_1") (pintype "passive"))
      (node (ref "C159") (pin "2") (pinfunction "2_2") (pintype "passive"))
      (node (ref "SJ175") (pin "2") (pinfunction "2_2") (pintype "passive"))
    )
    (net (code "193") (name "Net-(C157-Pad2)") (class "Default")
      (node (ref "C157") (pin "2") (pinfunction "2_2") (pintype "passive"))
      (node (ref "SJ175") (pin "1") (pinfunction "1_1") (pintype "passive"))
    )
    (net (code "194") (name "Net-(C158-Pad1)") (class "Default")
      (node (ref "C158") (pin "1") (pinfunction "1_1") (pintype "passive"))
      (node (ref "C160") (pin "2") (pinfunction "2_2") (pintype "passive"))
      (node (ref "SJ176") (pin "2") (pinfunction "2_2") (pintype "passive"))
    )
    (net (code "195") (name "Net-(C158-Pad2)") (class "Default")
      (node (ref "C158") (pin "2") (pinfunction "2_2") (pintype "passive"))
      (node (ref "SJ176") (pin "1") (pinfunction "1_1") (pintype "passive"))
    )
    (net (code "196") (name "Net-(C159-Pad1)") (class "Default")
      (node (ref "C159") (pin "1") (pinfunction "1_1") (pintype "passive"))
      (node (ref "SJ175") (pin "3") (pinfunction "3_3") (pintype "passive"))
    )
    (net (code "197") (name "Net-(C160-Pad1)") (class "Default")
      (node (ref "C160") (pin "1") (pinfunction "1_1") (pintype "passive"))
      (node (ref "SJ176") (pin "3") (pinfunction "3_3") (pintype "passive"))
    )
    (net (code "198") (name "Net-(C161-Pad1)") (class "Default")
      (node (ref "C161") (pin "1") (pinfunction "1_1") (pintype "passive"))
      (node (ref "SJ177") (pin "1") (pinfunction "1_1") (pintype "passive"))
    )
    (net (code "199") (name "Net-(C162-Pad1)") (class "Default")
      (node (ref "C162") (pin "1") (pinfunction "1_1") (pintype "passive"))
      (node (ref "SJ178") (pin "1") (pinfunction "1_1") (pintype "passive"))
    )
    (net (code "200") (name "Net-(C163-Pad1)") (class "Default")
      (node (ref "C163") (pin "1") (pinfunction "1_1") (pintype "passive"))
      (node (ref "SJ179") (pin "2") (pinfunction "2_2") (pintype "passive"))
    )
    (net (code "201") (name "Net-(C163-Pad2)") (class "Default")
      (node (ref "C163") (pin "2") (pinfunction "2_2") (pintype "passive"))
      (node (ref "SJ179") (pin "1") (pinfunction "1_1") (pintype "passive"))
    )
    (net (code "202") (name "Net-(C164-Pad1)") (class "Default")
      (node (ref "C164") (pin "1") (pinfunction "1_1") (pintype "passive"))
      (node (ref "SJ180") (pin "2") (pinfunction "2_2") (pintype "passive"))
    )
    (net (code "203") (name "Net-(C164-Pad2)") (class "Default")
      (node (ref "C164") (pin "2") (pinfunction "2_2") (pintype "passive"))
      (node (ref "SJ180") (pin "1") (pinfunction "1_1") (pintype "passive"))
    )
    (net (code "204") (name "Net-(C165-Pad1)") (class "Default")
      (node (ref "C165") (pin "1") (pinfunction "1_1") (pintype "passive"))
      (node (ref "SJ181") (pin "1") (pinfunction "1_1") (pintype "passive"))
    )
    (net (code "205") (name "Net-(C166-Pad1)") (class "Default")
      (node (ref "C166") (pin "1") (pinfunction "1_1") (pintype "passive"))
      (node (ref "SJ182") (pin "1") (pinfunction "1_1") (pintype "passive"))
    )
    (net (code "206") (name "Net-(C167-Pad1)") (class "Default")
      (node (ref "C167") (pin "1") (pinfunction "1_1") (pintype "passive"))
      (node (ref "SJ183") (pin "2") (pinfunction "2_2") (pintype "passive"))
    )
    (net (code "207") (name "Net-(C167-Pad2)") (class "Default")
      (node (ref "C167") (pin "2") (pinfunction "2_2") (pintype "passive"))
      (node (ref "SJ183") (pin "1") (pinfunction "1_1") (pintype "passive"))
    )
    (net (code "208") (name "Net-(C168-Pad1)") (class "Default")
      (node (ref "C168") (pin "1") (pinfunction "1_1") (pintype "passive"))
      (node (ref "SJ184") (pin "2") (pinfunction "2_2") (pintype "passive"))
    )
    (net (code "209") (name "Net-(C168-Pad2)") (class "Default")
      (node (ref "C168") (pin "2") (pinfunction "2_2") (pintype "passive"))
      (node (ref "SJ184") (pin "1") (pinfunction "1_1") (pintype "passive"))
    )
    (net (code "210") (name "Net-(C169-Pad1)") (class "Default")
      (node (ref "C169") (pin "1") (pinfunction "1_1") (pintype "passive"))
      (node (ref "SJ185") (pin "1") (pinfunction "1_1") (pintype "passive"))
    )
    (net (code "211") (name "Net-(C170-Pad1)") (class "Default")
      (node (ref "C170") (pin "1") (pinfunction "1_1") (pintype "passive"))
      (node (ref "SJ186") (pin "1") (pinfunction "1_1") (pintype "passive"))
    )
    (net (code "212") (name "Net-(C171-Pad1)") (class "Default")
      (node (ref "C171") (pin "1") (pinfunction "1_1") (pintype "passive"))
      (node (ref "C177") (pin "2") (pinfunction "2_2") (pintype "passive"))
      (node (ref "SJ187") (pin "2") (pinfunction "2_2") (pintype "passive"))
    )
    (net (code "213") (name "Net-(C171-Pad2)") (class "Default")
      (node (ref "C171") (pin "2") (pinfunction "2_2") (pintype "passive"))
      (node (ref "SJ187") (pin "1") (pinfunction "1_1") (pintype "passive"))
    )
    (net (code "214") (name "Net-(C172-Pad1)") (class "Default")
      (node (ref "C172") (pin "1") (pinfunction "1_1") (pintype "passive"))
      (node (ref "C178") (pin "2") (pinfunction "2_2") (pintype "passive"))
      (node (ref "SJ188") (pin "2") (pinfunction "2_2") (pintype "passive"))
    )
    (net (code "215") (name "Net-(C172-Pad2)") (class "Default")
      (node (ref "C172") (pin "2") (pinfunction "2_2") (pintype "passive"))
      (node (ref "SJ188") (pin "1") (pinfunction "1_1") (pintype "passive"))
    )
    (net (code "216") (name "Net-(C173-Pad1)") (class "Default")
      (node (ref "C173") (pin "1") (pinfunction "1_1") (pintype "passive"))
      (node (ref "SJ189") (pin "1") (pinfunction "1_1") (pintype "passive"))
    )
    (net (code "217") (name "Net-(C174-Pad1)") (class "Default")
      (node (ref "C174") (pin "1") (pinfunction "1_1") (pintype "passive"))
      (node (ref "SJ190") (pin "1") (pinfunction "1_1") (pintype "passive"))
    )
    (net (code "218") (name "Net-(C175-Pad1)") (class "Default")
      (node (ref "C175") (pin "1") (pinfunction "1_1") (pintype "passive"))
      (node (ref "C179") (pin "2") (pinfunction "2_2") (pintype "passive"))
      (node (ref "SJ191") (pin "2") (pinfunction "2_2") (pintype "passive"))
    )
    (net (code "219") (name "Net-(C175-Pad2)") (class "Default")
      (node (ref "C175") (pin "2") (pinfunction "2_2") (pintype "passive"))
      (node (ref "SJ191") (pin "1") (pinfunction "1_1") (pintype "passive"))
    )
    (net (code "220") (name "Net-(C176-Pad1)") (class "Default")
      (node (ref "C176") (pin "1") (pinfunction "1_1") (pintype "passive"))
      (node (ref "C180") (pin "2") (pinfunction "2_2") (pintype "passive"))
      (node (ref "SJ192") (pin "2") (pinfunction "2_2") (pintype "passive"))
    )
    (net (code "221") (name "Net-(C176-Pad2)") (class "Default")
      (node (ref "C176") (pin "2") (pinfunction "2_2") (pintype "passive"))
      (node (ref "SJ192") (pin "1") (pinfunction "1_1") (pintype "passive"))
    )
    (net (code "222") (name "unconnected-(SJ1-Pad1)") (class "Default")
      (node (ref "SJ1") (pin "1") (pinfunction "1_1") (pintype "passive"))
    )
    (net (code "223") (name "unconnected-(SJ1-Pad2)") (class "Default")
      (node (ref "SJ1") (pin "2") (pinfunction "2_2") (pintype "passive"))
    )
    (net (code "224") (name "unconnected-(SJ2-Pad1)") (class "Default")
      (node (ref "SJ2") (pin "1") (pinfunction "1_1") (pintype "passive"))
    )
    (net (code "225") (name "unconnected-(SJ2-Pad2)") (class "Default")
      (node (ref "SJ2") (pin "2") (pinfunction "2_2") (pintype "passive"))
    )
    (net (code "226") (name "unconnected-(SJ3-Pad1)") (class "Default")
      (node (ref "SJ3") (pin "1") (pinfunction "1_1") (pintype "passive"))
    )
    (net (code "227") (name "unconnected-(SJ3-Pad2)") (class "Default")
      (node (ref "SJ3") (pin "2") (pinfunction "2_2") (pintype "passive"))
    )
    (net (code "228") (name "unconnected-(SJ3-Pad3)") (class "Default")
      (node (ref "SJ3") (pin "3") (pinfunction "3_3") (pintype "passive"))
    )
    (net (code "229") (name "unconnected-(SJ4-Pad1)") (class "Default")
      (node (ref "SJ4") (pin "1") (pinfunction "1_1") (pintype "passive"))
    )
    (net (code "230") (name "unconnected-(SJ4-Pad2)") (class "Default")
      (node (ref "SJ4") (pin "2") (pinfunction "2_2") (pintype "passive"))
    )
    (net (code "231") (name "unconnected-(SJ4-Pad3)") (class "Default")
      (node (ref "SJ4") (pin "3") (pinfunction "3_3") (pintype "passive"))
    )
    (net (code "232") (name "unconnected-(SJ5-Pad1)") (class "Default")
      (node (ref "SJ5") (pin "1") (pinfunction "1_1") (pintype "passive"))
    )
    (net (code "233") (name "unconnected-(SJ5-Pad2)") (class "Default")
      (node (ref "SJ5") (pin "2") (pinfunction "2_2") (pintype "passive"))
    )
    (net (code "234") (name "unconnected-(SJ6-Pad1)") (class "Default")
      (node (ref "SJ6") (pin "1") (pinfunction "1_1") (pintype "passive"))
    )
    (net (code "235") (name "unconnected-(SJ6-Pad2)") (class "Default")
      (node (ref "SJ6") (pin "2") (pinfunction "2_2") (pintype "passive"))
    )
    (net (code "236") (name "unconnected-(SJ7-Pad1)") (class "Default")
      (node (ref "SJ7") (pin "1") (pinfunction "1_1") (pintype "passive"))
    )
    (net (code "237") (name "unconnected-(SJ7-Pad2)") (class "Default")
      (node (ref "SJ7") (pin "2") (pinfunction "2_2") (pintype "passive"))
    )
    (net (code "238") (name "unconnected-(SJ7-Pad3)") (class "Default")
      (node (ref "SJ7") (pin "3") (pinfunction "3_3") (pintype "passive"))
    )
    (net (code "239") (name "unconnected-(SJ8-Pad1)") (class "Default")
      (node (ref "SJ8") (pin "1") (pinfunction "1_1") (pintype "passive"))
    )
    (net (code "240") (name "unconnected-(SJ8-Pad2)") (class "Default")
      (node (ref "SJ8") (pin "2") (pinfunction "2_2") (pintype "passive"))
    )
    (net (code "241") (name "unconnected-(SJ8-Pad3)") (class "Default")
      (node (ref "SJ8") (pin "3") (pinfunction "3_3") (pintype "passive"))
    )
    (net (code "242") (name "unconnected-(SJ21-Pad1)") (class "Default")
      (node (ref "SJ21") (pin "1") (pinfunction "1_1") (pintype "passive"))
    )
    (net (code "243") (name "unconnected-(SJ21-Pad2)") (class "Default")
      (node (ref "SJ21") (pin "2") (pinfunction "2_2") (pintype "passive"))
    )
    (net (code "244") (name "unconnected-(SJ21-Pad3)") (class "Default")
      (node (ref "SJ21") (pin "3") (pinfunction "3_3") (pintype "passive"))
    )
    (net (code "245") (name "unconnected-(SJ22-Pad1)") (class "Default")
      (node (ref "SJ22") (pin "1") (pinfunction "1_1") (pintype "passive"))
    )
    (net (code "246") (name "unconnected-(SJ22-Pad2)") (class "Default")
      (node (ref "SJ22") (pin "2") (pinfunction "2_2") (pintype "passive"))
    )
    (net (code "247") (name "unconnected-(SJ22-Pad3)") (class "Default")
      (node (ref "SJ22") (pin "3") (pinfunction "3_3") (pintype "passive"))
    )
    (net (code "248") (name "unconnected-(SJ23-Pad1)") (class "Default")
      (node (ref "SJ23") (pin "1") (pinfunction "1_1") (pintype "passive"))
    )
    (net (code "249") (name "unconnected-(SJ23-Pad2)") (class "Default")
      (node (ref "SJ23") (pin "2") (pinfunction "2_2") (pintype "passive"))
    )
    (net (code "250") (name "unconnected-(SJ23-Pad3)") (class "Default")
      (node (ref "SJ23") (pin "3") (pinfunction "3_3") (pintype "passive"))
    )
    (net (code "251") (name "unconnected-(SJ24-Pad1)") (class "Default")
      (node (ref "SJ24") (pin "1") (pinfunction "1_1") (pintype "passive"))
    )
    (net (code "252") (name "unconnected-(SJ24-Pad2)") (class "Default")
      (node (ref "SJ24") (pin "2") (pinfunction "2_2") (pintype "passive"))
    )
    (net (code "253") (name "unconnected-(SJ24-Pad3)") (class "Default")
      (node (ref "SJ24") (pin "3") (pinfunction "3_3") (pintype "passive"))
    )
    (net (code "254") (name "unconnected-(SJ25-Pad1)") (class "Default")
      (node (ref "SJ25") (pin "1") (pinfunction "1_1") (pintype "passive"))
    )
    (net (code "255") (name "unconnected-(SJ25-Pad2)") (class "Default")
      (node (ref "SJ25") (pin "2") (pinfunction "2_2") (pintype "passive"))
    )
    (net (code "256") (name "unconnected-(SJ26-Pad1)") (class "Default")
      (node (ref "SJ26") (pin "1") (pinfunction "1_1") (pintype "passive"))
    )
    (net (code "257") (name "unconnected-(SJ26-Pad2)") (class "Default")
      (node (ref "SJ26") (pin "2") (pinfunction "2_2") (pintype "passive"))
    )
    (net (code "258") (name "unconnected-(SJ27-Pad1)") (class "Default")
      (node (ref "SJ27") (pin "1") (pinfunction "1_1") (pintype "passive"))
    )
    (net (code "259") (name "unconnected-(SJ27-Pad2)") (class "Default")
      (node (ref "SJ27") (pin "2") (pinfunction "2_2") (pintype "passive"))
    )
    (net (code "260") (name "unconnected-(SJ28-Pad1)") (class "Default")
      (node (ref "SJ28") (pin "1") (pinfunction "1_1") (pintype "passive"))
    )
    (net (code "261") (name "unconnected-(SJ28-Pad2)") (class "Default")
      (node (ref "SJ28") (pin "2") (pinfunction "2_2") (pintype "passive"))
    )
    (net (code "262") (name "unconnected-(SJ29-Pad1)") (class "Default")
      (node (ref "SJ29") (pin "1") (pinfunction "1_1") (pintype "passive"))
    )
    (net (code "263") (name "unconnected-(SJ29-Pad2)") (class "Default")
      (node (ref "SJ29") (pin "2") (pinfunction "2_2") (pintype "passive"))
    )
    (net (code "264") (name "unconnected-(SJ30-Pad1)") (class "Default")
      (node (ref "SJ30") (pin "1") (pinfunction "1_1") (pintype "passive"))
    )
    (net (code "265") (name "unconnected-(SJ30-Pad2)") (class "Default")
      (node (ref "SJ30") (pin "2") (pinfunction "2_2") (pintype "passive"))
    )
    (net (code "266") (name "unconnected-(SJ31-Pad1)") (class "Default")
      (node (ref "SJ31") (pin "1") (pinfunction "1_1") (pintype "passive"))
    )
    (net (code "267") (name "unconnected-(SJ31-Pad2)") (class "Default")
      (node (ref "SJ31") (pin "2") (pinfunction "2_2") (pintype "passive"))
    )
    (net (code "268") (name "unconnected-(SJ31-Pad3)") (class "Default")
      (node (ref "SJ31") (pin "3") (pinfunction "3_3") (pintype "passive"))
    )
    (net (code "269") (name "unconnected-(SJ32-Pad1)") (class "Default")
      (node (ref "SJ32") (pin "1") (pinfunction "1_1") (pintype "passive"))
    )
    (net (code "270") (name "unconnected-(SJ32-Pad2)") (class "Default")
      (node (ref "SJ32") (pin "2") (pinfunction "2_2") (pintype "passive"))
    )
    (net (code "271") (name "unconnected-(SJ32-Pad3)") (class "Default")
      (node (ref "SJ32") (pin "3") (pinfunction "3_3") (pintype "passive"))
    )
    (net (code "272") (name "unconnected-(SJ45-Pad1)") (class "Default")
      (node (ref "SJ45") (pin "1") (pinfunction "1_1") (pintype "passive"))
    )
    (net (code "273") (name "unconnected-(SJ45-Pad2)") (class "Default")
      (node (ref "SJ45") (pin "2") (pinfunction "2_2") (pintype "passive"))
    )
    (net (code "274") (name "unconnected-(SJ46-Pad1)") (class "Default")
      (node (ref "SJ46") (pin "1") (pinfunction "1_1") (pintype "passive"))
    )
    (net (code "275") (name "unconnected-(SJ46-Pad2)") (class "Default")
      (node (ref "SJ46") (pin "2") (pinfunction "2_2") (pintype "passive"))
    )
    (net (code "276") (name "unconnected-(SJ47-Pad1)") (class "Default")
      (node (ref "SJ47") (pin "1") (pinfunction "1_1") (pintype "passive"))
    )
    (net (code "277") (name "unconnected-(SJ47-Pad2)") (class "Default")
      (node (ref "SJ47") (pin "2") (pinfunction "2_2") (pintype "passive"))
    )
    (net (code "278") (name "unconnected-(SJ47-Pad3)") (class "Default")
      (node (ref "SJ47") (pin "3") (pinfunction "3_3") (pintype "passive"))
    )
    (net (code "279") (name "unconnected-(SJ48-Pad1)") (class "Default")
      (node (ref "SJ48") (pin "1") (pinfunction "1_1") (pintype "passive"))
    )
    (net (code "280") (name "unconnected-(SJ48-Pad2)") (class "Default")
      (node (ref "SJ48") (pin "2") (pinfunction "2_2") (pintype "passive"))
    )
    (net (code "281") (name "unconnected-(SJ48-Pad3)") (class "Default")
      (node (ref "SJ48") (pin "3") (pinfunction "3_3") (pintype "passive"))
    )
    (net (code "282") (name "unconnected-(SJ73-Pad1)") (class "Default")
      (node (ref "SJ73") (pin "1") (pinfunction "1_1") (pintype "passive"))
    )
    (net (code "283") (name "unconnected-(SJ73-Pad2)") (class "Default")
      (node (ref "SJ73") (pin "2") (pinfunction "2_2") (pintype "passive"))
    )
    (net (code "284") (name "unconnected-(SJ73-Pad3)") (class "Default")
      (node (ref "SJ73") (pin "3") (pinfunction "3_3") (pintype "passive"))
    )
    (net (code "285") (name "unconnected-(SJ74-Pad1)") (class "Default")
      (node (ref "SJ74") (pin "1") (pinfunction "1_1") (pintype "passive"))
    )
    (net (code "286") (name "unconnected-(SJ74-Pad2)") (class "Default")
      (node (ref "SJ74") (pin "2") (pinfunction "2_2") (pintype "passive"))
    )
    (net (code "287") (name "unconnected-(SJ74-Pad3)") (class "Default")
      (node (ref "SJ74") (pin "3") (pinfunction "3_3") (pintype "passive"))
    )
    (net (code "288") (name "unconnected-(SJ75-Pad1)") (class "Default")
      (node (ref "SJ75") (pin "1") (pinfunction "1_1") (pintype "passive"))
    )
    (net (code "289") (name "unconnected-(SJ75-Pad2)") (class "Default")
      (node (ref "SJ75") (pin "2") (pinfunction "2_2") (pintype "passive"))
    )
    (net (code "290") (name "unconnected-(SJ75-Pad3)") (class "Default")
      (node (ref "SJ75") (pin "3") (pinfunction "3_3") (pintype "passive"))
    )
    (net (code "291") (name "unconnected-(SJ76-Pad1)") (class "Default")
      (node (ref "SJ76") (pin "1") (pinfunction "1_1") (pintype "passive"))
    )
    (net (code "292") (name "unconnected-(SJ76-Pad2)") (class "Default")
      (node (ref "SJ76") (pin "2") (pinfunction "2_2") (pintype "passive"))
    )
    (net (code "293") (name "unconnected-(SJ76-Pad3)") (class "Default")
      (node (ref "SJ76") (pin "3") (pinfunction "3_3") (pintype "passive"))
    )
    (net (code "294") (name "unconnected-(SJ77-Pad1)") (class "Default")
      (node (ref "SJ77") (pin "1") (pinfunction "1_1") (pintype "passive"))
    )
    (net (code "295") (name "unconnected-(SJ77-Pad2)") (class "Default")
      (node (ref "SJ77") (pin "2") (pinfunction "2_2") (pintype "passive"))
    )
    (net (code "296") (name "unconnected-(SJ78-Pad1)") (class "Default")
      (node (ref "SJ78") (pin "1") (pinfunction "1_1") (pintype "passive"))
    )
    (net (code "297") (name "unconnected-(SJ78-Pad2)") (class "Default")
      (node (ref "SJ78") (pin "2") (pinfunction "2_2") (pintype "passive"))
    )
    (net (code "298") (name "unconnected-(SJ79-Pad1)") (class "Default")
      (node (ref "SJ79") (pin "1") (pinfunction "1_1") (pintype "passive"))
    )
    (net (code "299") (name "unconnected-(SJ79-Pad2)") (class "Default")
      (node (ref "SJ79") (pin "2") (pinfunction "2_2") (pintype "passive"))
    )
    (net (code "300") (name "unconnected-(SJ80-Pad1)") (class "Default")
      (node (ref "SJ80") (pin "1") (pinfunction "1_1") (pintype "passive"))
    )
    (net (code "301") (name "unconnected-(SJ80-Pad2)") (class "Default")
      (node (ref "SJ80") (pin "2") (pinfunction "2_2") (pintype "passive"))
    )
    (net (code "302") (name "unconnected-(SJ81-Pad1)") (class "Default")
      (node (ref "SJ81") (pin "1") (pinfunction "1_1") (pintype "passive"))
    )
    (net (code "303") (name "unconnected-(SJ81-Pad2)") (class "Default")
      (node (ref "SJ81") (pin "2") (pinfunction "2_2") (pintype "passive"))
    )
    (net (code "304") (name "unconnected-(SJ82-Pad1)") (class "Default")
      (node (ref "SJ82") (pin "1") (pinfunction "1_1") (pintype "passive"))
    )
    (net (code "305") (name "unconnected-(SJ82-Pad2)") (class "Default")
      (node (ref "SJ82") (pin "2") (pinfunction "2_2") (pintype "passive"))
    )
    (net (code "306") (name "unconnected-(SJ83-Pad1)") (class "Default")
      (node (ref "SJ83") (pin "1") (pinfunction "1_1") (pintype "passive"))
    )
    (net (code "307") (name "unconnected-(SJ83-Pad2)") (class "Default")
      (node (ref "SJ83") (pin "2") (pinfunction "2_2") (pintype "passive"))
    )
    (net (code "308") (name "unconnected-(SJ83-Pad3)") (class "Default")
      (node (ref "SJ83") (pin "3") (pinfunction "3_3") (pintype "passive"))
    )
    (net (code "309") (name "unconnected-(SJ84-Pad1)") (class "Default")
      (node (ref "SJ84") (pin "1") (pinfunction "1_1") (pintype "passive"))
    )
    (net (code "310") (name "unconnected-(SJ84-Pad2)") (class "Default")
      (node (ref "SJ84") (pin "2") (pinfunction "2_2") (pintype "passive"))
    )
    (net (code "311") (name "unconnected-(SJ84-Pad3)") (class "Default")
      (node (ref "SJ84") (pin "3") (pinfunction "3_3") (pintype "passive"))
    )
    (net (code "312") (name "unconnected-(SJ85-Pad1)") (class "Default")
      (node (ref "SJ85") (pin "1") (pinfunction "1_1") (pintype "passive"))
    )
    (net (code "313") (name "unconnected-(SJ85-Pad2)") (class "Default")
      (node (ref "SJ85") (pin "2") (pinfunction "2_2") (pintype "passive"))
    )
    (net (code "314") (name "unconnected-(SJ86-Pad1)") (class "Default")
      (node (ref "SJ86") (pin "1") (pinfunction "1_1") (pintype "passive"))
    )
    (net (code "315") (name "unconnected-(SJ86-Pad2)") (class "Default")
      (node (ref "SJ86") (pin "2") (pinfunction "2_2") (pintype "passive"))
    )
    (net (code "316") (name "unconnected-(SJ87-Pad1)") (class "Default")
      (node (ref "SJ87") (pin "1") (pinfunction "1_1") (pintype "passive"))
    )
    (net (code "317") (name "unconnected-(SJ87-Pad2)") (class "Default")
      (node (ref "SJ87") (pin "2") (pinfunction "2_2") (pintype "passive"))
    )
    (net (code "318") (name "unconnected-(SJ87-Pad3)") (class "Default")
      (node (ref "SJ87") (pin "3") (pinfunction "3_3") (pintype "passive"))
    )
    (net (code "319") (name "unconnected-(SJ88-Pad1)") (class "Default")
      (node (ref "SJ88") (pin "1") (pinfunction "1_1") (pintype "passive"))
    )
    (net (code "320") (name "unconnected-(SJ88-Pad2)") (class "Default")
      (node (ref "SJ88") (pin "2") (pinfunction "2_2") (pintype "passive"))
    )
    (net (code "321") (name "unconnected-(SJ88-Pad3)") (class "Default")
      (node (ref "SJ88") (pin "3") (pinfunction "3_3") (pintype "passive"))
    )
    (net (code "322") (name "unconnected-(SJ113-Pad1)") (class "Default")
      (node (ref "SJ113") (pin "1") (pinfunction "1_1") (pintype "passive"))
    )
    (net (code "323") (name "unconnected-(SJ113-Pad2)") (class "Default")
      (node (ref "SJ113") (pin "2") (pinfunction "2_2") (pintype "passive"))
    )
    (net (code "324") (name "unconnected-(SJ113-Pad3)") (class "Default")
      (node (ref "SJ113") (pin "3") (pinfunction "3_3") (pintype "passive"))
    )
    (net (code "325") (name "unconnected-(SJ114-Pad1)") (class "Default")
      (node (ref "SJ114") (pin "1") (pinfunction "1_1") (pintype "passive"))
    )
    (net (code "326") (name "unconnected-(SJ114-Pad2)") (class "Default")
      (node (ref "SJ114") (pin "2") (pinfunction "2_2") (pintype "passive"))
    )
    (net (code "327") (name "unconnected-(SJ114-Pad3)") (class "Default")
      (node (ref "SJ114") (pin "3") (pinfunction "3_3") (pintype "passive"))
    )
    (net (code "328") (name "unconnected-(SJ115-Pad1)") (class "Default")
      (node (ref "SJ115") (pin "1") (pinfunction "1_1") (pintype "passive"))
    )
    (net (code "329") (name "unconnected-(SJ115-Pad2)") (class "Default")
      (node (ref "SJ115") (pin "2") (pinfunction "2_2") (pintype "passive"))
    )
    (net (code "330") (name "unconnected-(SJ115-Pad3)") (class "Default")
      (node (ref "SJ115") (pin "3") (pinfunction "3_3") (pintype "passive"))
    )
    (net (code "331") (name "unconnected-(SJ116-Pad1)") (class "Default")
      (node (ref "SJ116") (pin "1") (pinfunction "1_1") (pintype "passive"))
    )
    (net (code "332") (name "unconnected-(SJ116-Pad2)") (class "Default")
      (node (ref "SJ116") (pin "2") (pinfunction "2_2") (pintype "passive"))
    )
    (net (code "333") (name "unconnected-(SJ116-Pad3)") (class "Default")
      (node (ref "SJ116") (pin "3") (pinfunction "3_3") (pintype "passive"))
    )
    (net (code "334") (name "unconnected-(SJ117-Pad1)") (class "Default")
      (node (ref "SJ117") (pin "1") (pinfunction "1_1") (pintype "passive"))
    )
    (net (code "335") (name "unconnected-(SJ117-Pad2)") (class "Default")
      (node (ref "SJ117") (pin "2") (pinfunction "2_2") (pintype "passive"))
    )
    (net (code "336") (name "unconnected-(SJ118-Pad1)") (class "Default")
      (node (ref "SJ118") (pin "1") (pinfunction "1_1") (pintype "passive"))
    )
    (net (code "337") (name "unconnected-(SJ118-Pad2)") (class "Default")
      (node (ref "SJ118") (pin "2") (pinfunction "2_2") (pintype "passive"))
    )
    (net (code "338") (name "unconnected-(SJ119-Pad1)") (class "Default")
      (node (ref "SJ119") (pin "1") (pinfunction "1_1") (pintype "passive"))
    )
    (net (code "339") (name "unconnected-(SJ119-Pad2)") (class "Default")
      (node (ref "SJ119") (pin "2") (pinfunction "2_2") (pintype "passive"))
    )
    (net (code "340") (name "unconnected-(SJ120-Pad1)") (class "Default")
      (node (ref "SJ120") (pin "1") (pinfunction "1_1") (pintype "passive"))
    )
    (net (code "341") (name "unconnected-(SJ120-Pad2)") (class "Default")
      (node (ref "SJ120") (pin "2") (pinfunction "2_2") (pintype "passive"))
    )
    (net (code "342") (name "unconnected-(SJ121-Pad1)") (class "Default")
      (node (ref "SJ121") (pin "1") (pinfunction "1_1") (pintype "passive"))
    )
    (net (code "343") (name "unconnected-(SJ121-Pad2)") (class "Default")
      (node (ref "SJ121") (pin "2") (pinfunction "2_2") (pintype "passive"))
    )
    (net (code "344") (name "unconnected-(SJ122-Pad1)") (class "Default")
      (node (ref "SJ122") (pin "1") (pinfunction "1_1") (pintype "passive"))
    )
    (net (code "345") (name "unconnected-(SJ122-Pad2)") (class "Default")
      (node (ref "SJ122") (pin "2") (pinfunction "2_2") (pintype "passive"))
    )
    (net (code "346") (name "unconnected-(SJ123-Pad1)") (class "Default")
      (node (ref "SJ123") (pin "1") (pinfunction "1_1") (pintype "passive"))
    )
    (net (code "347") (name "unconnected-(SJ123-Pad2)") (class "Default")
      (node (ref "SJ123") (pin "2") (pinfunction "2_2") (pintype "passive"))
    )
    (net (code "348") (name "unconnected-(SJ123-Pad3)") (class "Default")
      (node (ref "SJ123") (pin "3") (pinfunction "3_3") (pintype "passive"))
    )
    (net (code "349") (name "unconnected-(SJ124-Pad1)") (class "Default")
      (node (ref "SJ124") (pin "1") (pinfunction "1_1") (pintype "passive"))
    )
    (net (code "350") (name "unconnected-(SJ124-Pad2)") (class "Default")
      (node (ref "SJ124") (pin "2") (pinfunction "2_2") (pintype "passive"))
    )
    (net (code "351") (name "unconnected-(SJ124-Pad3)") (class "Default")
      (node (ref "SJ124") (pin "3") (pinfunction "3_3") (pintype "passive"))
    )
    (net (code "352") (name "unconnected-(SJ125-Pad1)") (class "Default")
      (node (ref "SJ125") (pin "1") (pinfunction "1_1") (pintype "passive"))
    )
    (net (code "353") (name "unconnected-(SJ125-Pad2)") (class "Default")
      (node (ref "SJ125") (pin "2") (pinfunction "2_2") (pintype "passive"))
    )
    (net (code "354") (name "unconnected-(SJ126-Pad1)") (class "Default")
      (node (ref "SJ126") (pin "1") (pinfunction "1_1") (pintype "passive"))
    )
    (net (code "355") (name "unconnected-(SJ126-Pad2)") (class "Default")
      (node (ref "SJ126") (pin "2") (pinfunction "2_2") (pintype "passive"))
    )
    (net (code "356") (name "unconnected-(SJ127-Pad1)") (class "Default")
      (node (ref "SJ127") (pin "1") (pinfunction "1_1") (pintype "passive"))
    )
    (net (code "357") (name "unconnected-(SJ127-Pad2)") (class "Default")
      (node (ref "SJ127") (pin "2") (pinfunction "2_2") (pintype "passive"))
    )
    (net (code "358") (name "unconnected-(SJ127-Pad3)") (class "Default")
      (node (ref "SJ127") (pin "3") (pinfunction "3_3") (pintype "passive"))
    )
    (net (code "359") (name "unconnected-(SJ128-Pad1)") (class "Default")
      (node (ref "SJ128") (pin "1") (pinfunction "1_1") (pintype "passive"))
    )
    (net (code "360") (name "unconnected-(SJ128-Pad2)") (class "Default")
      (node (ref "SJ128") (pin "2") (pinfunction "2_2") (pintype "passive"))
    )
    (net (code "361") (name "unconnected-(SJ128-Pad3)") (class "Default")
      (node (ref "SJ128") (pin "3") (pinfunction "3_3") (pintype "passive"))
    )
    (net (code "362") (name "unconnected-(SJ153-Pad1)") (class "Default")
      (node (ref "SJ153") (pin "1") (pinfunction "1_1") (pintype "passive"))
    )
    (net (code "363") (name "unconnected-(SJ153-Pad2)") (class "Default")
      (node (ref "SJ153") (pin "2") (pinfunction "2_2") (pintype "passive"))
    )
    (net (code "364") (name "unconnected-(SJ153-Pad3)") (class "Default")
      (node (ref "SJ153") (pin "3") (pinfunction "3_3") (pintype "passive"))
    )
    (net (code "365") (name "unconnected-(SJ154-Pad1)") (class "Default")
      (node (ref "SJ154") (pin "1") (pinfunction "1_1") (pintype "passive"))
    )
    (net (code "366") (name "unconnected-(SJ154-Pad2)") (class "Default")
      (node (ref "SJ154") (pin "2") (pinfunction "2_2") (pintype "passive"))
    )
    (net (code "367") (name "unconnected-(SJ154-Pad3)") (class "Default")
      (node (ref "SJ154") (pin "3") (pinfunction "3_3") (pintype "passive"))
    )
    (net (code "368") (name "unconnected-(SJ155-Pad1)") (class "Default")
      (node (ref "SJ155") (pin "1") (pinfunction "1_1") (pintype "passive"))
    )
    (net (code "369") (name "unconnected-(SJ155-Pad2)") (class "Default")
      (node (ref "SJ155") (pin "2") (pinfunction "2_2") (pintype "passive"))
    )
    (net (code "370") (name "unconnected-(SJ155-Pad3)") (class "Default")
      (node (ref "SJ155") (pin "3") (pinfunction "3_3") (pintype "passive"))
    )
    (net (code "371") (name "unconnected-(SJ156-Pad1)") (class "Default")
      (node (ref "SJ156") (pin "1") (pinfunction "1_1") (pintype "passive"))
    )
    (net (code "372") (name "unconnected-(SJ156-Pad2)") (class "Default")
      (node (ref "SJ156") (pin "2") (pinfunction "2_2") (pintype "passive"))
    )
    (net (code "373") (name "unconnected-(SJ156-Pad3)") (class "Default")
      (node (ref "SJ156") (pin "3") (pinfunction "3_3") (pintype "passive"))
    )
    (net (code "374") (name "unconnected-(SJ157-Pad1)") (class "Default")
      (node (ref "SJ157") (pin "1") (pinfunction "1_1") (pintype "passive"))
    )
    (net (code "375") (name "unconnected-(SJ157-Pad2)") (class "Default")
      (node (ref "SJ157") (pin "2") (pinfunction "2_2") (pintype "passive"))
    )
    (net (code "376") (name "unconnected-(SJ158-Pad1)") (class "Default")
      (node (ref "SJ158") (pin "1") (pinfunction "1_1") (pintype "passive"))
    )
    (net (code "377") (name "unconnected-(SJ158-Pad2)") (class "Default")
      (node (ref "SJ158") (pin "2") (pinfunction "2_2") (pintype "passive"))
    )
    (net (code "378") (name "unconnected-(SJ159-Pad1)") (class "Default")
      (node (ref "SJ159") (pin "1") (pinfunction "1_1") (pintype "passive"))
    )
    (net (code "379") (name "unconnected-(SJ159-Pad2)") (class "Default")
      (node (ref "SJ159") (pin "2") (pinfunction "2_2") (pintype "passive"))
    )
    (net (code "380") (name "unconnected-(SJ160-Pad1)") (class "Default")
      (node (ref "SJ160") (pin "1") (pinfunction "1_1") (pintype "passive"))
    )
    (net (code "381") (name "unconnected-(SJ160-Pad2)") (class "Default")
      (node (ref "SJ160") (pin "2") (pinfunction "2_2") (pintype "passive"))
    )
    (net (code "382") (name "unconnected-(SJ161-Pad1)") (class "Default")
      (node (ref "SJ161") (pin "1") (pinfunction "1_1") (pintype "passive"))
    )
    (net (code "383") (name "unconnected-(SJ161-Pad2)") (class "Default")
      (node (ref "SJ161") (pin "2") (pinfunction "2_2") (pintype "passive"))
    )
    (net (code "384") (name "unconnected-(SJ162-Pad1)") (class "Default")
      (node (ref "SJ162") (pin "1") (pinfunction "1_1") (pintype "passive"))
    )
    (net (code "385") (name "unconnected-(SJ162-Pad2)") (class "Default")
      (node (ref "SJ162") (pin "2") (pinfunction "2_2") (pintype "passive"))
    )
    (net (code "386") (name "unconnected-(SJ163-Pad1)") (class "Default")
      (node (ref "SJ163") (pin "1") (pinfunction "1_1") (pintype "passive"))
    )
    (net (code "387") (name "unconnected-(SJ163-Pad2)") (class "Default")
      (node (ref "SJ163") (pin "2") (pinfunction "2_2") (pintype "passive"))
    )
    (net (code "388") (name "unconnected-(SJ163-Pad3)") (class "Default")
      (node (ref "SJ163") (pin "3") (pinfunction "3_3") (pintype "passive"))
    )
    (net (code "389") (name "unconnected-(SJ164-Pad1)") (class "Default")
      (node (ref "SJ164") (pin "1") (pinfunction "1_1") (pintype "passive"))
    )
    (net (code "390") (name "unconnected-(SJ164-Pad2)") (class "Default")
      (node (ref "SJ164") (pin "2") (pinfunction "2_2") (pintype "passive"))
    )
    (net (code "391") (name "unconnected-(SJ164-Pad3)") (class "Default")
      (node (ref "SJ164") (pin "3") (pinfunction "3_3") (pintype "passive"))
    )
    (net (code "392") (name "unconnected-(SJ165-Pad1)") (class "Default")
      (node (ref "SJ165") (pin "1") (pinfunction "1_1") (pintype "passive"))
    )
    (net (code "393") (name "unconnected-(SJ165-Pad2)") (class "Default")
      (node (ref "SJ165") (pin "2") (pinfunction "2_2") (pintype "passive"))
    )
    (net (code "394") (name "unconnected-(SJ166-Pad1)") (class "Default")
      (node (ref "SJ166") (pin "1") (pinfunction "1_1") (pintype "passive"))
    )
    (net (code "395") (name "unconnected-(SJ166-Pad2)") (class "Default")
      (node (ref "SJ166") (pin "2") (pinfunction "2_2") (pintype "passive"))
    )
    (net (code "396") (name "unconnected-(SJ167-Pad1)") (class "Default")
      (node (ref "SJ167") (pin "1") (pinfunction "1_1") (pintype "passive"))
    )
    (net (code "397") (name "unconnected-(SJ167-Pad2)") (class "Default")
      (node (ref "SJ167") (pin "2") (pinfunction "2_2") (pintype "passive"))
    )
    (net (code "398") (name "unconnected-(SJ167-Pad3)") (class "Default")
      (node (ref "SJ167") (pin "3") (pinfunction "3_3") (pintype "passive"))
    )
    (net (code "399") (name "unconnected-(SJ168-Pad1)") (class "Default")
      (node (ref "SJ168") (pin "1") (pinfunction "1_1") (pintype "passive"))
    )
    (net (code "400") (name "unconnected-(SJ168-Pad2)") (class "Default")
      (node (ref "SJ168") (pin "2") (pinfunction "2_2") (pintype "passive"))
    )
    (net (code "401") (name "unconnected-(SJ168-Pad3)") (class "Default")
      (node (ref "SJ168") (pin "3") (pinfunction "3_3") (pintype "passive"))
    )
    (net (code "402") (name "unconnected-(SJ193-Pad1)") (class "Default")
      (node (ref "SJ193") (pin "1") (pinfunction "1_1") (pintype "passive"))
    )
    (net (code "403") (name "unconnected-(SJ193-Pad2)") (class "Default")
      (node (ref "SJ193") (pin "2") (pinfunction "2_2") (pintype "passive"))
    )
    (net (code "404") (name "unconnected-(SJ193-Pad3)") (class "Default")
      (node (ref "SJ193") (pin "3") (pinfunction "3_3") (pintype "passive"))
    )
    (net (code "405") (name "unconnected-(SJ194-Pad1)") (class "Default")
      (node (ref "SJ194") (pin "1") (pinfunction "1_1") (pintype "passive"))
    )
    (net (code "406") (name "unconnected-(SJ194-Pad2)") (class "Default")
      (node (ref "SJ194") (pin "2") (pinfunction "2_2") (pintype "passive"))
    )
    (net (code "407") (name "unconnected-(SJ194-Pad3)") (class "Default")
      (node (ref "SJ194") (pin "3") (pinfunction "3_3") (pintype "passive"))
    )
    (net (code "408") (name "unconnected-(SJ195-Pad1)") (class "Default")
      (node (ref "SJ195") (pin "1") (pinfunction "1_1") (pintype "passive"))
    )
    (net (code "409") (name "unconnected-(SJ195-Pad2)") (class "Default")
      (node (ref "SJ195") (pin "2") (pinfunction "2_2") (pintype "passive"))
    )
    (net (code "410") (name "unconnected-(SJ195-Pad3)") (class "Default")
      (node (ref "SJ195") (pin "3") (pinfunction "3_3") (pintype "passive"))
    )
    (net (code "411") (name "unconnected-(SJ196-Pad1)") (class "Default")
      (node (ref "SJ196") (pin "1") (pinfunction "1_1") (pintype "passive"))
    )
    (net (code "412") (name "unconnected-(SJ196-Pad2)") (class "Default")
      (node (ref "SJ196") (pin "2") (pinfunction "2_2") (pintype "passive"))
    )
    (net (code "413") (name "unconnected-(SJ196-Pad3)") (class "Default")
      (node (ref "SJ196") (pin "3") (pinfunction "3_3") (pintype "passive"))
    )
    (net (code "414") (name "unconnected-(SJ197-Pad1)") (class "Default")
      (node (ref "SJ197") (pin "1") (pinfunction "1_1") (pintype "passive"))
    )
    (net (code "415") (name "unconnected-(SJ197-Pad2)") (class "Default")
      (node (ref "SJ197") (pin "2") (pinfunction "2_2") (pintype "passive"))
    )
    (net (code "416") (name "unconnected-(SJ198-Pad1)") (class "Default")
      (node (ref "SJ198") (pin "1") (pinfunction "1_1") (pintype "passive"))
    )
    (net (code "417") (name "unconnected-(SJ198-Pad2)") (class "Default")
      (node (ref "SJ198") (pin "2") (pinfunction "2_2") (pintype "passive"))
    )
    (net (code "418") (name "unconnected-(SJ199-Pad1)") (class "Default")
      (node (ref "SJ199") (pin "1") (pinfunction "1_1") (pintype "passive"))
    )
    (net (code "419") (name "unconnected-(SJ199-Pad2)") (class "Default")
      (node (ref "SJ199") (pin "2") (pinfunction "2_2") (pintype "passive"))
    )
    (net (code "420") (name "unconnected-(SJ200-Pad1)") (class "Default")
      (node (ref "SJ200") (pin "1") (pinfunction "1_1") (pintype "passive"))
    )
    (net (code "421") (name "unconnected-(SJ200-Pad2)") (class "Default")
      (node (ref "SJ200") (pin "2") (pinfunction "2_2") (pintype "passive"))
    )
  )
)
